# piezo-driver_v0_95-R002.net
KiCad netlist of a schematic drawn in EAGLE
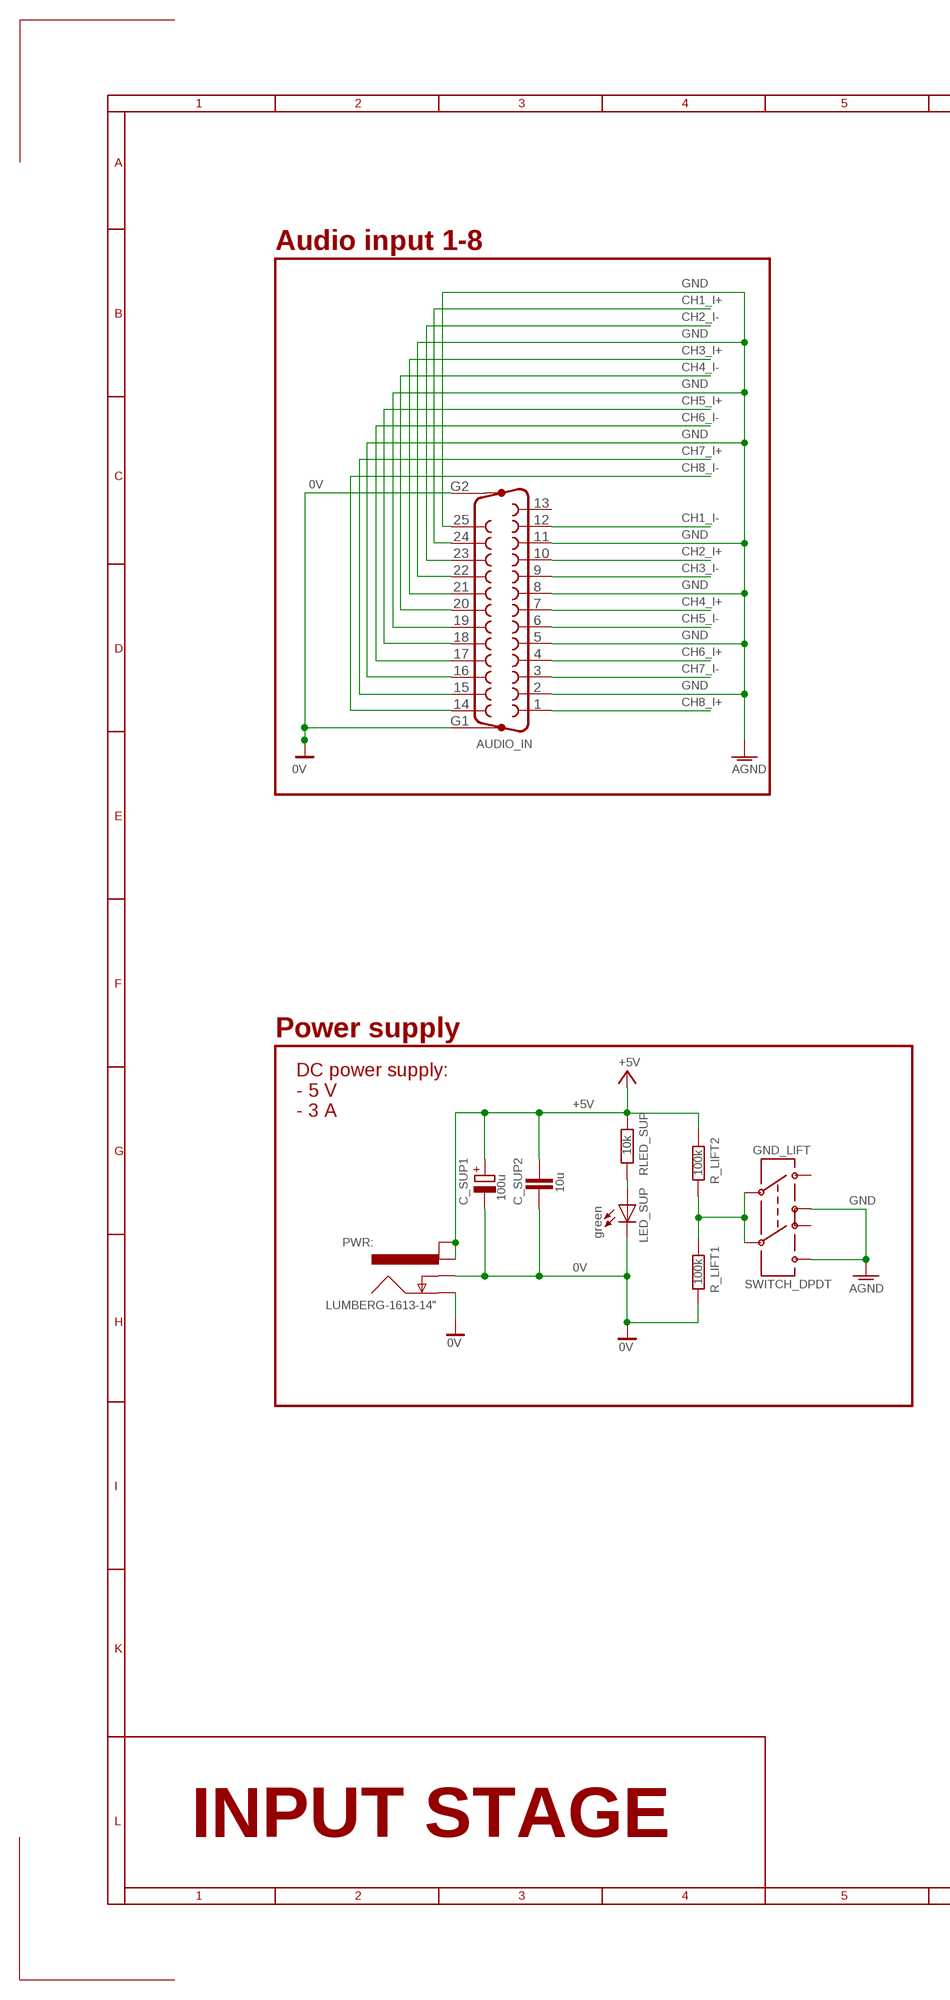
[diagram p0: schematic, sheet 1, part 1 of 2]
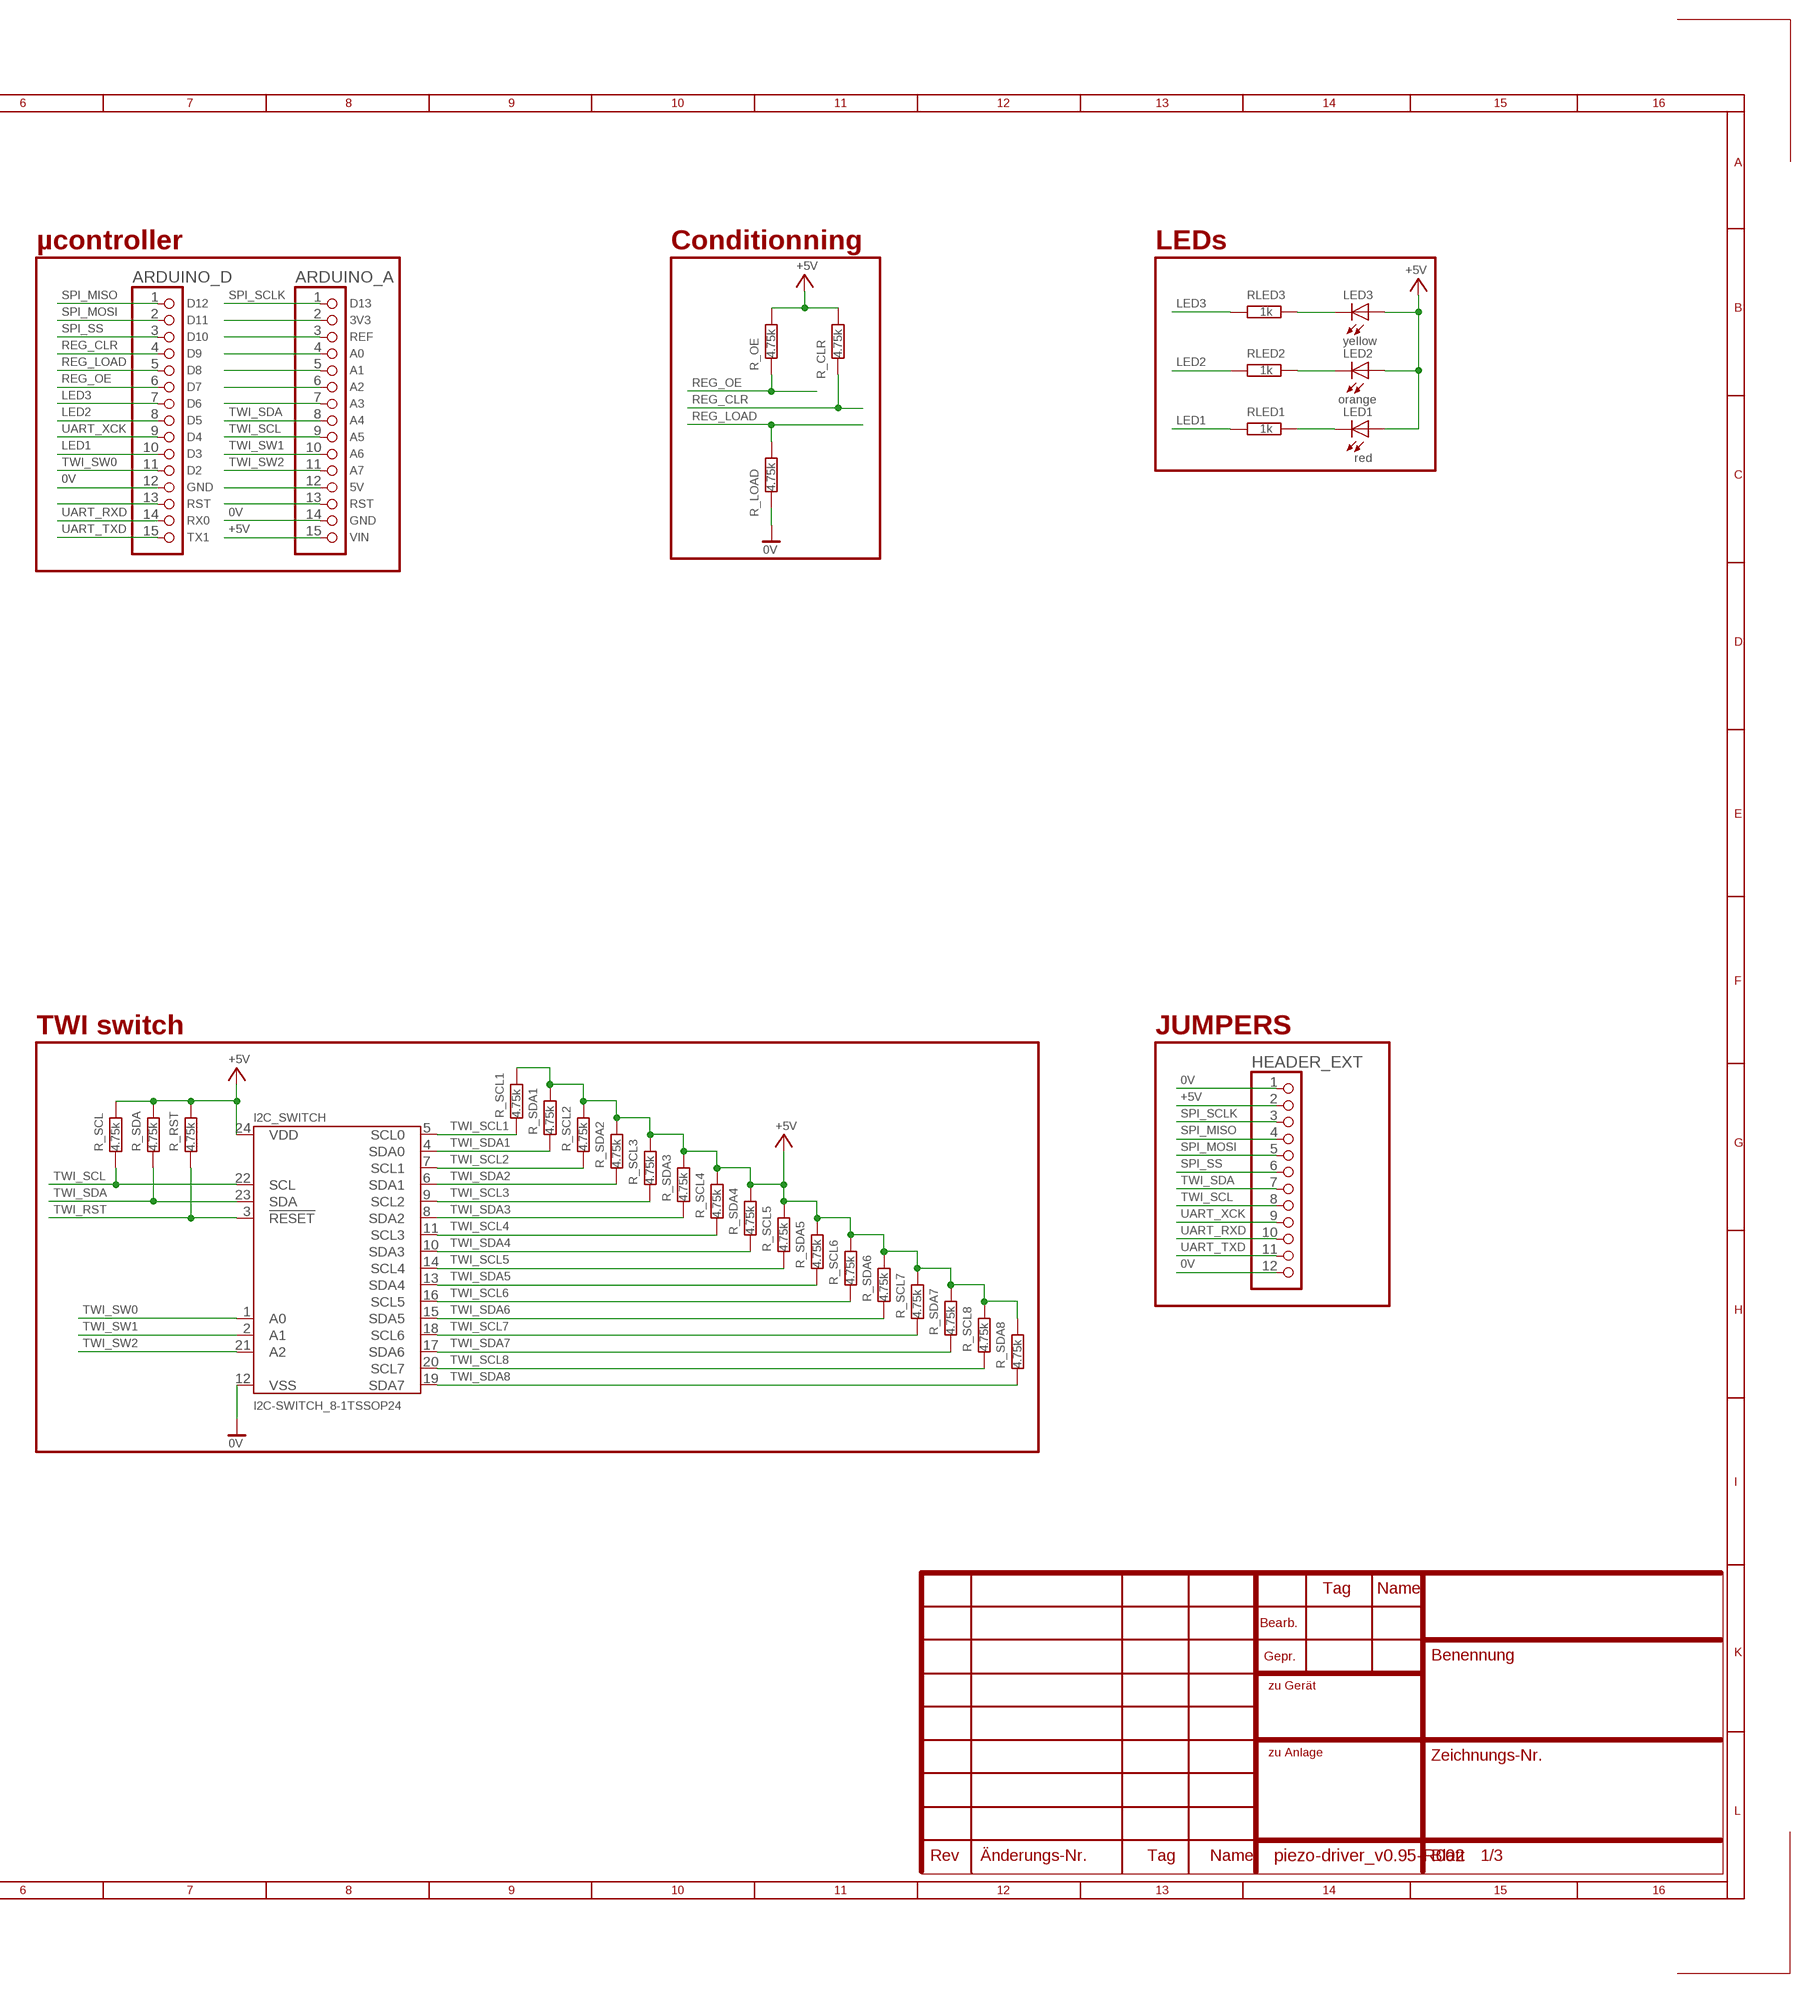
[diagram p1: schematic, sheet 1, part 2 of 2]
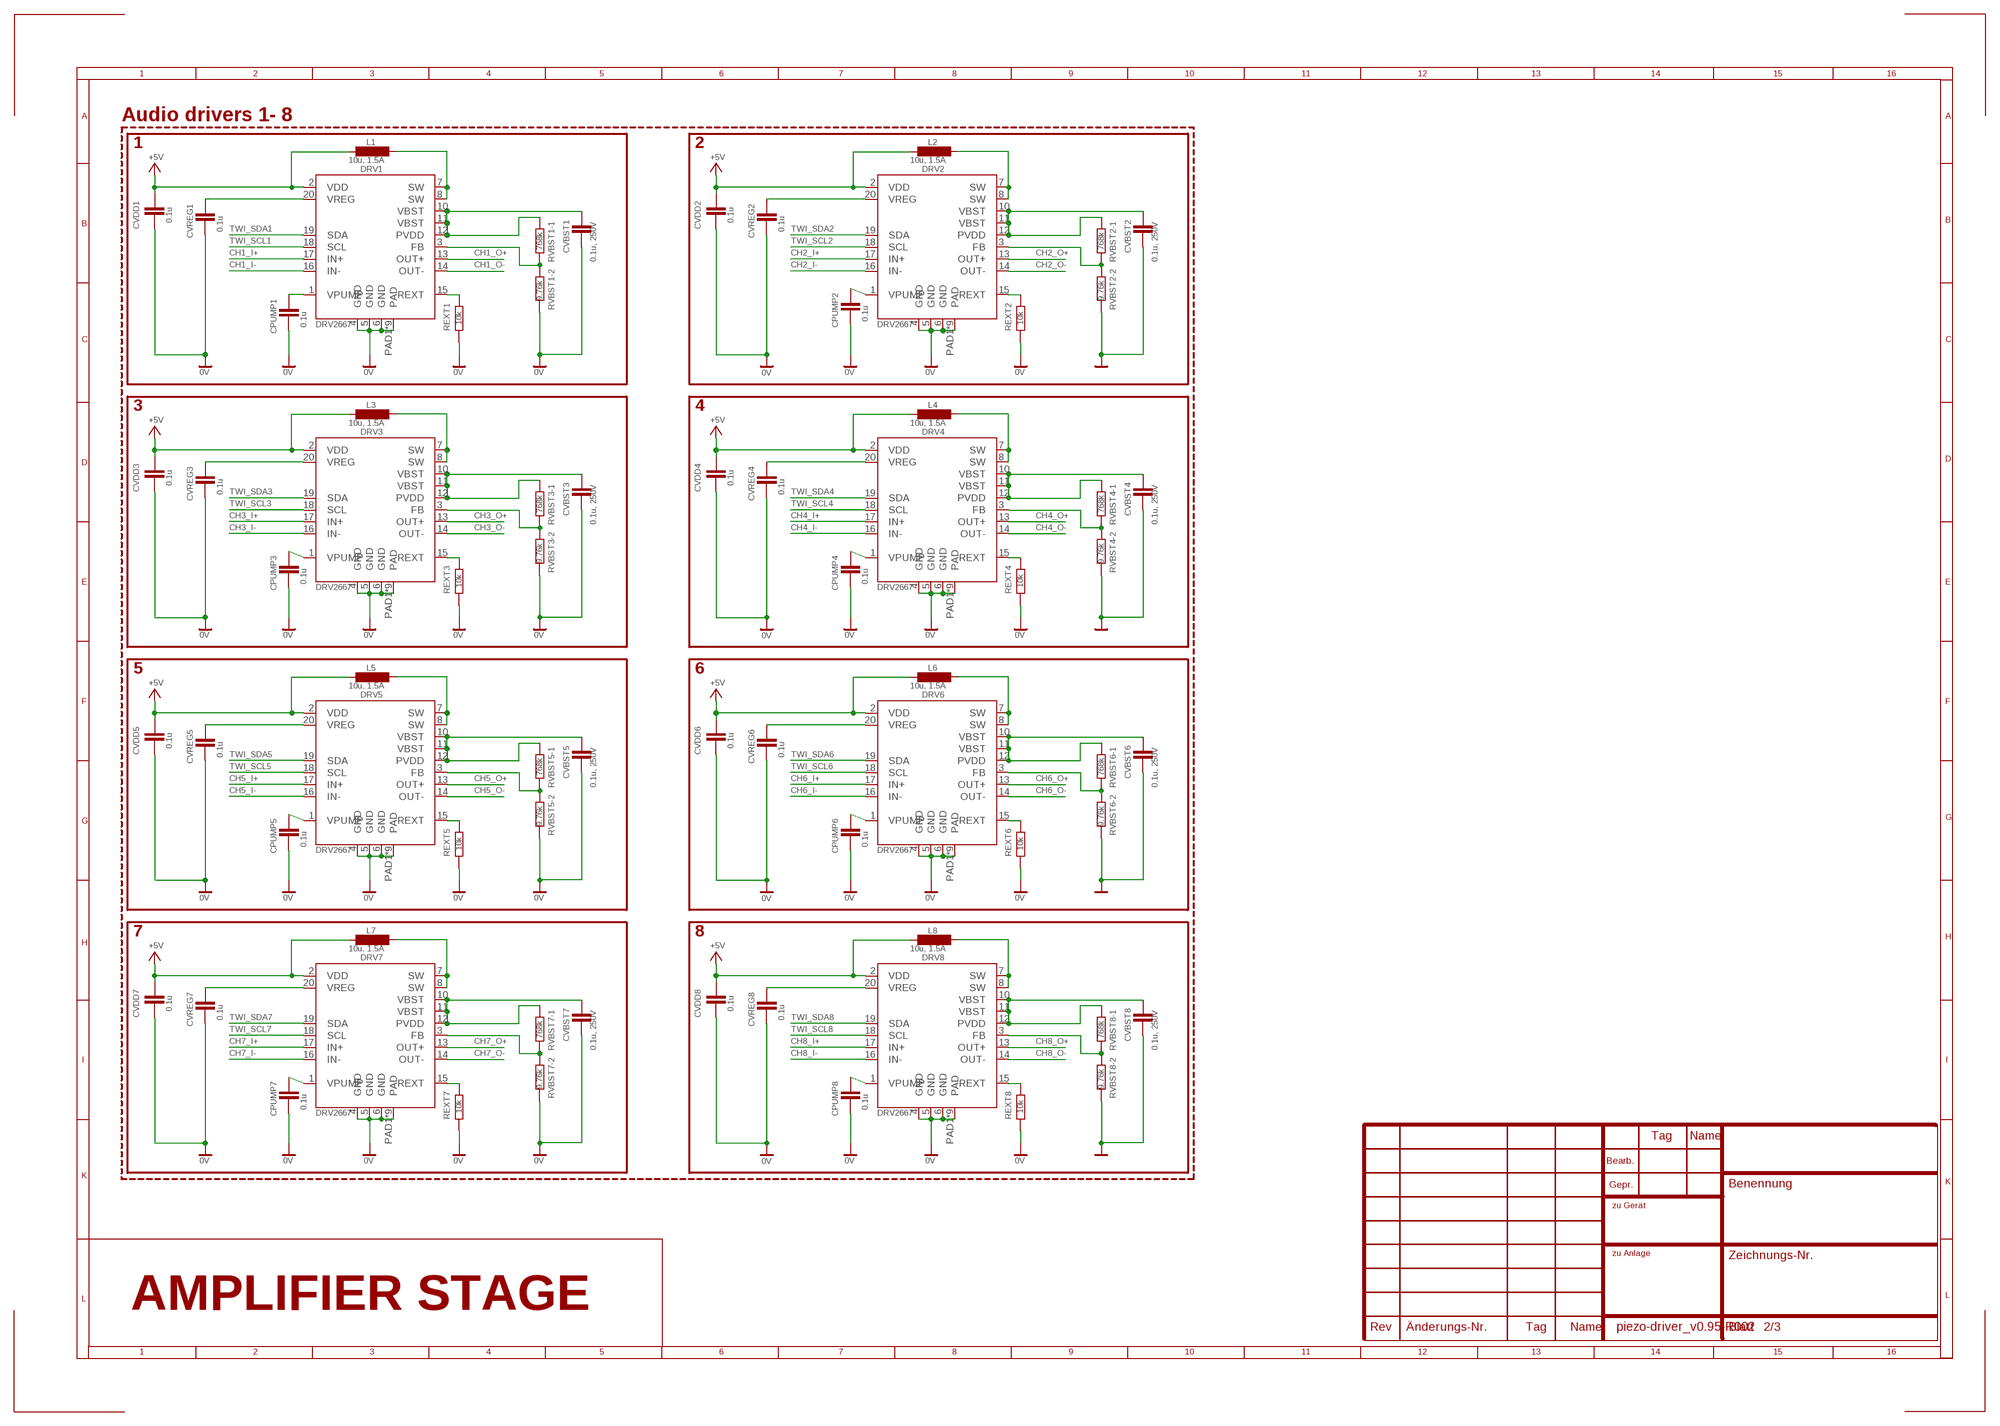
[diagram p2: schematic, sheet 2]
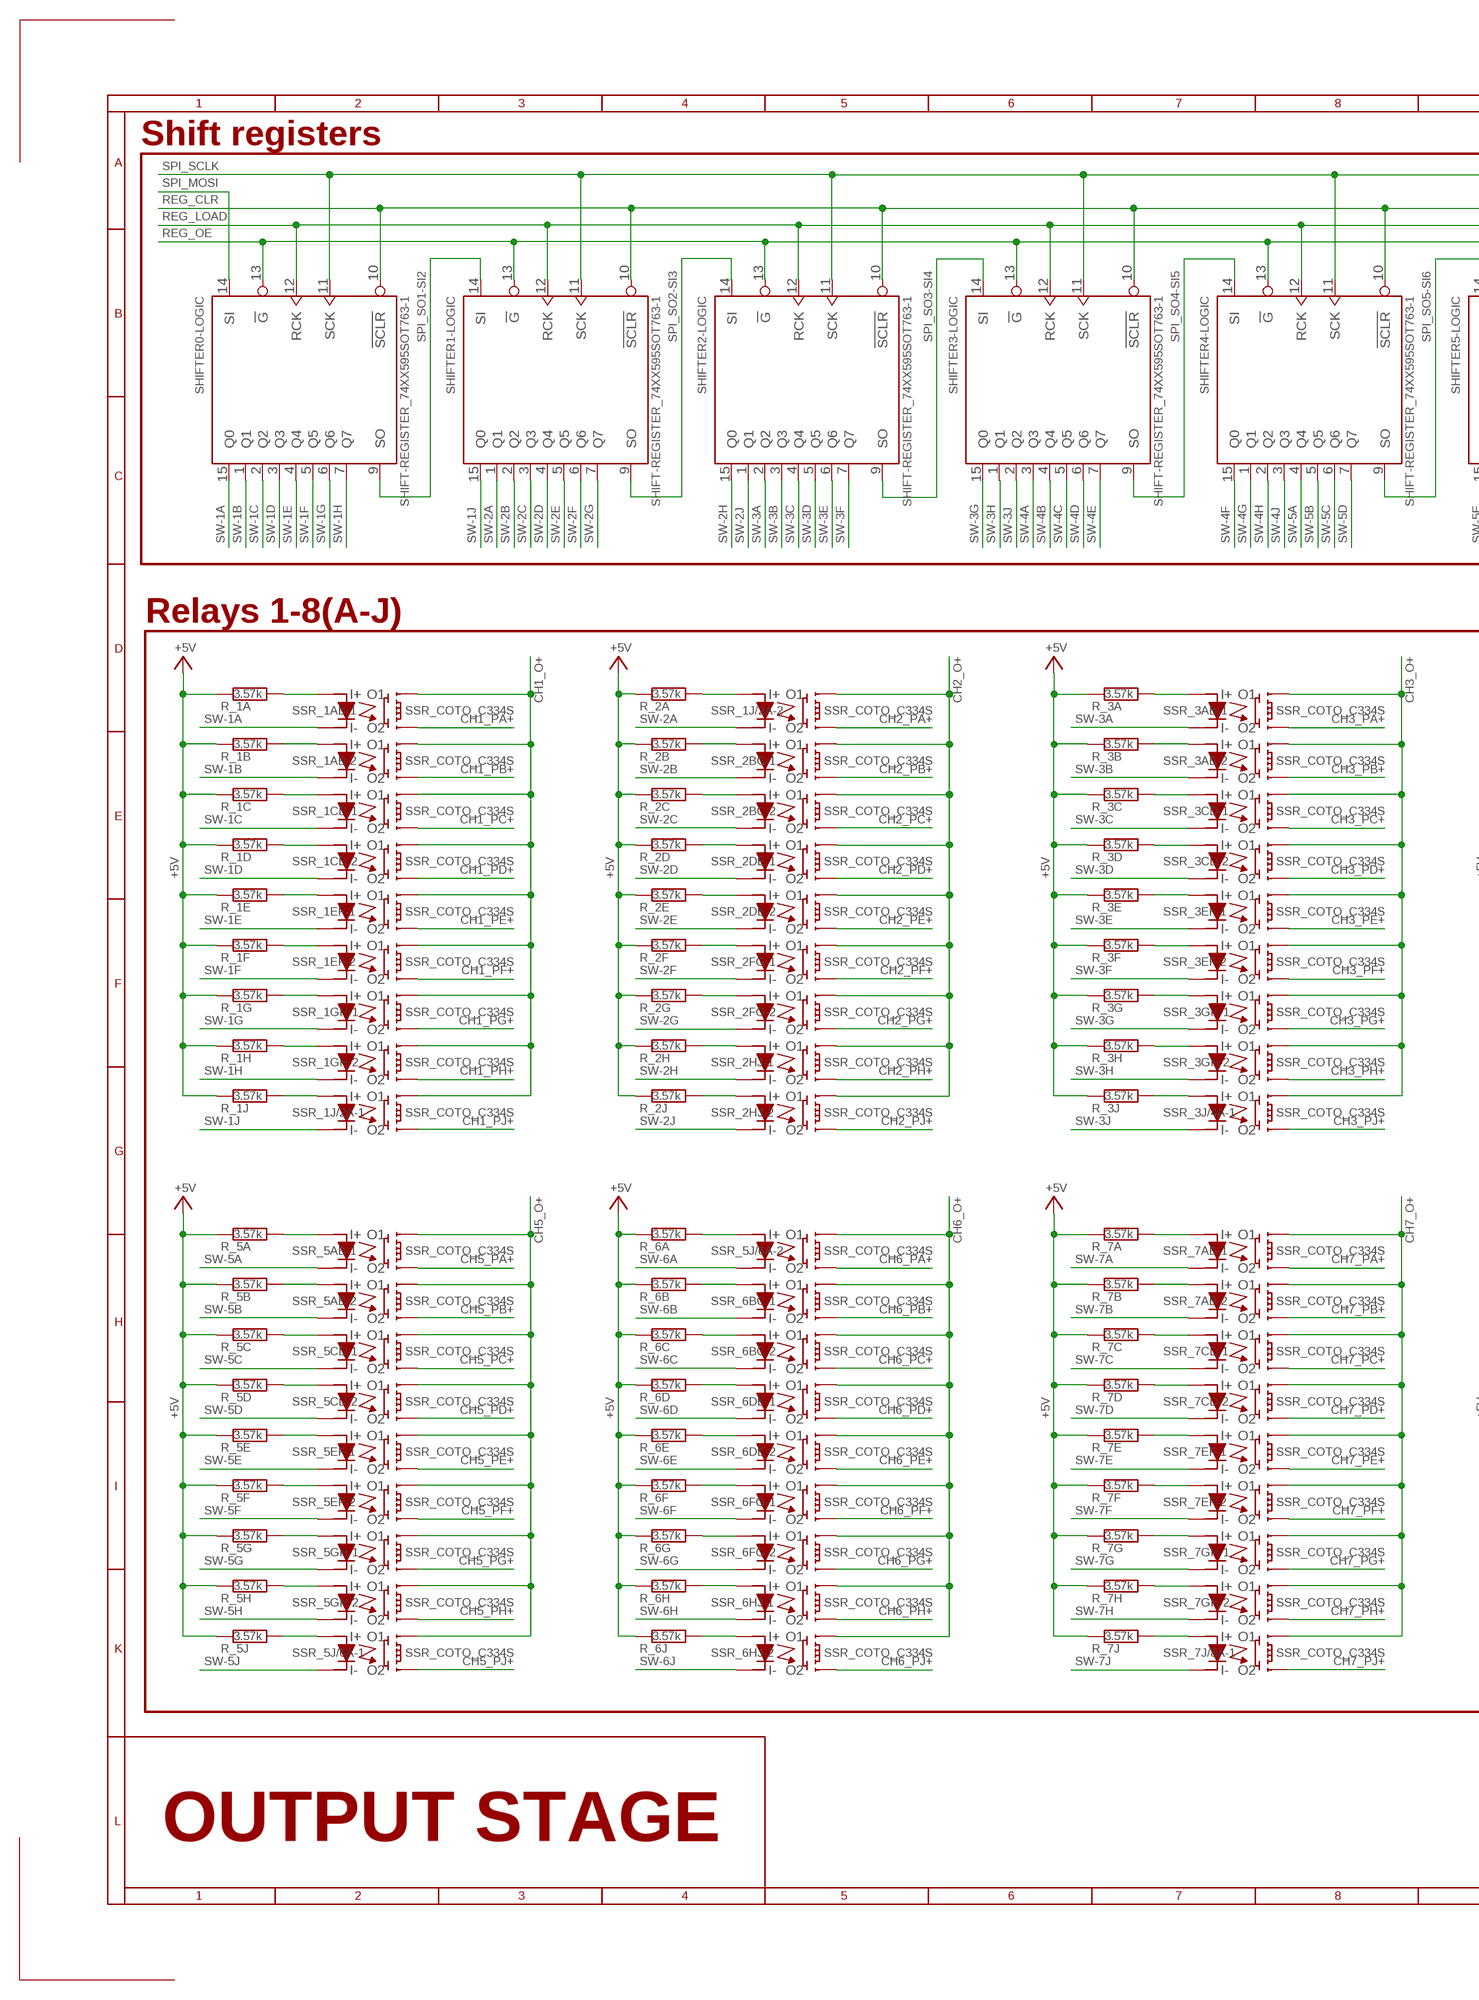
[diagram p3: schematic, sheet 3, part 1 of 2]
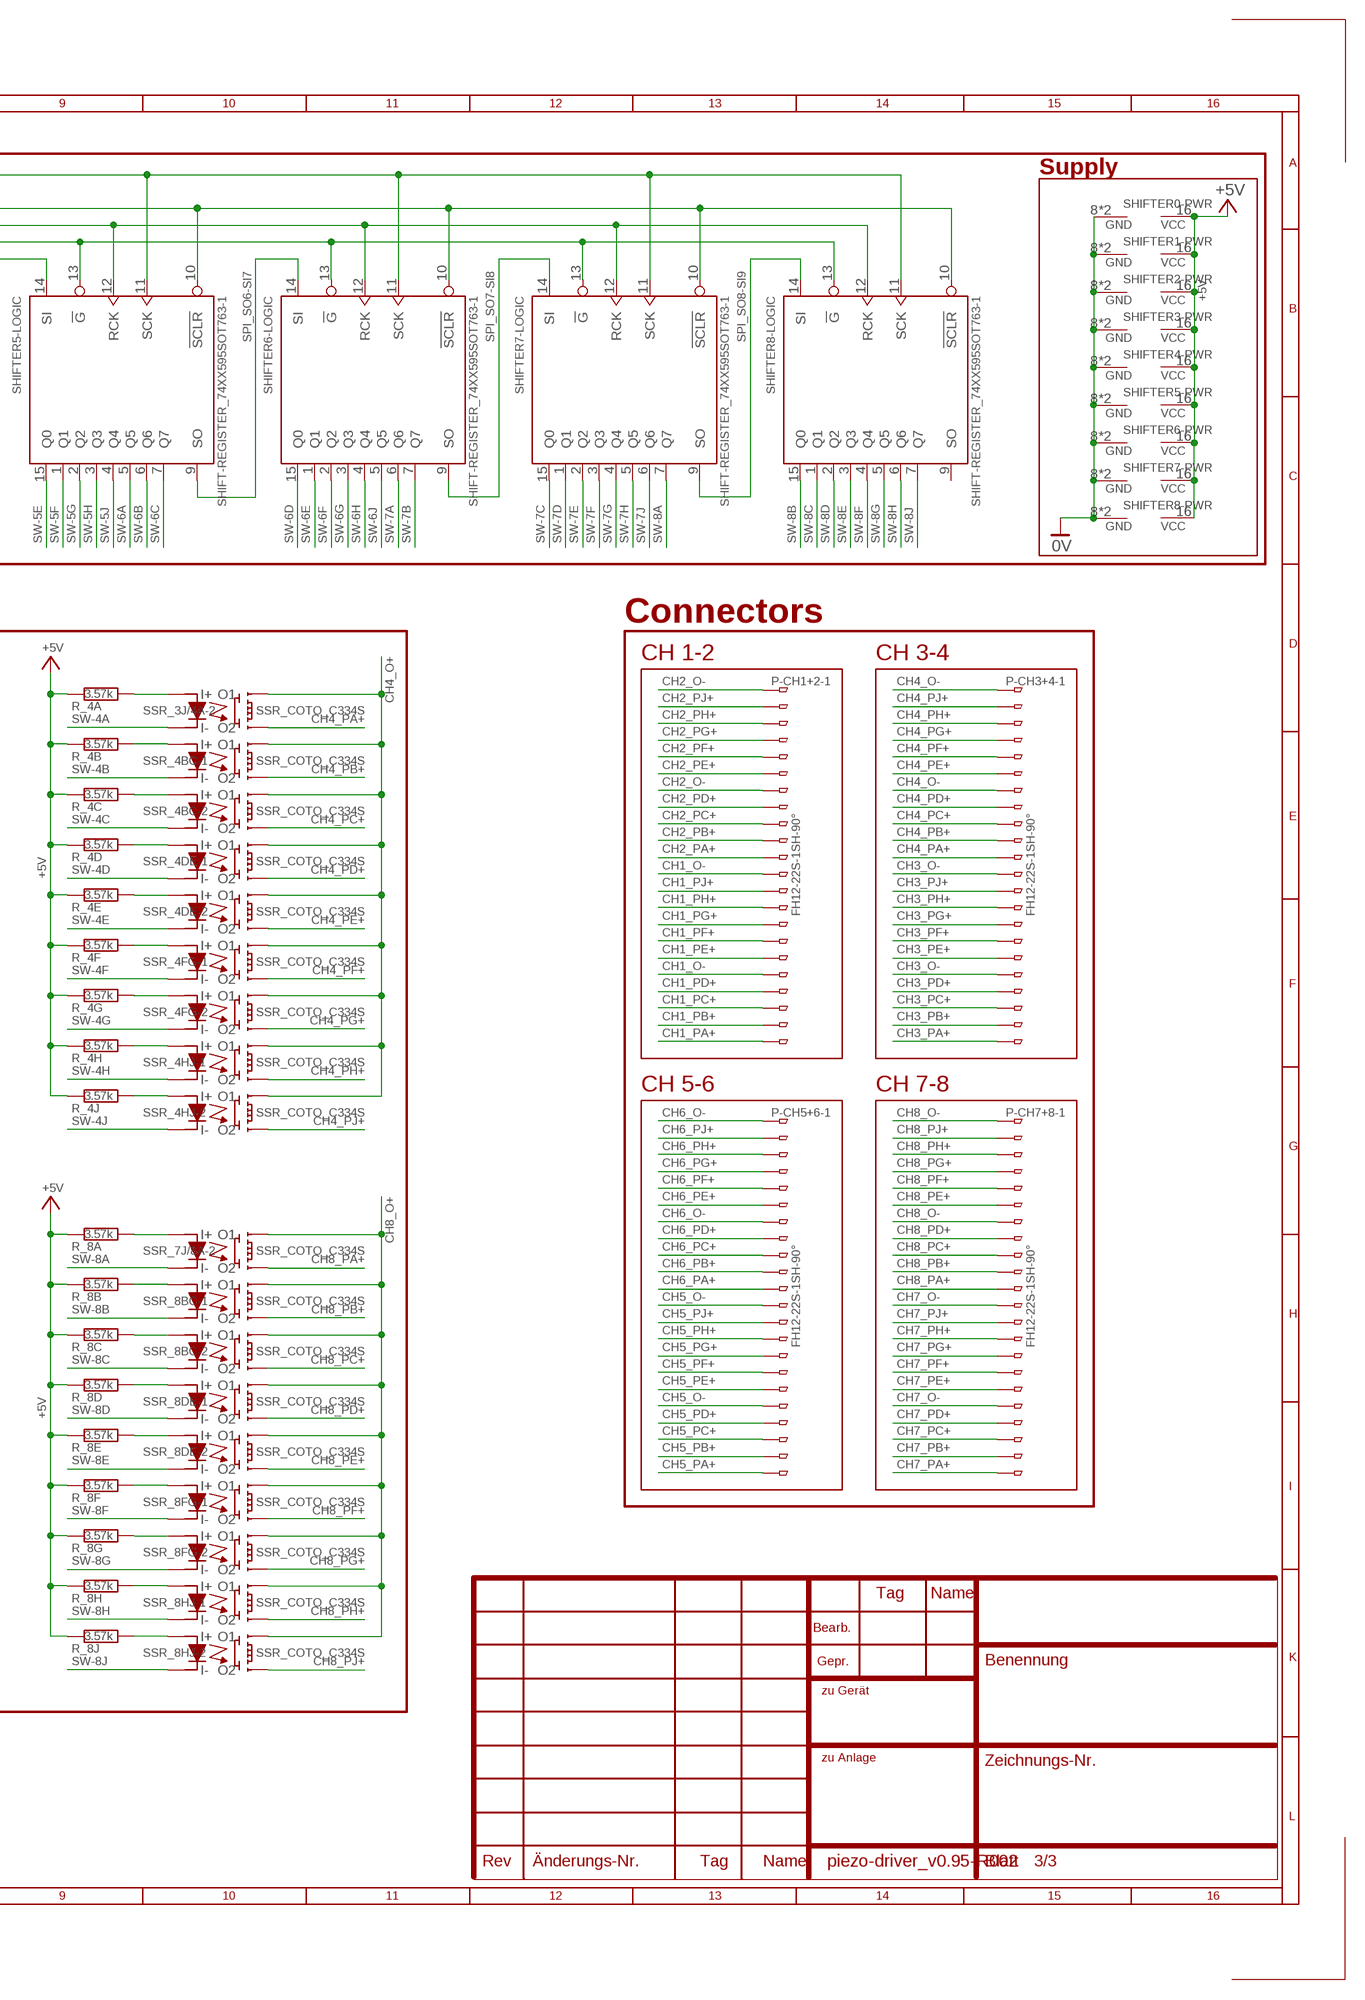
[diagram p4: schematic, sheet 3, part 2 of 2]

(export (version "E")
  (design (tool "Eeschema 10.0.6"))
  (components
    (comp (ref "P-CH1+2")
      (value "FH12-22S-1SH-90°")
      (footprint "eagle-import:FH12-22S-1SH")
      (libsource (lib "eagle-import") (part "FH12-22S-1SH-90°"))
    )
    (comp (ref "P-CH3+4")
      (value "FH12-22S-1SH-90°")
      (footprint "eagle-import:FH12-22S-1SH")
      (libsource (lib "eagle-import") (part "FH12-22S-1SH-90°"))
    )
    (comp (ref "P-CH5+6")
      (value "FH12-22S-1SH-90°")
      (footprint "eagle-import:FH12-22S-1SH")
      (libsource (lib "eagle-import") (part "FH12-22S-1SH-90°"))
    )
    (comp (ref "P-CH7+8")
      (value "FH12-22S-1SH-90°")
      (footprint "eagle-import:FH12-22S-1SH")
      (libsource (lib "eagle-import") (part "FH12-22S-1SH-90°"))
    )
    (comp (ref "R_1A")
      (value "3.57k")
      (footprint "eagle-import:R0402")
      (libsource (lib "eagle-import") (part "R-EU_R0402"))
    )
    (comp (ref "R_1B")
      (value "3.57k")
      (footprint "eagle-import:R0402")
      (libsource (lib "eagle-import") (part "R-EU_R0402"))
    )
    (comp (ref "R_1C")
      (value "3.57k")
      (footprint "eagle-import:R0402")
      (libsource (lib "eagle-import") (part "R-EU_R0402"))
    )
    (comp (ref "R_1D")
      (value "3.57k")
      (footprint "eagle-import:R0402")
      (libsource (lib "eagle-import") (part "R-EU_R0402"))
    )
    (comp (ref "R_1E")
      (value "3.57k")
      (footprint "eagle-import:R0402")
      (libsource (lib "eagle-import") (part "R-EU_R0402"))
    )
    (comp (ref "R_1F")
      (value "3.57k")
      (footprint "eagle-import:R0402")
      (libsource (lib "eagle-import") (part "R-EU_R0402"))
    )
    (comp (ref "R_1G")
      (value "3.57k")
      (footprint "eagle-import:R0402")
      (libsource (lib "eagle-import") (part "R-EU_R0402"))
    )
    (comp (ref "R_1H")
      (value "3.57k")
      (footprint "eagle-import:R0402")
      (libsource (lib "eagle-import") (part "R-EU_R0402"))
    )
    (comp (ref "R_1J")
      (value "3.57k")
      (footprint "eagle-import:R0402")
      (libsource (lib "eagle-import") (part "R-EU_R0402"))
    )
    (comp (ref "R_2A")
      (value "3.57k")
      (footprint "eagle-import:R0402")
      (libsource (lib "eagle-import") (part "R-EU_R0402"))
    )
    (comp (ref "R_2B")
      (value "3.57k")
      (footprint "eagle-import:R0402")
      (libsource (lib "eagle-import") (part "R-EU_R0402"))
    )
    (comp (ref "R_2C")
      (value "3.57k")
      (footprint "eagle-import:R0402")
      (libsource (lib "eagle-import") (part "R-EU_R0402"))
    )
    (comp (ref "R_2D")
      (value "3.57k")
      (footprint "eagle-import:R0402")
      (libsource (lib "eagle-import") (part "R-EU_R0402"))
    )
    (comp (ref "R_2E")
      (value "3.57k")
      (footprint "eagle-import:R0402")
      (libsource (lib "eagle-import") (part "R-EU_R0402"))
    )
    (comp (ref "R_2F")
      (value "3.57k")
      (footprint "eagle-import:R0402")
      (libsource (lib "eagle-import") (part "R-EU_R0402"))
    )
    (comp (ref "R_2G")
      (value "3.57k")
      (footprint "eagle-import:R0402")
      (libsource (lib "eagle-import") (part "R-EU_R0402"))
    )
    (comp (ref "R_2H")
      (value "3.57k")
      (footprint "eagle-import:R0402")
      (libsource (lib "eagle-import") (part "R-EU_R0402"))
    )
    (comp (ref "R_2J")
      (value "3.57k")
      (footprint "eagle-import:R0402")
      (libsource (lib "eagle-import") (part "R-EU_R0402"))
    )
    (comp (ref "R_3A")
      (value "3.57k")
      (footprint "eagle-import:R0402")
      (libsource (lib "eagle-import") (part "R-EU_R0402"))
    )
    (comp (ref "R_3B")
      (value "3.57k")
      (footprint "eagle-import:R0402")
      (libsource (lib "eagle-import") (part "R-EU_R0402"))
    )
    (comp (ref "R_3C")
      (value "3.57k")
      (footprint "eagle-import:R0402")
      (libsource (lib "eagle-import") (part "R-EU_R0402"))
    )
    (comp (ref "R_3D")
      (value "3.57k")
      (footprint "eagle-import:R0402")
      (libsource (lib "eagle-import") (part "R-EU_R0402"))
    )
    (comp (ref "R_3E")
      (value "3.57k")
      (footprint "eagle-import:R0402")
      (libsource (lib "eagle-import") (part "R-EU_R0402"))
    )
    (comp (ref "R_3F")
      (value "3.57k")
      (footprint "eagle-import:R0402")
      (libsource (lib "eagle-import") (part "R-EU_R0402"))
    )
    (comp (ref "R_3G")
      (value "3.57k")
      (footprint "eagle-import:R0402")
      (libsource (lib "eagle-import") (part "R-EU_R0402"))
    )
    (comp (ref "R_3H")
      (value "3.57k")
      (footprint "eagle-import:R0402")
      (libsource (lib "eagle-import") (part "R-EU_R0402"))
    )
    (comp (ref "R_3J")
      (value "3.57k")
      (footprint "eagle-import:R0402")
      (libsource (lib "eagle-import") (part "R-EU_R0402"))
    )
    (comp (ref "R_4A")
      (value "3.57k")
      (footprint "eagle-import:R0402")
      (libsource (lib "eagle-import") (part "R-EU_R0402"))
    )
    (comp (ref "R_4B")
      (value "3.57k")
      (footprint "eagle-import:R0402")
      (libsource (lib "eagle-import") (part "R-EU_R0402"))
    )
    (comp (ref "R_4C")
      (value "3.57k")
      (footprint "eagle-import:R0402")
      (libsource (lib "eagle-import") (part "R-EU_R0402"))
    )
    (comp (ref "R_4D")
      (value "3.57k")
      (footprint "eagle-import:R0402")
      (libsource (lib "eagle-import") (part "R-EU_R0402"))
    )
    (comp (ref "R_4E")
      (value "3.57k")
      (footprint "eagle-import:R0402")
      (libsource (lib "eagle-import") (part "R-EU_R0402"))
    )
    (comp (ref "R_4F")
      (value "3.57k")
      (footprint "eagle-import:R0402")
      (libsource (lib "eagle-import") (part "R-EU_R0402"))
    )
    (comp (ref "R_4G")
      (value "3.57k")
      (footprint "eagle-import:R0402")
      (libsource (lib "eagle-import") (part "R-EU_R0402"))
    )
    (comp (ref "R_4H")
      (value "3.57k")
      (footprint "eagle-import:R0402")
      (libsource (lib "eagle-import") (part "R-EU_R0402"))
    )
    (comp (ref "R_4J")
      (value "3.57k")
      (footprint "eagle-import:R0402")
      (libsource (lib "eagle-import") (part "R-EU_R0402"))
    )
    (comp (ref "R_5A")
      (value "3.57k")
      (footprint "eagle-import:R0402")
      (libsource (lib "eagle-import") (part "R-EU_R0402"))
    )
    (comp (ref "R_5B")
      (value "3.57k")
      (footprint "eagle-import:R0402")
      (libsource (lib "eagle-import") (part "R-EU_R0402"))
    )
    (comp (ref "R_5C")
      (value "3.57k")
      (footprint "eagle-import:R0402")
      (libsource (lib "eagle-import") (part "R-EU_R0402"))
    )
    (comp (ref "R_5D")
      (value "3.57k")
      (footprint "eagle-import:R0402")
      (libsource (lib "eagle-import") (part "R-EU_R0402"))
    )
    (comp (ref "R_5E")
      (value "3.57k")
      (footprint "eagle-import:R0402")
      (libsource (lib "eagle-import") (part "R-EU_R0402"))
    )
    (comp (ref "R_5F")
      (value "3.57k")
      (footprint "eagle-import:R0402")
      (libsource (lib "eagle-import") (part "R-EU_R0402"))
    )
    (comp (ref "R_5G")
      (value "3.57k")
      (footprint "eagle-import:R0402")
      (libsource (lib "eagle-import") (part "R-EU_R0402"))
    )
    (comp (ref "R_5H")
      (value "3.57k")
      (footprint "eagle-import:R0402")
      (libsource (lib "eagle-import") (part "R-EU_R0402"))
    )
    (comp (ref "R_5J")
      (value "3.57k")
      (footprint "eagle-import:R0402")
      (libsource (lib "eagle-import") (part "R-EU_R0402"))
    )
    (comp (ref "R_6A")
      (value "3.57k")
      (footprint "eagle-import:R0402")
      (libsource (lib "eagle-import") (part "R-EU_R0402"))
    )
    (comp (ref "R_6B")
      (value "3.57k")
      (footprint "eagle-import:R0402")
      (libsource (lib "eagle-import") (part "R-EU_R0402"))
    )
    (comp (ref "R_6C")
      (value "3.57k")
      (footprint "eagle-import:R0402")
      (libsource (lib "eagle-import") (part "R-EU_R0402"))
    )
    (comp (ref "R_6D")
      (value "3.57k")
      (footprint "eagle-import:R0402")
      (libsource (lib "eagle-import") (part "R-EU_R0402"))
    )
    (comp (ref "R_6E")
      (value "3.57k")
      (footprint "eagle-import:R0402")
      (libsource (lib "eagle-import") (part "R-EU_R0402"))
    )
    (comp (ref "R_6F")
      (value "3.57k")
      (footprint "eagle-import:R0402")
      (libsource (lib "eagle-import") (part "R-EU_R0402"))
    )
    (comp (ref "R_6G")
      (value "3.57k")
      (footprint "eagle-import:R0402")
      (libsource (lib "eagle-import") (part "R-EU_R0402"))
    )
    (comp (ref "R_6H")
      (value "3.57k")
      (footprint "eagle-import:R0402")
      (libsource (lib "eagle-import") (part "R-EU_R0402"))
    )
    (comp (ref "R_6J")
      (value "3.57k")
      (footprint "eagle-import:R0402")
      (libsource (lib "eagle-import") (part "R-EU_R0402"))
    )
    (comp (ref "R_7A")
      (value "3.57k")
      (footprint "eagle-import:R0402")
      (libsource (lib "eagle-import") (part "R-EU_R0402"))
    )
    (comp (ref "R_7B")
      (value "3.57k")
      (footprint "eagle-import:R0402")
      (libsource (lib "eagle-import") (part "R-EU_R0402"))
    )
    (comp (ref "R_7C")
      (value "3.57k")
      (footprint "eagle-import:R0402")
      (libsource (lib "eagle-import") (part "R-EU_R0402"))
    )
    (comp (ref "R_7D")
      (value "3.57k")
      (footprint "eagle-import:R0402")
      (libsource (lib "eagle-import") (part "R-EU_R0402"))
    )
    (comp (ref "R_7E")
      (value "3.57k")
      (footprint "eagle-import:R0402")
      (libsource (lib "eagle-import") (part "R-EU_R0402"))
    )
    (comp (ref "R_7F")
      (value "3.57k")
      (footprint "eagle-import:R0402")
      (libsource (lib "eagle-import") (part "R-EU_R0402"))
    )
    (comp (ref "R_7G")
      (value "3.57k")
      (footprint "eagle-import:R0402")
      (libsource (lib "eagle-import") (part "R-EU_R0402"))
    )
    (comp (ref "R_7H")
      (value "3.57k")
      (footprint "eagle-import:R0402")
      (libsource (lib "eagle-import") (part "R-EU_R0402"))
    )
    (comp (ref "R_7J")
      (value "3.57k")
      (footprint "eagle-import:R0402")
      (libsource (lib "eagle-import") (part "R-EU_R0402"))
    )
    (comp (ref "R_8A")
      (value "3.57k")
      (footprint "eagle-import:R0402")
      (libsource (lib "eagle-import") (part "R-EU_R0402"))
    )
    (comp (ref "R_8B")
      (value "3.57k")
      (footprint "eagle-import:R0402")
      (libsource (lib "eagle-import") (part "R-EU_R0402"))
    )
    (comp (ref "R_8C")
      (value "3.57k")
      (footprint "eagle-import:R0402")
      (libsource (lib "eagle-import") (part "R-EU_R0402"))
    )
    (comp (ref "R_8D")
      (value "3.57k")
      (footprint "eagle-import:R0402")
      (libsource (lib "eagle-import") (part "R-EU_R0402"))
    )
    (comp (ref "R_8E")
      (value "3.57k")
      (footprint "eagle-import:R0402")
      (libsource (lib "eagle-import") (part "R-EU_R0402"))
    )
    (comp (ref "R_8F")
      (value "3.57k")
      (footprint "eagle-import:R0402")
      (libsource (lib "eagle-import") (part "R-EU_R0402"))
    )
    (comp (ref "R_8G")
      (value "3.57k")
      (footprint "eagle-import:R0402")
      (libsource (lib "eagle-import") (part "R-EU_R0402"))
    )
    (comp (ref "R_8H")
      (value "3.57k")
      (footprint "eagle-import:R0402")
      (libsource (lib "eagle-import") (part "R-EU_R0402"))
    )
    (comp (ref "R_8J")
      (value "3.57k")
      (footprint "eagle-import:R0402")
      (libsource (lib "eagle-import") (part "R-EU_R0402"))
    )
    (comp (ref "SHIFTER0")
      (value "SHIFT-REGISTER_74XX595SOT763-1")
      (footprint "eagle-import:SOT763-1")
      (libsource (lib "eagle-import") (part "SHIFT-REGISTER_74XX595SOT763-1"))
    )
    (comp (ref "SHIFTER1")
      (value "SHIFT-REGISTER_74XX595SOT763-1")
      (footprint "eagle-import:SOT763-1")
      (libsource (lib "eagle-import") (part "SHIFT-REGISTER_74XX595SOT763-1"))
    )
    (comp (ref "SHIFTER2")
      (value "SHIFT-REGISTER_74XX595SOT763-1")
      (footprint "eagle-import:SOT763-1")
      (libsource (lib "eagle-import") (part "SHIFT-REGISTER_74XX595SOT763-1"))
    )
    (comp (ref "SHIFTER3")
      (value "SHIFT-REGISTER_74XX595SOT763-1")
      (footprint "eagle-import:SOT763-1")
      (libsource (lib "eagle-import") (part "SHIFT-REGISTER_74XX595SOT763-1"))
    )
    (comp (ref "SHIFTER4")
      (value "SHIFT-REGISTER_74XX595SOT763-1")
      (footprint "eagle-import:SOT763-1")
      (libsource (lib "eagle-import") (part "SHIFT-REGISTER_74XX595SOT763-1"))
    )
    (comp (ref "SHIFTER5")
      (value "SHIFT-REGISTER_74XX595SOT763-1")
      (footprint "eagle-import:SOT763-1")
      (libsource (lib "eagle-import") (part "SHIFT-REGISTER_74XX595SOT763-1"))
    )
    (comp (ref "SHIFTER6")
      (value "SHIFT-REGISTER_74XX595SOT763-1")
      (footprint "eagle-import:SOT763-1")
      (libsource (lib "eagle-import") (part "SHIFT-REGISTER_74XX595SOT763-1"))
    )
    (comp (ref "SHIFTER7")
      (value "SHIFT-REGISTER_74XX595SOT763-1")
      (footprint "eagle-import:SOT763-1")
      (libsource (lib "eagle-import") (part "SHIFT-REGISTER_74XX595SOT763-1"))
    )
    (comp (ref "SHIFTER8")
      (value "SHIFT-REGISTER_74XX595SOT763-1")
      (footprint "eagle-import:SOT763-1")
      (libsource (lib "eagle-import") (part "SHIFT-REGISTER_74XX595SOT763-1"))
    )
    (comp (ref "SSR_1AB")
      (value "SSR_COTO_C334S")
      (footprint "eagle-import:SOP8")
      (libsource (lib "eagle-import") (part "SSR_COTO_C334S"))
    )
    (comp (ref "SSR_1CD")
      (value "SSR_COTO_C334S")
      (footprint "eagle-import:SOP8")
      (libsource (lib "eagle-import") (part "SSR_COTO_C334S"))
    )
    (comp (ref "SSR_1EF")
      (value "SSR_COTO_C334S")
      (footprint "eagle-import:SOP8")
      (libsource (lib "eagle-import") (part "SSR_COTO_C334S"))
    )
    (comp (ref "SSR_1GH")
      (value "SSR_COTO_C334S")
      (footprint "eagle-import:SOP8")
      (libsource (lib "eagle-import") (part "SSR_COTO_C334S"))
    )
    (comp (ref "SSR_1J/2A")
      (value "SSR_COTO_C334S")
      (footprint "eagle-import:SOP8")
      (libsource (lib "eagle-import") (part "SSR_COTO_C334S"))
    )
    (comp (ref "SSR_2BC")
      (value "SSR_COTO_C334S")
      (footprint "eagle-import:SOP8")
      (libsource (lib "eagle-import") (part "SSR_COTO_C334S"))
    )
    (comp (ref "SSR_2DE")
      (value "SSR_COTO_C334S")
      (footprint "eagle-import:SOP8")
      (libsource (lib "eagle-import") (part "SSR_COTO_C334S"))
    )
    (comp (ref "SSR_2FG")
      (value "SSR_COTO_C334S")
      (footprint "eagle-import:SOP8")
      (libsource (lib "eagle-import") (part "SSR_COTO_C334S"))
    )
    (comp (ref "SSR_2HJ")
      (value "SSR_COTO_C334S")
      (footprint "eagle-import:SOP8")
      (libsource (lib "eagle-import") (part "SSR_COTO_C334S"))
    )
    (comp (ref "SSR_3AB")
      (value "SSR_COTO_C334S")
      (footprint "eagle-import:SOP8")
      (libsource (lib "eagle-import") (part "SSR_COTO_C334S"))
    )
    (comp (ref "SSR_3CD")
      (value "SSR_COTO_C334S")
      (footprint "eagle-import:SOP8")
      (libsource (lib "eagle-import") (part "SSR_COTO_C334S"))
    )
    (comp (ref "SSR_3EF")
      (value "SSR_COTO_C334S")
      (footprint "eagle-import:SOP8")
      (libsource (lib "eagle-import") (part "SSR_COTO_C334S"))
    )
    (comp (ref "SSR_3GH")
      (value "SSR_COTO_C334S")
      (footprint "eagle-import:SOP8")
      (libsource (lib "eagle-import") (part "SSR_COTO_C334S"))
    )
    (comp (ref "SSR_3J/4A")
      (value "SSR_COTO_C334S")
      (footprint "eagle-import:SOP8")
      (libsource (lib "eagle-import") (part "SSR_COTO_C334S"))
    )
    (comp (ref "SSR_4BC")
      (value "SSR_COTO_C334S")
      (footprint "eagle-import:SOP8")
      (libsource (lib "eagle-import") (part "SSR_COTO_C334S"))
    )
    (comp (ref "SSR_4DE")
      (value "SSR_COTO_C334S")
      (footprint "eagle-import:SOP8")
      (libsource (lib "eagle-import") (part "SSR_COTO_C334S"))
    )
    (comp (ref "SSR_4FG")
      (value "SSR_COTO_C334S")
      (footprint "eagle-import:SOP8")
      (libsource (lib "eagle-import") (part "SSR_COTO_C334S"))
    )
    (comp (ref "SSR_4HJ")
      (value "SSR_COTO_C334S")
      (footprint "eagle-import:SOP8")
      (libsource (lib "eagle-import") (part "SSR_COTO_C334S"))
    )
    (comp (ref "SSR_5AB")
      (value "SSR_COTO_C334S")
      (footprint "eagle-import:SOP8")
      (libsource (lib "eagle-import") (part "SSR_COTO_C334S"))
    )
    (comp (ref "SSR_5CD")
      (value "SSR_COTO_C334S")
      (footprint "eagle-import:SOP8")
      (libsource (lib "eagle-import") (part "SSR_COTO_C334S"))
    )
    (comp (ref "SSR_5EF")
      (value "SSR_COTO_C334S")
      (footprint "eagle-import:SOP8")
      (libsource (lib "eagle-import") (part "SSR_COTO_C334S"))
    )
    (comp (ref "SSR_5GH")
      (value "SSR_COTO_C334S")
      (footprint "eagle-import:SOP8")
      (libsource (lib "eagle-import") (part "SSR_COTO_C334S"))
    )
    (comp (ref "SSR_5J/6A")
      (value "SSR_COTO_C334S")
      (footprint "eagle-import:SOP8")
      (libsource (lib "eagle-import") (part "SSR_COTO_C334S"))
    )
    (comp (ref "SSR_6BC")
      (value "SSR_COTO_C334S")
      (footprint "eagle-import:SOP8")
      (libsource (lib "eagle-import") (part "SSR_COTO_C334S"))
    )
    (comp (ref "SSR_6DE")
      (value "SSR_COTO_C334S")
      (footprint "eagle-import:SOP8")
      (libsource (lib "eagle-import") (part "SSR_COTO_C334S"))
    )
    (comp (ref "SSR_6FG")
      (value "SSR_COTO_C334S")
      (footprint "eagle-import:SOP8")
      (libsource (lib "eagle-import") (part "SSR_COTO_C334S"))
    )
    (comp (ref "SSR_6HJ")
      (value "SSR_COTO_C334S")
      (footprint "eagle-import:SOP8")
      (libsource (lib "eagle-import") (part "SSR_COTO_C334S"))
    )
    (comp (ref "SSR_7AB")
      (value "SSR_COTO_C334S")
      (footprint "eagle-import:SOP8")
      (libsource (lib "eagle-import") (part "SSR_COTO_C334S"))
    )
    (comp (ref "SSR_7CD")
      (value "SSR_COTO_C334S")
      (footprint "eagle-import:SOP8")
      (libsource (lib "eagle-import") (part "SSR_COTO_C334S"))
    )
    (comp (ref "SSR_7EF")
      (value "SSR_COTO_C334S")
      (footprint "eagle-import:SOP8")
      (libsource (lib "eagle-import") (part "SSR_COTO_C334S"))
    )
    (comp (ref "SSR_7GH")
      (value "SSR_COTO_C334S")
      (footprint "eagle-import:SOP8")
      (libsource (lib "eagle-import") (part "SSR_COTO_C334S"))
    )
    (comp (ref "SSR_7J/8A")
      (value "SSR_COTO_C334S")
      (footprint "eagle-import:SOP8")
      (libsource (lib "eagle-import") (part "SSR_COTO_C334S"))
    )
    (comp (ref "SSR_8BC")
      (value "SSR_COTO_C334S")
      (footprint "eagle-import:SOP8")
      (libsource (lib "eagle-import") (part "SSR_COTO_C334S"))
    )
    (comp (ref "SSR_8DE")
      (value "SSR_COTO_C334S")
      (footprint "eagle-import:SOP8")
      (libsource (lib "eagle-import") (part "SSR_COTO_C334S"))
    )
    (comp (ref "SSR_8FG")
      (value "SSR_COTO_C334S")
      (footprint "eagle-import:SOP8")
      (libsource (lib "eagle-import") (part "SSR_COTO_C334S"))
    )
    (comp (ref "SSR_8HJ")
      (value "SSR_COTO_C334S")
      (footprint "eagle-import:SOP8")
      (libsource (lib "eagle-import") (part "SSR_COTO_C334S"))
    )
    (comp (ref "CPUMP1")
      (value "0.1u")
      (footprint "eagle-import:C0402")
      (libsource (lib "eagle-import") (part "C-EUC0402"))
    )
    (comp (ref "CPUMP2")
      (value "0.1u")
      (footprint "eagle-import:C0402")
      (libsource (lib "eagle-import") (part "C-EUC0402"))
    )
    (comp (ref "CPUMP3")
      (value "0.1u")
      (footprint "eagle-import:C0402")
      (libsource (lib "eagle-import") (part "C-EUC0402"))
    )
    (comp (ref "CPUMP4")
      (value "0.1u")
      (footprint "eagle-import:C0402")
      (libsource (lib "eagle-import") (part "C-EUC0402"))
    )
    (comp (ref "CPUMP5")
      (value "0.1u")
      (footprint "eagle-import:C0402")
      (libsource (lib "eagle-import") (part "C-EUC0402"))
    )
    (comp (ref "CPUMP6")
      (value "0.1u")
      (footprint "eagle-import:C0402")
      (libsource (lib "eagle-import") (part "C-EUC0402"))
    )
    (comp (ref "CPUMP7")
      (value "0.1u")
      (footprint "eagle-import:C0402")
      (libsource (lib "eagle-import") (part "C-EUC0402"))
    )
    (comp (ref "CPUMP8")
      (value "0.1u")
      (footprint "eagle-import:C0402")
      (libsource (lib "eagle-import") (part "C-EUC0402"))
    )
    (comp (ref "CVBST1")
      (value "0.1u, 250V")
      (footprint "eagle-import:C0805")
      (libsource (lib "eagle-import") (part "C-EUC0805"))
    )
    (comp (ref "CVBST2")
      (value "0.1u, 250V")
      (footprint "eagle-import:C0805")
      (libsource (lib "eagle-import") (part "C-EUC0805"))
    )
    (comp (ref "CVBST3")
      (value "0.1u, 250V")
      (footprint "eagle-import:C0805")
      (libsource (lib "eagle-import") (part "C-EUC0805"))
    )
    (comp (ref "CVBST4")
      (value "0.1u, 250V")
      (footprint "eagle-import:C0805")
      (libsource (lib "eagle-import") (part "C-EUC0805"))
    )
    (comp (ref "CVBST5")
      (value "0.1u, 250V")
      (footprint "eagle-import:C0805")
      (libsource (lib "eagle-import") (part "C-EUC0805"))
    )
    (comp (ref "CVBST6")
      (value "0.1u, 250V")
      (footprint "eagle-import:C0805")
      (libsource (lib "eagle-import") (part "C-EUC0805"))
    )
    (comp (ref "CVBST7")
      (value "0.1u, 250V")
      (footprint "eagle-import:C0805")
      (libsource (lib "eagle-import") (part "C-EUC0805"))
    )
    (comp (ref "CVBST8")
      (value "0.1u, 250V")
      (footprint "eagle-import:C0805")
      (libsource (lib "eagle-import") (part "C-EUC0805"))
    )
    (comp (ref "CVDD1")
      (value "0.1u")
      (footprint "eagle-import:C0402")
      (libsource (lib "eagle-import") (part "C-EUC0402"))
    )
    (comp (ref "CVDD2")
      (value "0.1u")
      (footprint "eagle-import:C0402")
      (libsource (lib "eagle-import") (part "C-EUC0402"))
    )
    (comp (ref "CVDD3")
      (value "0.1u")
      (footprint "eagle-import:C0402")
      (libsource (lib "eagle-import") (part "C-EUC0402"))
    )
    (comp (ref "CVDD4")
      (value "0.1u")
      (footprint "eagle-import:C0402")
      (libsource (lib "eagle-import") (part "C-EUC0402"))
    )
    (comp (ref "CVDD5")
      (value "0.1u")
      (footprint "eagle-import:C0402")
      (libsource (lib "eagle-import") (part "C-EUC0402"))
    )
    (comp (ref "CVDD6")
      (value "0.1u")
      (footprint "eagle-import:C0402")
      (libsource (lib "eagle-import") (part "C-EUC0402"))
    )
    (comp (ref "CVDD7")
      (value "0.1u")
      (footprint "eagle-import:C0402")
      (libsource (lib "eagle-import") (part "C-EUC0402"))
    )
    (comp (ref "CVDD8")
      (value "0.1u")
      (footprint "eagle-import:C0402")
      (libsource (lib "eagle-import") (part "C-EUC0402"))
    )
    (comp (ref "CVREG1")
      (value "0.1u")
      (footprint "eagle-import:C0402")
      (libsource (lib "eagle-import") (part "C-EUC0402"))
    )
    (comp (ref "CVREG2")
      (value "0.1u")
      (footprint "eagle-import:C0402")
      (libsource (lib "eagle-import") (part "C-EUC0402"))
    )
    (comp (ref "CVREG3")
      (value "0.1u")
      (footprint "eagle-import:C0402")
      (libsource (lib "eagle-import") (part "C-EUC0402"))
    )
    (comp (ref "CVREG4")
      (value "0.1u")
      (footprint "eagle-import:C0402")
      (libsource (lib "eagle-import") (part "C-EUC0402"))
    )
    (comp (ref "CVREG5")
      (value "0.1u")
      (footprint "eagle-import:C0402")
      (libsource (lib "eagle-import") (part "C-EUC0402"))
    )
    (comp (ref "CVREG6")
      (value "0.1u")
      (footprint "eagle-import:C0402")
      (libsource (lib "eagle-import") (part "C-EUC0402"))
    )
    (comp (ref "CVREG7")
      (value "0.1u")
      (footprint "eagle-import:C0402")
      (libsource (lib "eagle-import") (part "C-EUC0402"))
    )
    (comp (ref "CVREG8")
      (value "0.1u")
      (footprint "eagle-import:C0402")
      (libsource (lib "eagle-import") (part "C-EUC0402"))
    )
    (comp (ref "DRV1")
      (value "DRV2667")
      (footprint "eagle-import:QFN-20_9TH")
      (libsource (lib "eagle-import") (part "DRV2667"))
    )
    (comp (ref "DRV2")
      (value "DRV2667")
      (footprint "eagle-import:QFN-20_9TH")
      (libsource (lib "eagle-import") (part "DRV2667"))
    )
    (comp (ref "DRV3")
      (value "DRV2667")
      (footprint "eagle-import:QFN-20_9TH")
      (libsource (lib "eagle-import") (part "DRV2667"))
    )
    (comp (ref "DRV4")
      (value "DRV2667")
      (footprint "eagle-import:QFN-20_9TH")
      (libsource (lib "eagle-import") (part "DRV2667"))
    )
    (comp (ref "DRV5")
      (value "DRV2667")
      (footprint "eagle-import:QFN-20_9TH")
      (libsource (lib "eagle-import") (part "DRV2667"))
    )
    (comp (ref "DRV6")
      (value "DRV2667")
      (footprint "eagle-import:QFN-20_9TH")
      (libsource (lib "eagle-import") (part "DRV2667"))
    )
    (comp (ref "DRV7")
      (value "DRV2667")
      (footprint "eagle-import:QFN-20_9TH")
      (libsource (lib "eagle-import") (part "DRV2667"))
    )
    (comp (ref "DRV8")
      (value "DRV2667")
      (footprint "eagle-import:QFN-20_9TH")
      (libsource (lib "eagle-import") (part "DRV2667"))
    )
    (comp (ref "L1")
      (value "10u, 1.5A")
      (footprint "eagle-import:L4.0X4.0")
      (libsource (lib "eagle-import") (part "L-EU4.0X4.0"))
    )
    (comp (ref "L2")
      (value "10u, 1.5A")
      (footprint "eagle-import:L4.0X4.0")
      (libsource (lib "eagle-import") (part "L-EU4.0X4.0"))
    )
    (comp (ref "L3")
      (value "10u, 1.5A")
      (footprint "eagle-import:L4.0X4.0")
      (libsource (lib "eagle-import") (part "L-EU4.0X4.0"))
    )
    (comp (ref "L4")
      (value "10u, 1.5A")
      (footprint "eagle-import:L4.0X4.0")
      (libsource (lib "eagle-import") (part "L-EU4.0X4.0"))
    )
    (comp (ref "L5")
      (value "10u, 1.5A")
      (footprint "eagle-import:L4.0X4.0")
      (libsource (lib "eagle-import") (part "L-EU4.0X4.0"))
    )
    (comp (ref "L6")
      (value "10u, 1.5A")
      (footprint "eagle-import:L4.0X4.0")
      (libsource (lib "eagle-import") (part "L-EU4.0X4.0"))
    )
    (comp (ref "L7")
      (value "10u, 1.5A")
      (footprint "eagle-import:L4.0X4.0")
      (libsource (lib "eagle-import") (part "L-EU4.0X4.0"))
    )
    (comp (ref "L8")
      (value "10u, 1.5A")
      (footprint "eagle-import:L4.0X4.0")
      (libsource (lib "eagle-import") (part "L-EU4.0X4.0"))
    )
    (comp (ref "REXT1")
      (value "10k")
      (footprint "eagle-import:R0402")
      (libsource (lib "eagle-import") (part "R-EU_R0402"))
    )
    (comp (ref "REXT2")
      (value "10k")
      (footprint "eagle-import:R0402")
      (libsource (lib "eagle-import") (part "R-EU_R0402"))
    )
    (comp (ref "REXT3")
      (value "10k")
      (footprint "eagle-import:R0402")
      (libsource (lib "eagle-import") (part "R-EU_R0402"))
    )
    (comp (ref "REXT4")
      (value "10k")
      (footprint "eagle-import:R0402")
      (libsource (lib "eagle-import") (part "R-EU_R0402"))
    )
    (comp (ref "REXT5")
      (value "10k")
      (footprint "eagle-import:R0402")
      (libsource (lib "eagle-import") (part "R-EU_R0402"))
    )
    (comp (ref "REXT6")
      (value "10k")
      (footprint "eagle-import:R0402")
      (libsource (lib "eagle-import") (part "R-EU_R0402"))
    )
    (comp (ref "REXT7")
      (value "10k")
      (footprint "eagle-import:R0402")
      (libsource (lib "eagle-import") (part "R-EU_R0402"))
    )
    (comp (ref "REXT8")
      (value "10k")
      (footprint "eagle-import:R0402")
      (libsource (lib "eagle-import") (part "R-EU_R0402"))
    )
    (comp (ref "RVBST1-1")
      (value "768k")
      (footprint "eagle-import:R0402")
      (libsource (lib "eagle-import") (part "R-EU_R0402"))
    )
    (comp (ref "RVBST1-2")
      (value "9.76k")
      (footprint "eagle-import:R0402")
      (libsource (lib "eagle-import") (part "R-EU_R0402"))
    )
    (comp (ref "RVBST2-1")
      (value "768k")
      (footprint "eagle-import:R0402")
      (libsource (lib "eagle-import") (part "R-EU_R0402"))
    )
    (comp (ref "RVBST2-2")
      (value "9.76k")
      (footprint "eagle-import:R0402")
      (libsource (lib "eagle-import") (part "R-EU_R0402"))
    )
    (comp (ref "RVBST3-1")
      (value "768k")
      (footprint "eagle-import:R0402")
      (libsource (lib "eagle-import") (part "R-EU_R0402"))
    )
    (comp (ref "RVBST3-2")
      (value "9.76k")
      (footprint "eagle-import:R0402")
      (libsource (lib "eagle-import") (part "R-EU_R0402"))
    )
    (comp (ref "RVBST4-1")
      (value "768k")
      (footprint "eagle-import:R0402")
      (libsource (lib "eagle-import") (part "R-EU_R0402"))
    )
    (comp (ref "RVBST4-2")
      (value "9.76k")
      (footprint "eagle-import:R0402")
      (libsource (lib "eagle-import") (part "R-EU_R0402"))
    )
    (comp (ref "RVBST5-1")
      (value "768k")
      (footprint "eagle-import:R0402")
      (libsource (lib "eagle-import") (part "R-EU_R0402"))
    )
    (comp (ref "RVBST5-2")
      (value "9.76k")
      (footprint "eagle-import:R0402")
      (libsource (lib "eagle-import") (part "R-EU_R0402"))
    )
    (comp (ref "RVBST6-1")
      (value "768k")
      (footprint "eagle-import:R0402")
      (libsource (lib "eagle-import") (part "R-EU_R0402"))
    )
    (comp (ref "RVBST6-2")
      (value "9.76k")
      (footprint "eagle-import:R0402")
      (libsource (lib "eagle-import") (part "R-EU_R0402"))
    )
    (comp (ref "RVBST7-1")
      (value "768k")
      (footprint "eagle-import:R0402")
      (libsource (lib "eagle-import") (part "R-EU_R0402"))
    )
    (comp (ref "RVBST7-2")
      (value "9.76k")
      (footprint "eagle-import:R0402")
      (libsource (lib "eagle-import") (part "R-EU_R0402"))
    )
    (comp (ref "RVBST8-1")
      (value "768k")
      (footprint "eagle-import:R0402")
      (libsource (lib "eagle-import") (part "R-EU_R0402"))
    )
    (comp (ref "RVBST8-2")
      (value "9.76k")
      (footprint "eagle-import:R0402")
      (libsource (lib "eagle-import") (part "R-EU_R0402"))
    )
    (comp (ref "ARDUINO_A")
      (value "PINHD-1X15")
      (footprint "eagle-import:1X15")
      (libsource (lib "eagle-import") (part "PINHD-1X15"))
    )
    (comp (ref "ARDUINO_D")
      (value "PINHD-1X15")
      (footprint "eagle-import:1X15")
      (libsource (lib "eagle-import") (part "PINHD-1X15"))
    )
    (comp (ref "AUDIO_IN")
      (value "F25HP")
      (footprint "eagle-import:F25HP")
      (libsource (lib "eagle-import") (part "F25HP"))
    )
    (comp (ref "C_SUP1")
      (value "100u")
      (footprint "eagle-import:EIA3216")
      (libsource (lib "eagle-import") (part "CAP_POL12061"))
    )
    (comp (ref "C_SUP2")
      (value "10u")
      (footprint "eagle-import:C0805K")
      (libsource (lib "eagle-import") (part "C-EUC0805K"))
    )
    (comp (ref "GND_LIFT")
      (value "SWITCH_DPDT")
      (footprint "eagle-import:SWITCH_JS202011")
      (libsource (lib "eagle-import") (part "SWITCH_DPDT"))
    )
    (comp (ref "HEADER_EXT")
      (value "PINHD-1X12")
      (footprint "eagle-import:1X12")
      (libsource (lib "eagle-import") (part "PINHD-1X12"))
    )
    (comp (ref "I2C_SWITCH")
      (value "I2C-SWITCH_8-1TSSOP24")
      (footprint "eagle-import:TSSOP24")
      (libsource (lib "eagle-import") (part "I2C-SWITCH_8-1TSSOP24"))
    )
    (comp (ref "LED1")
      (value "red")
      (footprint "eagle-import:LED-1206")
      (libsource (lib "eagle-import") (part "LED1206"))
    )
    (comp (ref "LED2")
      (value "orange")
      (footprint "eagle-import:LED-1206")
      (libsource (lib "eagle-import") (part "LED1206"))
    )
    (comp (ref "LED3")
      (value "yellow")
      (footprint "eagle-import:LED-1206")
      (libsource (lib "eagle-import") (part "LED1206"))
    )
    (comp (ref "LED_SUP")
      (value "green")
      (footprint "eagle-import:LED-1206")
      (libsource (lib "eagle-import") (part "LED1206"))
    )
    (comp (ref "PWR:")
      (value "LUMBERG-1613-14\"")
      (footprint "eagle-import:LUMBERG-1613_14")
      (libsource (lib "eagle-import") (part "LUMBERG-1613-14{dblquote}"))
    )
    (comp (ref "RLED1")
      (value "1k")
      (footprint "eagle-import:R0402")
      (libsource (lib "eagle-import") (part "R-EU_R0402"))
    )
    (comp (ref "RLED2")
      (value "1k")
      (footprint "eagle-import:R0402")
      (libsource (lib "eagle-import") (part "R-EU_R0402"))
    )
    (comp (ref "RLED3")
      (value "1k")
      (footprint "eagle-import:R0402")
      (libsource (lib "eagle-import") (part "R-EU_R0402"))
    )
    (comp (ref "RLED_SUP")
      (value "10k")
      (footprint "eagle-import:R0402")
      (libsource (lib "eagle-import") (part "R-EU_R0402"))
    )
    (comp (ref "R_CLR")
      (value "4.75k")
      (footprint "eagle-import:R0402")
      (libsource (lib "eagle-import") (part "R-EU_R0402"))
    )
    (comp (ref "R_LIFT1")
      (value "100k")
      (footprint "eagle-import:R0402")
      (libsource (lib "eagle-import") (part "R-EU_R0402"))
    )
    (comp (ref "R_LIFT2")
      (value "100k")
      (footprint "eagle-import:R0402")
      (libsource (lib "eagle-import") (part "R-EU_R0402"))
    )
    (comp (ref "R_LOAD")
      (value "4.75k")
      (footprint "eagle-import:R0402")
      (libsource (lib "eagle-import") (part "R-EU_R0402"))
    )
    (comp (ref "R_OE")
      (value "4.75k")
      (footprint "eagle-import:R0402")
      (libsource (lib "eagle-import") (part "R-EU_R0402"))
    )
    (comp (ref "R_RST")
      (value "4.75k")
      (footprint "eagle-import:R0402")
      (libsource (lib "eagle-import") (part "R-EU_R0402"))
    )
    (comp (ref "R_SCL")
      (value "4.75k")
      (footprint "eagle-import:R0402")
      (libsource (lib "eagle-import") (part "R-EU_R0402"))
    )
    (comp (ref "R_SCL1")
      (value "4.75k")
      (footprint "eagle-import:R0402")
      (libsource (lib "eagle-import") (part "R-EU_R0402"))
    )
    (comp (ref "R_SCL2")
      (value "4.75k")
      (footprint "eagle-import:R0402")
      (libsource (lib "eagle-import") (part "R-EU_R0402"))
    )
    (comp (ref "R_SCL3")
      (value "4.75k")
      (footprint "eagle-import:R0402")
      (libsource (lib "eagle-import") (part "R-EU_R0402"))
    )
    (comp (ref "R_SCL4")
      (value "4.75k")
      (footprint "eagle-import:R0402")
      (libsource (lib "eagle-import") (part "R-EU_R0402"))
    )
    (comp (ref "R_SCL5")
      (value "4.75k")
      (footprint "eagle-import:R0402")
      (libsource (lib "eagle-import") (part "R-EU_R0402"))
    )
    (comp (ref "R_SCL6")
      (value "4.75k")
      (footprint "eagle-import:R0402")
      (libsource (lib "eagle-import") (part "R-EU_R0402"))
    )
    (comp (ref "R_SCL7")
      (value "4.75k")
      (footprint "eagle-import:R0402")
      (libsource (lib "eagle-import") (part "R-EU_R0402"))
    )
    (comp (ref "R_SCL8")
      (value "4.75k")
      (footprint "eagle-import:R0402")
      (libsource (lib "eagle-import") (part "R-EU_R0402"))
    )
    (comp (ref "R_SDA")
      (value "4.75k")
      (footprint "eagle-import:R0402")
      (libsource (lib "eagle-import") (part "R-EU_R0402"))
    )
    (comp (ref "R_SDA1")
      (value "4.75k")
      (footprint "eagle-import:R0402")
      (libsource (lib "eagle-import") (part "R-EU_R0402"))
    )
    (comp (ref "R_SDA2")
      (value "4.75k")
      (footprint "eagle-import:R0402")
      (libsource (lib "eagle-import") (part "R-EU_R0402"))
    )
    (comp (ref "R_SDA3")
      (value "4.75k")
      (footprint "eagle-import:R0402")
      (libsource (lib "eagle-import") (part "R-EU_R0402"))
    )
    (comp (ref "R_SDA4")
      (value "4.75k")
      (footprint "eagle-import:R0402")
      (libsource (lib "eagle-import") (part "R-EU_R0402"))
    )
    (comp (ref "R_SDA5")
      (value "4.75k")
      (footprint "eagle-import:R0402")
      (libsource (lib "eagle-import") (part "R-EU_R0402"))
    )
    (comp (ref "R_SDA6")
      (value "4.75k")
      (footprint "eagle-import:R0402")
      (libsource (lib "eagle-import") (part "R-EU_R0402"))
    )
    (comp (ref "R_SDA7")
      (value "4.75k")
      (footprint "eagle-import:R0402")
      (libsource (lib "eagle-import") (part "R-EU_R0402"))
    )
    (comp (ref "R_SDA8")
      (value "4.75k")
      (footprint "eagle-import:R0402")
      (libsource (lib "eagle-import") (part "R-EU_R0402"))
    )
  )
  (nets
    (net (code "1") (name "+5V") (class "Default")
      (node (ref "ARDUINO_A") (pin "15") (pinfunction "15_15") (pintype "passive"))
      (node (ref "CVDD1") (pin "1") (pinfunction "1_1") (pintype "passive"))
      (node (ref "CVDD2") (pin "1") (pinfunction "1_1") (pintype "passive"))
      (node (ref "CVDD3") (pin "1") (pinfunction "1_1") (pintype "passive"))
      (node (ref "CVDD4") (pin "1") (pinfunction "1_1") (pintype "passive"))
      (node (ref "CVDD5") (pin "1") (pinfunction "1_1") (pintype "passive"))
      (node (ref "CVDD6") (pin "1") (pinfunction "1_1") (pintype "passive"))
      (node (ref "CVDD7") (pin "1") (pinfunction "1_1") (pintype "passive"))
      (node (ref "CVDD8") (pin "1") (pinfunction "1_1") (pintype "passive"))
      (node (ref "C_SUP1") (pin "A") (pinfunction "+_A") (pintype "passive"))
      (node (ref "C_SUP2") (pin "1") (pinfunction "1_1") (pintype "passive"))
      (node (ref "DRV1") (pin "2") (pinfunction "VDD_2") (pintype "bidirectional"))
      (node (ref "DRV2") (pin "2") (pinfunction "VDD_2") (pintype "bidirectional"))
      (node (ref "DRV3") (pin "2") (pinfunction "VDD_2") (pintype "bidirectional"))
      (node (ref "DRV4") (pin "2") (pinfunction "VDD_2") (pintype "bidirectional"))
      (node (ref "DRV5") (pin "2") (pinfunction "VDD_2") (pintype "bidirectional"))
      (node (ref "DRV6") (pin "2") (pinfunction "VDD_2") (pintype "bidirectional"))
      (node (ref "DRV7") (pin "2") (pinfunction "VDD_2") (pintype "bidirectional"))
      (node (ref "DRV8") (pin "2") (pinfunction "VDD_2") (pintype "bidirectional"))
      (node (ref "HEADER_EXT") (pin "2") (pinfunction "2_2") (pintype "passive"))
      (node (ref "I2C_SWITCH") (pin "24") (pinfunction "VDD_24") (pintype "bidirectional"))
      (node (ref "L1") (pin "2") (pinfunction "2_2") (pintype "passive"))
      (node (ref "L2") (pin "2") (pinfunction "2_2") (pintype "passive"))
      (node (ref "L3") (pin "2") (pinfunction "2_2") (pintype "passive"))
      (node (ref "L4") (pin "2") (pinfunction "2_2") (pintype "passive"))
      (node (ref "L5") (pin "2") (pinfunction "2_2") (pintype "passive"))
      (node (ref "L6") (pin "2") (pinfunction "2_2") (pintype "passive"))
      (node (ref "L7") (pin "2") (pinfunction "2_2") (pintype "passive"))
      (node (ref "L8") (pin "2") (pinfunction "2_2") (pintype "passive"))
      (node (ref "LED1") (pin "A") (pinfunction "A_A") (pintype "passive"))
      (node (ref "LED2") (pin "A") (pinfunction "A_A") (pintype "passive"))
      (node (ref "LED3") (pin "A") (pinfunction "A_A") (pintype "passive"))
      (node (ref "PWR:") (pin "3") (pinfunction "PWR_1_3") (pintype "power_in"))
      (node (ref "PWR:") (pin "4") (pinfunction "PWR_2_4") (pintype "power_in"))
      (node (ref "RLED_SUP") (pin "2") (pinfunction "2_2") (pintype "passive"))
      (node (ref "R_1A") (pin "2") (pinfunction "2_2") (pintype "passive"))
      (node (ref "R_1B") (pin "2") (pinfunction "2_2") (pintype "passive"))
      (node (ref "R_1C") (pin "2") (pinfunction "2_2") (pintype "passive"))
      (node (ref "R_1D") (pin "2") (pinfunction "2_2") (pintype "passive"))
      (node (ref "R_1E") (pin "2") (pinfunction "2_2") (pintype "passive"))
      (node (ref "R_1F") (pin "2") (pinfunction "2_2") (pintype "passive"))
      (node (ref "R_1G") (pin "2") (pinfunction "2_2") (pintype "passive"))
      (node (ref "R_1H") (pin "2") (pinfunction "2_2") (pintype "passive"))
      (node (ref "R_1J") (pin "2") (pinfunction "2_2") (pintype "passive"))
      (node (ref "R_2A") (pin "2") (pinfunction "2_2") (pintype "passive"))
      (node (ref "R_2B") (pin "2") (pinfunction "2_2") (pintype "passive"))
      (node (ref "R_2C") (pin "2") (pinfunction "2_2") (pintype "passive"))
      (node (ref "R_2D") (pin "2") (pinfunction "2_2") (pintype "passive"))
      (node (ref "R_2E") (pin "2") (pinfunction "2_2") (pintype "passive"))
      (node (ref "R_2F") (pin "2") (pinfunction "2_2") (pintype "passive"))
      (node (ref "R_2G") (pin "2") (pinfunction "2_2") (pintype "passive"))
      (node (ref "R_2H") (pin "2") (pinfunction "2_2") (pintype "passive"))
      (node (ref "R_2J") (pin "2") (pinfunction "2_2") (pintype "passive"))
      (node (ref "R_3A") (pin "2") (pinfunction "2_2") (pintype "passive"))
      (node (ref "R_3B") (pin "2") (pinfunction "2_2") (pintype "passive"))
      (node (ref "R_3C") (pin "2") (pinfunction "2_2") (pintype "passive"))
      (node (ref "R_3D") (pin "2") (pinfunction "2_2") (pintype "passive"))
      (node (ref "R_3E") (pin "2") (pinfunction "2_2") (pintype "passive"))
      (node (ref "R_3F") (pin "2") (pinfunction "2_2") (pintype "passive"))
      (node (ref "R_3G") (pin "2") (pinfunction "2_2") (pintype "passive"))
      (node (ref "R_3H") (pin "2") (pinfunction "2_2") (pintype "passive"))
      (node (ref "R_3J") (pin "2") (pinfunction "2_2") (pintype "passive"))
      (node (ref "R_4A") (pin "2") (pinfunction "2_2") (pintype "passive"))
      (node (ref "R_4B") (pin "2") (pinfunction "2_2") (pintype "passive"))
      (node (ref "R_4C") (pin "2") (pinfunction "2_2") (pintype "passive"))
      (node (ref "R_4D") (pin "2") (pinfunction "2_2") (pintype "passive"))
      (node (ref "R_4E") (pin "2") (pinfunction "2_2") (pintype "passive"))
      (node (ref "R_4F") (pin "2") (pinfunction "2_2") (pintype "passive"))
      (node (ref "R_4G") (pin "2") (pinfunction "2_2") (pintype "passive"))
      (node (ref "R_4H") (pin "2") (pinfunction "2_2") (pintype "passive"))
      (node (ref "R_4J") (pin "2") (pinfunction "2_2") (pintype "passive"))
      (node (ref "R_5A") (pin "2") (pinfunction "2_2") (pintype "passive"))
      (node (ref "R_5B") (pin "2") (pinfunction "2_2") (pintype "passive"))
      (node (ref "R_5C") (pin "2") (pinfunction "2_2") (pintype "passive"))
      (node (ref "R_5D") (pin "2") (pinfunction "2_2") (pintype "passive"))
      (node (ref "R_5E") (pin "2") (pinfunction "2_2") (pintype "passive"))
      (node (ref "R_5F") (pin "2") (pinfunction "2_2") (pintype "passive"))
      (node (ref "R_5G") (pin "2") (pinfunction "2_2") (pintype "passive"))
      (node (ref "R_5H") (pin "2") (pinfunction "2_2") (pintype "passive"))
      (node (ref "R_5J") (pin "2") (pinfunction "2_2") (pintype "passive"))
      (node (ref "R_6A") (pin "2") (pinfunction "2_2") (pintype "passive"))
      (node (ref "R_6B") (pin "2") (pinfunction "2_2") (pintype "passive"))
      (node (ref "R_6C") (pin "2") (pinfunction "2_2") (pintype "passive"))
      (node (ref "R_6D") (pin "2") (pinfunction "2_2") (pintype "passive"))
      (node (ref "R_6E") (pin "2") (pinfunction "2_2") (pintype "passive"))
      (node (ref "R_6F") (pin "2") (pinfunction "2_2") (pintype "passive"))
      (node (ref "R_6G") (pin "2") (pinfunction "2_2") (pintype "passive"))
      (node (ref "R_6H") (pin "2") (pinfunction "2_2") (pintype "passive"))
      (node (ref "R_6J") (pin "2") (pinfunction "2_2") (pintype "passive"))
      (node (ref "R_7A") (pin "2") (pinfunction "2_2") (pintype "passive"))
      (node (ref "R_7B") (pin "2") (pinfunction "2_2") (pintype "passive"))
      (node (ref "R_7C") (pin "2") (pinfunction "2_2") (pintype "passive"))
      (node (ref "R_7D") (pin "2") (pinfunction "2_2") (pintype "passive"))
      (node (ref "R_7E") (pin "2") (pinfunction "2_2") (pintype "passive"))
      (node (ref "R_7F") (pin "2") (pinfunction "2_2") (pintype "passive"))
      (node (ref "R_7G") (pin "2") (pinfunction "2_2") (pintype "passive"))
      (node (ref "R_7H") (pin "2") (pinfunction "2_2") (pintype "passive"))
      (node (ref "R_7J") (pin "2") (pinfunction "2_2") (pintype "passive"))
      (node (ref "R_8A") (pin "2") (pinfunction "2_2") (pintype "passive"))
      (node (ref "R_8B") (pin "2") (pinfunction "2_2") (pintype "passive"))
      (node (ref "R_8C") (pin "2") (pinfunction "2_2") (pintype "passive"))
      (node (ref "R_8D") (pin "2") (pinfunction "2_2") (pintype "passive"))
      (node (ref "R_8E") (pin "2") (pinfunction "2_2") (pintype "passive"))
      (node (ref "R_8F") (pin "2") (pinfunction "2_2") (pintype "passive"))
      (node (ref "R_8G") (pin "2") (pinfunction "2_2") (pintype "passive"))
      (node (ref "R_8H") (pin "2") (pinfunction "2_2") (pintype "passive"))
      (node (ref "R_8J") (pin "2") (pinfunction "2_2") (pintype "passive"))
      (node (ref "R_CLR") (pin "2") (pinfunction "2_2") (pintype "passive"))
      (node (ref "R_LIFT2") (pin "2") (pinfunction "2_2") (pintype "passive"))
      (node (ref "R_OE") (pin "2") (pinfunction "2_2") (pintype "passive"))
      (node (ref "R_RST") (pin "2") (pinfunction "2_2") (pintype "passive"))
      (node (ref "R_SCL") (pin "2") (pinfunction "2_2") (pintype "passive"))
      (node (ref "R_SCL1") (pin "2") (pinfunction "2_2") (pintype "passive"))
      (node (ref "R_SCL2") (pin "2") (pinfunction "2_2") (pintype "passive"))
      (node (ref "R_SCL3") (pin "2") (pinfunction "2_2") (pintype "passive"))
      (node (ref "R_SCL4") (pin "2") (pinfunction "2_2") (pintype "passive"))
      (node (ref "R_SCL5") (pin "2") (pinfunction "2_2") (pintype "passive"))
      (node (ref "R_SCL6") (pin "2") (pinfunction "2_2") (pintype "passive"))
      (node (ref "R_SCL7") (pin "2") (pinfunction "2_2") (pintype "passive"))
      (node (ref "R_SCL8") (pin "2") (pinfunction "2_2") (pintype "passive"))
      (node (ref "R_SDA") (pin "2") (pinfunction "2_2") (pintype "passive"))
      (node (ref "R_SDA1") (pin "2") (pinfunction "2_2") (pintype "passive"))
      (node (ref "R_SDA2") (pin "2") (pinfunction "2_2") (pintype "passive"))
      (node (ref "R_SDA3") (pin "2") (pinfunction "2_2") (pintype "passive"))
      (node (ref "R_SDA4") (pin "2") (pinfunction "2_2") (pintype "passive"))
      (node (ref "R_SDA5") (pin "2") (pinfunction "2_2") (pintype "passive"))
      (node (ref "R_SDA6") (pin "2") (pinfunction "2_2") (pintype "passive"))
      (node (ref "R_SDA7") (pin "2") (pinfunction "2_2") (pintype "passive"))
      (node (ref "R_SDA8") (pin "2") (pinfunction "2_2") (pintype "passive"))
      (node (ref "SHIFTER0") (pin "16") (pinfunction "VCC_16") (pintype "power_in"))
      (node (ref "SHIFTER1") (pin "16") (pinfunction "VCC_16") (pintype "power_in"))
      (node (ref "SHIFTER2") (pin "16") (pinfunction "VCC_16") (pintype "power_in"))
      (node (ref "SHIFTER3") (pin "16") (pinfunction "VCC_16") (pintype "power_in"))
      (node (ref "SHIFTER4") (pin "16") (pinfunction "VCC_16") (pintype "power_in"))
      (node (ref "SHIFTER5") (pin "16") (pinfunction "VCC_16") (pintype "power_in"))
      (node (ref "SHIFTER6") (pin "16") (pinfunction "VCC_16") (pintype "power_in"))
      (node (ref "SHIFTER7") (pin "16") (pinfunction "VCC_16") (pintype "power_in"))
      (node (ref "SHIFTER8") (pin "16") (pinfunction "VCC_16") (pintype "power_in"))
    )
    (net (code "2") (name "0V") (class "Default")
      (node (ref "ARDUINO_A") (pin "14") (pinfunction "14_14") (pintype "passive"))
      (node (ref "ARDUINO_D") (pin "12") (pinfunction "12_12") (pintype "passive"))
      (node (ref "AUDIO_IN") (pin "G1") (pinfunction "G1_G1") (pintype "passive"))
      (node (ref "AUDIO_IN") (pin "G2") (pinfunction "G2_G2") (pintype "passive"))
      (node (ref "CPUMP1") (pin "2") (pinfunction "2_2") (pintype "passive"))
      (node (ref "CPUMP2") (pin "2") (pinfunction "2_2") (pintype "passive"))
      (node (ref "CPUMP3") (pin "2") (pinfunction "2_2") (pintype "passive"))
      (node (ref "CPUMP4") (pin "2") (pinfunction "2_2") (pintype "passive"))
      (node (ref "CPUMP5") (pin "2") (pinfunction "2_2") (pintype "passive"))
      (node (ref "CPUMP6") (pin "2") (pinfunction "2_2") (pintype "passive"))
      (node (ref "CPUMP7") (pin "2") (pinfunction "2_2") (pintype "passive"))
      (node (ref "CPUMP8") (pin "2") (pinfunction "2_2") (pintype "passive"))
      (node (ref "CVBST1") (pin "2") (pinfunction "2_2") (pintype "passive"))
      (node (ref "CVBST2") (pin "2") (pinfunction "2_2") (pintype "passive"))
      (node (ref "CVBST3") (pin "2") (pinfunction "2_2") (pintype "passive"))
      (node (ref "CVBST4") (pin "2") (pinfunction "2_2") (pintype "passive"))
      (node (ref "CVBST5") (pin "2") (pinfunction "2_2") (pintype "passive"))
      (node (ref "CVBST6") (pin "2") (pinfunction "2_2") (pintype "passive"))
      (node (ref "CVBST7") (pin "2") (pinfunction "2_2") (pintype "passive"))
      (node (ref "CVBST8") (pin "2") (pinfunction "2_2") (pintype "passive"))
      (node (ref "CVDD1") (pin "2") (pinfunction "2_2") (pintype "passive"))
      (node (ref "CVDD2") (pin "2") (pinfunction "2_2") (pintype "passive"))
      (node (ref "CVDD3") (pin "2") (pinfunction "2_2") (pintype "passive"))
      (node (ref "CVDD4") (pin "2") (pinfunction "2_2") (pintype "passive"))
      (node (ref "CVDD5") (pin "2") (pinfunction "2_2") (pintype "passive"))
      (node (ref "CVDD6") (pin "2") (pinfunction "2_2") (pintype "passive"))
      (node (ref "CVDD7") (pin "2") (pinfunction "2_2") (pintype "passive"))
      (node (ref "CVDD8") (pin "2") (pinfunction "2_2") (pintype "passive"))
      (node (ref "CVREG1") (pin "2") (pinfunction "2_2") (pintype "passive"))
      (node (ref "CVREG2") (pin "2") (pinfunction "2_2") (pintype "passive"))
      (node (ref "CVREG3") (pin "2") (pinfunction "2_2") (pintype "passive"))
      (node (ref "CVREG4") (pin "2") (pinfunction "2_2") (pintype "passive"))
      (node (ref "CVREG5") (pin "2") (pinfunction "2_2") (pintype "passive"))
      (node (ref "CVREG6") (pin "2") (pinfunction "2_2") (pintype "passive"))
      (node (ref "CVREG7") (pin "2") (pinfunction "2_2") (pintype "passive"))
      (node (ref "CVREG8") (pin "2") (pinfunction "2_2") (pintype "passive"))
      (node (ref "C_SUP1") (pin "C") (pinfunction "-_C") (pintype "passive"))
      (node (ref "C_SUP2") (pin "2") (pinfunction "2_2") (pintype "passive"))
      (node (ref "DRV1") (pin "4") (pinfunction "GND_4") (pintype "bidirectional"))
      (node (ref "DRV1") (pin "5") (pinfunction "GND_5") (pintype "bidirectional"))
      (node (ref "DRV1") (pin "6") (pinfunction "GND_6") (pintype "bidirectional"))
      (node (ref "DRV1") (pin "PAD1") (pinfunction "PAD_PAD1") (pintype "bidirectional"))
      (node (ref "DRV1") (pin "PAD2") (pinfunction "PAD_PAD2") (pintype "bidirectional"))
      (node (ref "DRV1") (pin "PAD3") (pinfunction "PAD_PAD3") (pintype "bidirectional"))
      (node (ref "DRV1") (pin "PAD4") (pinfunction "PAD_PAD4") (pintype "bidirectional"))
      (node (ref "DRV1") (pin "PAD5") (pinfunction "PAD_PAD5") (pintype "bidirectional"))
      (node (ref "DRV1") (pin "PAD6") (pinfunction "PAD_PAD6") (pintype "bidirectional"))
      (node (ref "DRV1") (pin "PAD7") (pinfunction "PAD_PAD7") (pintype "bidirectional"))
      (node (ref "DRV1") (pin "PAD8") (pinfunction "PAD_PAD8") (pintype "bidirectional"))
      (node (ref "DRV1") (pin "PAD9") (pinfunction "PAD_PAD9") (pintype "bidirectional"))
      (node (ref "DRV2") (pin "4") (pinfunction "GND_4") (pintype "bidirectional"))
      (node (ref "DRV2") (pin "5") (pinfunction "GND_5") (pintype "bidirectional"))
      (node (ref "DRV2") (pin "6") (pinfunction "GND_6") (pintype "bidirectional"))
      (node (ref "DRV2") (pin "PAD1") (pinfunction "PAD_PAD1") (pintype "bidirectional"))
      (node (ref "DRV2") (pin "PAD2") (pinfunction "PAD_PAD2") (pintype "bidirectional"))
      (node (ref "DRV2") (pin "PAD3") (pinfunction "PAD_PAD3") (pintype "bidirectional"))
      (node (ref "DRV2") (pin "PAD4") (pinfunction "PAD_PAD4") (pintype "bidirectional"))
      (node (ref "DRV2") (pin "PAD5") (pinfunction "PAD_PAD5") (pintype "bidirectional"))
      (node (ref "DRV2") (pin "PAD6") (pinfunction "PAD_PAD6") (pintype "bidirectional"))
      (node (ref "DRV2") (pin "PAD7") (pinfunction "PAD_PAD7") (pintype "bidirectional"))
      (node (ref "DRV2") (pin "PAD8") (pinfunction "PAD_PAD8") (pintype "bidirectional"))
      (node (ref "DRV2") (pin "PAD9") (pinfunction "PAD_PAD9") (pintype "bidirectional"))
      (node (ref "DRV3") (pin "4") (pinfunction "GND_4") (pintype "bidirectional"))
      (node (ref "DRV3") (pin "5") (pinfunction "GND_5") (pintype "bidirectional"))
      (node (ref "DRV3") (pin "6") (pinfunction "GND_6") (pintype "bidirectional"))
      (node (ref "DRV3") (pin "PAD1") (pinfunction "PAD_PAD1") (pintype "bidirectional"))
      (node (ref "DRV3") (pin "PAD2") (pinfunction "PAD_PAD2") (pintype "bidirectional"))
      (node (ref "DRV3") (pin "PAD3") (pinfunction "PAD_PAD3") (pintype "bidirectional"))
      (node (ref "DRV3") (pin "PAD4") (pinfunction "PAD_PAD4") (pintype "bidirectional"))
      (node (ref "DRV3") (pin "PAD5") (pinfunction "PAD_PAD5") (pintype "bidirectional"))
      (node (ref "DRV3") (pin "PAD6") (pinfunction "PAD_PAD6") (pintype "bidirectional"))
      (node (ref "DRV3") (pin "PAD7") (pinfunction "PAD_PAD7") (pintype "bidirectional"))
      (node (ref "DRV3") (pin "PAD8") (pinfunction "PAD_PAD8") (pintype "bidirectional"))
      (node (ref "DRV3") (pin "PAD9") (pinfunction "PAD_PAD9") (pintype "bidirectional"))
      (node (ref "DRV4") (pin "4") (pinfunction "GND_4") (pintype "bidirectional"))
      (node (ref "DRV4") (pin "5") (pinfunction "GND_5") (pintype "bidirectional"))
      (node (ref "DRV4") (pin "6") (pinfunction "GND_6") (pintype "bidirectional"))
      (node (ref "DRV4") (pin "PAD1") (pinfunction "PAD_PAD1") (pintype "bidirectional"))
      (node (ref "DRV4") (pin "PAD2") (pinfunction "PAD_PAD2") (pintype "bidirectional"))
      (node (ref "DRV4") (pin "PAD3") (pinfunction "PAD_PAD3") (pintype "bidirectional"))
      (node (ref "DRV4") (pin "PAD4") (pinfunction "PAD_PAD4") (pintype "bidirectional"))
      (node (ref "DRV4") (pin "PAD5") (pinfunction "PAD_PAD5") (pintype "bidirectional"))
      (node (ref "DRV4") (pin "PAD6") (pinfunction "PAD_PAD6") (pintype "bidirectional"))
      (node (ref "DRV4") (pin "PAD7") (pinfunction "PAD_PAD7") (pintype "bidirectional"))
      (node (ref "DRV4") (pin "PAD8") (pinfunction "PAD_PAD8") (pintype "bidirectional"))
      (node (ref "DRV4") (pin "PAD9") (pinfunction "PAD_PAD9") (pintype "bidirectional"))
      (node (ref "DRV5") (pin "4") (pinfunction "GND_4") (pintype "bidirectional"))
      (node (ref "DRV5") (pin "5") (pinfunction "GND_5") (pintype "bidirectional"))
      (node (ref "DRV5") (pin "6") (pinfunction "GND_6") (pintype "bidirectional"))
      (node (ref "DRV5") (pin "PAD1") (pinfunction "PAD_PAD1") (pintype "bidirectional"))
      (node (ref "DRV5") (pin "PAD2") (pinfunction "PAD_PAD2") (pintype "bidirectional"))
      (node (ref "DRV5") (pin "PAD3") (pinfunction "PAD_PAD3") (pintype "bidirectional"))
      (node (ref "DRV5") (pin "PAD4") (pinfunction "PAD_PAD4") (pintype "bidirectional"))
      (node (ref "DRV5") (pin "PAD5") (pinfunction "PAD_PAD5") (pintype "bidirectional"))
      (node (ref "DRV5") (pin "PAD6") (pinfunction "PAD_PAD6") (pintype "bidirectional"))
      (node (ref "DRV5") (pin "PAD7") (pinfunction "PAD_PAD7") (pintype "bidirectional"))
      (node (ref "DRV5") (pin "PAD8") (pinfunction "PAD_PAD8") (pintype "bidirectional"))
      (node (ref "DRV5") (pin "PAD9") (pinfunction "PAD_PAD9") (pintype "bidirectional"))
      (node (ref "DRV6") (pin "4") (pinfunction "GND_4") (pintype "bidirectional"))
      (node (ref "DRV6") (pin "5") (pinfunction "GND_5") (pintype "bidirectional"))
      (node (ref "DRV6") (pin "6") (pinfunction "GND_6") (pintype "bidirectional"))
      (node (ref "DRV6") (pin "PAD1") (pinfunction "PAD_PAD1") (pintype "bidirectional"))
      (node (ref "DRV6") (pin "PAD2") (pinfunction "PAD_PAD2") (pintype "bidirectional"))
      (node (ref "DRV6") (pin "PAD3") (pinfunction "PAD_PAD3") (pintype "bidirectional"))
      (node (ref "DRV6") (pin "PAD4") (pinfunction "PAD_PAD4") (pintype "bidirectional"))
      (node (ref "DRV6") (pin "PAD5") (pinfunction "PAD_PAD5") (pintype "bidirectional"))
      (node (ref "DRV6") (pin "PAD6") (pinfunction "PAD_PAD6") (pintype "bidirectional"))
      (node (ref "DRV6") (pin "PAD7") (pinfunction "PAD_PAD7") (pintype "bidirectional"))
      (node (ref "DRV6") (pin "PAD8") (pinfunction "PAD_PAD8") (pintype "bidirectional"))
      (node (ref "DRV6") (pin "PAD9") (pinfunction "PAD_PAD9") (pintype "bidirectional"))
      (node (ref "DRV7") (pin "4") (pinfunction "GND_4") (pintype "bidirectional"))
      (node (ref "DRV7") (pin "5") (pinfunction "GND_5") (pintype "bidirectional"))
      (node (ref "DRV7") (pin "6") (pinfunction "GND_6") (pintype "bidirectional"))
      (node (ref "DRV7") (pin "PAD1") (pinfunction "PAD_PAD1") (pintype "bidirectional"))
      (node (ref "DRV7") (pin "PAD2") (pinfunction "PAD_PAD2") (pintype "bidirectional"))
      (node (ref "DRV7") (pin "PAD3") (pinfunction "PAD_PAD3") (pintype "bidirectional"))
      (node (ref "DRV7") (pin "PAD4") (pinfunction "PAD_PAD4") (pintype "bidirectional"))
      (node (ref "DRV7") (pin "PAD5") (pinfunction "PAD_PAD5") (pintype "bidirectional"))
      (node (ref "DRV7") (pin "PAD6") (pinfunction "PAD_PAD6") (pintype "bidirectional"))
      (node (ref "DRV7") (pin "PAD7") (pinfunction "PAD_PAD7") (pintype "bidirectional"))
      (node (ref "DRV7") (pin "PAD8") (pinfunction "PAD_PAD8") (pintype "bidirectional"))
      (node (ref "DRV7") (pin "PAD9") (pinfunction "PAD_PAD9") (pintype "bidirectional"))
      (node (ref "DRV8") (pin "4") (pinfunction "GND_4") (pintype "bidirectional"))
      (node (ref "DRV8") (pin "5") (pinfunction "GND_5") (pintype "bidirectional"))
      (node (ref "DRV8") (pin "6") (pinfunction "GND_6") (pintype "bidirectional"))
      (node (ref "DRV8") (pin "PAD1") (pinfunction "PAD_PAD1") (pintype "bidirectional"))
      (node (ref "DRV8") (pin "PAD2") (pinfunction "PAD_PAD2") (pintype "bidirectional"))
      (node (ref "DRV8") (pin "PAD3") (pinfunction "PAD_PAD3") (pintype "bidirectional"))
      (node (ref "DRV8") (pin "PAD4") (pinfunction "PAD_PAD4") (pintype "bidirectional"))
      (node (ref "DRV8") (pin "PAD5") (pinfunction "PAD_PAD5") (pintype "bidirectional"))
      (node (ref "DRV8") (pin "PAD6") (pinfunction "PAD_PAD6") (pintype "bidirectional"))
      (node (ref "DRV8") (pin "PAD7") (pinfunction "PAD_PAD7") (pintype "bidirectional"))
      (node (ref "DRV8") (pin "PAD8") (pinfunction "PAD_PAD8") (pintype "bidirectional"))
      (node (ref "DRV8") (pin "PAD9") (pinfunction "PAD_PAD9") (pintype "bidirectional"))
      (node (ref "HEADER_EXT") (pin "1") (pinfunction "1_1") (pintype "passive"))
      (node (ref "HEADER_EXT") (pin "12") (pinfunction "12_12") (pintype "passive"))
      (node (ref "I2C_SWITCH") (pin "12") (pinfunction "VSS_12") (pintype "bidirectional"))
      (node (ref "LED_SUP") (pin "C") (pinfunction "C_C") (pintype "passive"))
      (node (ref "PWR:") (pin "1") (pinfunction "GND_1") (pintype "power_in"))
      (node (ref "PWR:") (pin "2") (pinfunction "GND_INS_2") (pintype "power_in"))
      (node (ref "REXT1") (pin "1") (pinfunction "1_1") (pintype "passive"))
      (node (ref "REXT2") (pin "1") (pinfunction "1_1") (pintype "passive"))
      (node (ref "REXT3") (pin "1") (pinfunction "1_1") (pintype "passive"))
      (node (ref "REXT4") (pin "1") (pinfunction "1_1") (pintype "passive"))
      (node (ref "REXT5") (pin "1") (pinfunction "1_1") (pintype "passive"))
      (node (ref "REXT6") (pin "1") (pinfunction "1_1") (pintype "passive"))
      (node (ref "REXT7") (pin "1") (pinfunction "1_1") (pintype "passive"))
      (node (ref "REXT8") (pin "1") (pinfunction "1_1") (pintype "passive"))
      (node (ref "RVBST1-2") (pin "1") (pinfunction "1_1") (pintype "passive"))
      (node (ref "RVBST2-2") (pin "1") (pinfunction "1_1") (pintype "passive"))
      (node (ref "RVBST3-2") (pin "1") (pinfunction "1_1") (pintype "passive"))
      (node (ref "RVBST4-2") (pin "1") (pinfunction "1_1") (pintype "passive"))
      (node (ref "RVBST5-2") (pin "1") (pinfunction "1_1") (pintype "passive"))
      (node (ref "RVBST6-2") (pin "1") (pinfunction "1_1") (pintype "passive"))
      (node (ref "RVBST7-2") (pin "1") (pinfunction "1_1") (pintype "passive"))
      (node (ref "RVBST8-2") (pin "1") (pinfunction "1_1") (pintype "passive"))
      (node (ref "R_LIFT1") (pin "1") (pinfunction "1_1") (pintype "passive"))
      (node (ref "R_LOAD") (pin "1") (pinfunction "1_1") (pintype "passive"))
      (node (ref "SHIFTER0") (pin "8") (pinfunction "GND_8") (pintype "power_in"))
      (node (ref "SHIFTER0") (pin "PAD") (pinfunction "GND_PAD") (pintype "power_in"))
      (node (ref "SHIFTER1") (pin "8") (pinfunction "GND_8") (pintype "power_in"))
      (node (ref "SHIFTER1") (pin "PAD") (pinfunction "GND_PAD") (pintype "power_in"))
      (node (ref "SHIFTER2") (pin "8") (pinfunction "GND_8") (pintype "power_in"))
      (node (ref "SHIFTER2") (pin "PAD") (pinfunction "GND_PAD") (pintype "power_in"))
      (node (ref "SHIFTER3") (pin "8") (pinfunction "GND_8") (pintype "power_in"))
      (node (ref "SHIFTER3") (pin "PAD") (pinfunction "GND_PAD") (pintype "power_in"))
      (node (ref "SHIFTER4") (pin "8") (pinfunction "GND_8") (pintype "power_in"))
      (node (ref "SHIFTER4") (pin "PAD") (pinfunction "GND_PAD") (pintype "power_in"))
      (node (ref "SHIFTER5") (pin "8") (pinfunction "GND_8") (pintype "power_in"))
      (node (ref "SHIFTER5") (pin "PAD") (pinfunction "GND_PAD") (pintype "power_in"))
      (node (ref "SHIFTER6") (pin "8") (pinfunction "GND_8") (pintype "power_in"))
      (node (ref "SHIFTER6") (pin "PAD") (pinfunction "GND_PAD") (pintype "power_in"))
      (node (ref "SHIFTER7") (pin "8") (pinfunction "GND_8") (pintype "power_in"))
      (node (ref "SHIFTER7") (pin "PAD") (pinfunction "GND_PAD") (pintype "power_in"))
      (node (ref "SHIFTER8") (pin "8") (pinfunction "GND_8") (pintype "power_in"))
      (node (ref "SHIFTER8") (pin "PAD") (pinfunction "GND_PAD") (pintype "power_in"))
    )
    (net (code "3") (name "CH1_I+") (class "Default")
      (node (ref "AUDIO_IN") (pin "24") (pinfunction "24_24") (pintype "passive"))
      (node (ref "DRV1") (pin "17") (pinfunction "IN+_17") (pintype "bidirectional"))
    )
    (net (code "4") (name "CH1_I-") (class "Default")
      (node (ref "AUDIO_IN") (pin "12") (pinfunction "12_12") (pintype "passive"))
      (node (ref "DRV1") (pin "16") (pinfunction "IN-_16") (pintype "bidirectional"))
    )
    (net (code "5") (name "CH1_O+") (class "Default")
      (node (ref "DRV1") (pin "13") (pinfunction "OUT+_13") (pintype "bidirectional"))
      (node (ref "SSR_1AB") (pin "5") (pinfunction "O1_5") (pintype "bidirectional"))
      (node (ref "SSR_1AB") (pin "7") (pinfunction "O1_7") (pintype "bidirectional"))
      (node (ref "SSR_1CD") (pin "5") (pinfunction "O1_5") (pintype "bidirectional"))
      (node (ref "SSR_1CD") (pin "7") (pinfunction "O1_7") (pintype "bidirectional"))
      (node (ref "SSR_1EF") (pin "5") (pinfunction "O1_5") (pintype "bidirectional"))
      (node (ref "SSR_1EF") (pin "7") (pinfunction "O1_7") (pintype "bidirectional"))
      (node (ref "SSR_1GH") (pin "5") (pinfunction "O1_5") (pintype "bidirectional"))
      (node (ref "SSR_1GH") (pin "7") (pinfunction "O1_7") (pintype "bidirectional"))
      (node (ref "SSR_1J/2A") (pin "7") (pinfunction "O1_7") (pintype "bidirectional"))
    )
    (net (code "6") (name "CH1_O-") (class "Default")
      (node (ref "DRV1") (pin "14") (pinfunction "OUT-_14") (pintype "bidirectional"))
      (node (ref "P-CH1+2") (pin "12") (pinfunction "1_12") (pintype "passive"))
      (node (ref "P-CH1+2") (pin "18") (pinfunction "1_18") (pintype "passive"))
    )
    (net (code "7") (name "CH1_PA+") (class "Default")
      (node (ref "P-CH1+2") (pin "22") (pinfunction "1_22") (pintype "passive"))
      (node (ref "SSR_1AB") (pin "8") (pinfunction "O2_8") (pintype "bidirectional"))
    )
    (net (code "8") (name "CH1_PB+") (class "Default")
      (node (ref "P-CH1+2") (pin "21") (pinfunction "1_21") (pintype "passive"))
      (node (ref "SSR_1AB") (pin "6") (pinfunction "O2_6") (pintype "bidirectional"))
    )
    (net (code "9") (name "CH1_PC+") (class "Default")
      (node (ref "P-CH1+2") (pin "20") (pinfunction "1_20") (pintype "passive"))
      (node (ref "SSR_1CD") (pin "8") (pinfunction "O2_8") (pintype "bidirectional"))
    )
    (net (code "10") (name "CH1_PD+") (class "Default")
      (node (ref "P-CH1+2") (pin "19") (pinfunction "1_19") (pintype "passive"))
      (node (ref "SSR_1CD") (pin "6") (pinfunction "O2_6") (pintype "bidirectional"))
    )
    (net (code "11") (name "CH1_PE+") (class "Default")
      (node (ref "P-CH1+2") (pin "17") (pinfunction "1_17") (pintype "passive"))
      (node (ref "SSR_1EF") (pin "8") (pinfunction "O2_8") (pintype "bidirectional"))
    )
    (net (code "12") (name "CH1_PF+") (class "Default")
      (node (ref "P-CH1+2") (pin "16") (pinfunction "1_16") (pintype "passive"))
      (node (ref "SSR_1EF") (pin "6") (pinfunction "O2_6") (pintype "bidirectional"))
    )
    (net (code "13") (name "CH1_PG+") (class "Default")
      (node (ref "P-CH1+2") (pin "15") (pinfunction "1_15") (pintype "passive"))
      (node (ref "SSR_1GH") (pin "8") (pinfunction "O2_8") (pintype "bidirectional"))
    )
    (net (code "14") (name "CH1_PH+") (class "Default")
      (node (ref "P-CH1+2") (pin "14") (pinfunction "1_14") (pintype "passive"))
      (node (ref "SSR_1GH") (pin "6") (pinfunction "O2_6") (pintype "bidirectional"))
    )
    (net (code "15") (name "CH1_PJ+") (class "Default")
      (node (ref "P-CH1+2") (pin "13") (pinfunction "1_13") (pintype "passive"))
      (node (ref "SSR_1J/2A") (pin "8") (pinfunction "O2_8") (pintype "bidirectional"))
    )
    (net (code "16") (name "CH2_I+") (class "Default")
      (node (ref "AUDIO_IN") (pin "10") (pinfunction "10_10") (pintype "passive"))
      (node (ref "DRV2") (pin "17") (pinfunction "IN+_17") (pintype "bidirectional"))
    )
    (net (code "17") (name "CH2_I-") (class "Default")
      (node (ref "AUDIO_IN") (pin "23") (pinfunction "23_23") (pintype "passive"))
      (node (ref "DRV2") (pin "16") (pinfunction "IN-_16") (pintype "bidirectional"))
    )
    (net (code "18") (name "CH2_O+") (class "Default")
      (node (ref "DRV2") (pin "13") (pinfunction "OUT+_13") (pintype "bidirectional"))
      (node (ref "SSR_1J/2A") (pin "5") (pinfunction "O1_5") (pintype "bidirectional"))
      (node (ref "SSR_2BC") (pin "5") (pinfunction "O1_5") (pintype "bidirectional"))
      (node (ref "SSR_2BC") (pin "7") (pinfunction "O1_7") (pintype "bidirectional"))
      (node (ref "SSR_2DE") (pin "5") (pinfunction "O1_5") (pintype "bidirectional"))
      (node (ref "SSR_2DE") (pin "7") (pinfunction "O1_7") (pintype "bidirectional"))
      (node (ref "SSR_2FG") (pin "5") (pinfunction "O1_5") (pintype "bidirectional"))
      (node (ref "SSR_2FG") (pin "7") (pinfunction "O1_7") (pintype "bidirectional"))
      (node (ref "SSR_2HJ") (pin "5") (pinfunction "O1_5") (pintype "bidirectional"))
      (node (ref "SSR_2HJ") (pin "7") (pinfunction "O1_7") (pintype "bidirectional"))
    )
    (net (code "19") (name "CH2_O-") (class "Default")
      (node (ref "DRV2") (pin "14") (pinfunction "OUT-_14") (pintype "bidirectional"))
      (node (ref "P-CH1+2") (pin "1") (pinfunction "1_1") (pintype "passive"))
      (node (ref "P-CH1+2") (pin "7") (pinfunction "1_7") (pintype "passive"))
    )
    (net (code "20") (name "CH2_PA+") (class "Default")
      (node (ref "P-CH1+2") (pin "11") (pinfunction "1_11") (pintype "passive"))
      (node (ref "SSR_1J/2A") (pin "6") (pinfunction "O2_6") (pintype "bidirectional"))
    )
    (net (code "21") (name "CH2_PB+") (class "Default")
      (node (ref "P-CH1+2") (pin "10") (pinfunction "1_10") (pintype "passive"))
      (node (ref "SSR_2BC") (pin "8") (pinfunction "O2_8") (pintype "bidirectional"))
    )
    (net (code "22") (name "CH2_PC+") (class "Default")
      (node (ref "P-CH1+2") (pin "9") (pinfunction "1_9") (pintype "passive"))
      (node (ref "SSR_2BC") (pin "6") (pinfunction "O2_6") (pintype "bidirectional"))
    )
    (net (code "23") (name "CH2_PD+") (class "Default")
      (node (ref "P-CH1+2") (pin "8") (pinfunction "1_8") (pintype "passive"))
      (node (ref "SSR_2DE") (pin "8") (pinfunction "O2_8") (pintype "bidirectional"))
    )
    (net (code "24") (name "CH2_PE+") (class "Default")
      (node (ref "P-CH1+2") (pin "6") (pinfunction "1_6") (pintype "passive"))
      (node (ref "SSR_2DE") (pin "6") (pinfunction "O2_6") (pintype "bidirectional"))
    )
    (net (code "25") (name "CH2_PF+") (class "Default")
      (node (ref "P-CH1+2") (pin "5") (pinfunction "1_5") (pintype "passive"))
      (node (ref "SSR_2FG") (pin "8") (pinfunction "O2_8") (pintype "bidirectional"))
    )
    (net (code "26") (name "CH2_PG+") (class "Default")
      (node (ref "P-CH1+2") (pin "4") (pinfunction "1_4") (pintype "passive"))
      (node (ref "SSR_2FG") (pin "6") (pinfunction "O2_6") (pintype "bidirectional"))
    )
    (net (code "27") (name "CH2_PH+") (class "Default")
      (node (ref "P-CH1+2") (pin "3") (pinfunction "1_3") (pintype "passive"))
      (node (ref "SSR_2HJ") (pin "8") (pinfunction "O2_8") (pintype "bidirectional"))
    )
    (net (code "28") (name "CH2_PJ+") (class "Default")
      (node (ref "P-CH1+2") (pin "2") (pinfunction "1_2") (pintype "passive"))
      (node (ref "SSR_2HJ") (pin "6") (pinfunction "O2_6") (pintype "bidirectional"))
    )
    (net (code "29") (name "CH3_I+") (class "Default")
      (node (ref "AUDIO_IN") (pin "21") (pinfunction "21_21") (pintype "passive"))
      (node (ref "DRV3") (pin "17") (pinfunction "IN+_17") (pintype "bidirectional"))
    )
    (net (code "30") (name "CH3_I-") (class "Default")
      (node (ref "AUDIO_IN") (pin "9") (pinfunction "9_9") (pintype "passive"))
      (node (ref "DRV3") (pin "16") (pinfunction "IN-_16") (pintype "bidirectional"))
    )
    (net (code "31") (name "CH3_O+") (class "Default")
      (node (ref "DRV3") (pin "13") (pinfunction "OUT+_13") (pintype "bidirectional"))
      (node (ref "SSR_3AB") (pin "5") (pinfunction "O1_5") (pintype "bidirectional"))
      (node (ref "SSR_3AB") (pin "7") (pinfunction "O1_7") (pintype "bidirectional"))
      (node (ref "SSR_3CD") (pin "5") (pinfunction "O1_5") (pintype "bidirectional"))
      (node (ref "SSR_3CD") (pin "7") (pinfunction "O1_7") (pintype "bidirectional"))
      (node (ref "SSR_3EF") (pin "5") (pinfunction "O1_5") (pintype "bidirectional"))
      (node (ref "SSR_3EF") (pin "7") (pinfunction "O1_7") (pintype "bidirectional"))
      (node (ref "SSR_3GH") (pin "5") (pinfunction "O1_5") (pintype "bidirectional"))
      (node (ref "SSR_3GH") (pin "7") (pinfunction "O1_7") (pintype "bidirectional"))
      (node (ref "SSR_3J/4A") (pin "7") (pinfunction "O1_7") (pintype "bidirectional"))
    )
    (net (code "32") (name "CH3_O-") (class "Default")
      (node (ref "DRV3") (pin "14") (pinfunction "OUT-_14") (pintype "bidirectional"))
      (node (ref "P-CH3+4") (pin "12") (pinfunction "1_12") (pintype "passive"))
      (node (ref "P-CH3+4") (pin "18") (pinfunction "1_18") (pintype "passive"))
    )
    (net (code "33") (name "CH3_PA+") (class "Default")
      (node (ref "P-CH3+4") (pin "22") (pinfunction "1_22") (pintype "passive"))
      (node (ref "SSR_3AB") (pin "8") (pinfunction "O2_8") (pintype "bidirectional"))
    )
    (net (code "34") (name "CH3_PB+") (class "Default")
      (node (ref "P-CH3+4") (pin "21") (pinfunction "1_21") (pintype "passive"))
      (node (ref "SSR_3AB") (pin "6") (pinfunction "O2_6") (pintype "bidirectional"))
    )
    (net (code "35") (name "CH3_PC+") (class "Default")
      (node (ref "P-CH3+4") (pin "20") (pinfunction "1_20") (pintype "passive"))
      (node (ref "SSR_3CD") (pin "8") (pinfunction "O2_8") (pintype "bidirectional"))
    )
    (net (code "36") (name "CH3_PD+") (class "Default")
      (node (ref "P-CH3+4") (pin "19") (pinfunction "1_19") (pintype "passive"))
      (node (ref "SSR_3CD") (pin "6") (pinfunction "O2_6") (pintype "bidirectional"))
    )
    (net (code "37") (name "CH3_PE+") (class "Default")
      (node (ref "P-CH3+4") (pin "17") (pinfunction "1_17") (pintype "passive"))
      (node (ref "SSR_3EF") (pin "8") (pinfunction "O2_8") (pintype "bidirectional"))
    )
    (net (code "38") (name "CH3_PF+") (class "Default")
      (node (ref "P-CH3+4") (pin "16") (pinfunction "1_16") (pintype "passive"))
      (node (ref "SSR_3EF") (pin "6") (pinfunction "O2_6") (pintype "bidirectional"))
    )
    (net (code "39") (name "CH3_PG+") (class "Default")
      (node (ref "P-CH3+4") (pin "15") (pinfunction "1_15") (pintype "passive"))
      (node (ref "SSR_3GH") (pin "8") (pinfunction "O2_8") (pintype "bidirectional"))
    )
    (net (code "40") (name "CH3_PH+") (class "Default")
      (node (ref "P-CH3+4") (pin "14") (pinfunction "1_14") (pintype "passive"))
      (node (ref "SSR_3GH") (pin "6") (pinfunction "O2_6") (pintype "bidirectional"))
    )
    (net (code "41") (name "CH3_PJ+") (class "Default")
      (node (ref "P-CH3+4") (pin "13") (pinfunction "1_13") (pintype "passive"))
      (node (ref "SSR_3J/4A") (pin "8") (pinfunction "O2_8") (pintype "bidirectional"))
    )
    (net (code "42") (name "CH4_I+") (class "Default")
      (node (ref "AUDIO_IN") (pin "7") (pinfunction "7_7") (pintype "passive"))
      (node (ref "DRV4") (pin "17") (pinfunction "IN+_17") (pintype "bidirectional"))
    )
    (net (code "43") (name "CH4_I-") (class "Default")
      (node (ref "AUDIO_IN") (pin "20") (pinfunction "20_20") (pintype "passive"))
      (node (ref "DRV4") (pin "16") (pinfunction "IN-_16") (pintype "bidirectional"))
    )
    (net (code "44") (name "CH4_O+") (class "Default")
      (node (ref "DRV4") (pin "13") (pinfunction "OUT+_13") (pintype "bidirectional"))
      (node (ref "SSR_3J/4A") (pin "5") (pinfunction "O1_5") (pintype "bidirectional"))
      (node (ref "SSR_4BC") (pin "5") (pinfunction "O1_5") (pintype "bidirectional"))
      (node (ref "SSR_4BC") (pin "7") (pinfunction "O1_7") (pintype "bidirectional"))
      (node (ref "SSR_4DE") (pin "5") (pinfunction "O1_5") (pintype "bidirectional"))
      (node (ref "SSR_4DE") (pin "7") (pinfunction "O1_7") (pintype "bidirectional"))
      (node (ref "SSR_4FG") (pin "5") (pinfunction "O1_5") (pintype "bidirectional"))
      (node (ref "SSR_4FG") (pin "7") (pinfunction "O1_7") (pintype "bidirectional"))
      (node (ref "SSR_4HJ") (pin "5") (pinfunction "O1_5") (pintype "bidirectional"))
      (node (ref "SSR_4HJ") (pin "7") (pinfunction "O1_7") (pintype "bidirectional"))
    )
    (net (code "45") (name "CH4_O-") (class "Default")
      (node (ref "DRV4") (pin "14") (pinfunction "OUT-_14") (pintype "bidirectional"))
      (node (ref "P-CH3+4") (pin "1") (pinfunction "1_1") (pintype "passive"))
      (node (ref "P-CH3+4") (pin "7") (pinfunction "1_7") (pintype "passive"))
    )
    (net (code "46") (name "CH4_PA+") (class "Default")
      (node (ref "P-CH3+4") (pin "11") (pinfunction "1_11") (pintype "passive"))
      (node (ref "SSR_3J/4A") (pin "6") (pinfunction "O2_6") (pintype "bidirectional"))
    )
    (net (code "47") (name "CH4_PB+") (class "Default")
      (node (ref "P-CH3+4") (pin "10") (pinfunction "1_10") (pintype "passive"))
      (node (ref "SSR_4BC") (pin "8") (pinfunction "O2_8") (pintype "bidirectional"))
    )
    (net (code "48") (name "CH4_PC+") (class "Default")
      (node (ref "P-CH3+4") (pin "9") (pinfunction "1_9") (pintype "passive"))
      (node (ref "SSR_4BC") (pin "6") (pinfunction "O2_6") (pintype "bidirectional"))
    )
    (net (code "49") (name "CH4_PD+") (class "Default")
      (node (ref "P-CH3+4") (pin "8") (pinfunction "1_8") (pintype "passive"))
      (node (ref "SSR_4DE") (pin "8") (pinfunction "O2_8") (pintype "bidirectional"))
    )
    (net (code "50") (name "CH4_PE+") (class "Default")
      (node (ref "P-CH3+4") (pin "6") (pinfunction "1_6") (pintype "passive"))
      (node (ref "SSR_4DE") (pin "6") (pinfunction "O2_6") (pintype "bidirectional"))
    )
    (net (code "51") (name "CH4_PF+") (class "Default")
      (node (ref "P-CH3+4") (pin "5") (pinfunction "1_5") (pintype "passive"))
      (node (ref "SSR_4FG") (pin "8") (pinfunction "O2_8") (pintype "bidirectional"))
    )
    (net (code "52") (name "CH4_PG+") (class "Default")
      (node (ref "P-CH3+4") (pin "4") (pinfunction "1_4") (pintype "passive"))
      (node (ref "SSR_4FG") (pin "6") (pinfunction "O2_6") (pintype "bidirectional"))
    )
    (net (code "53") (name "CH4_PH+") (class "Default")
      (node (ref "P-CH3+4") (pin "3") (pinfunction "1_3") (pintype "passive"))
      (node (ref "SSR_4HJ") (pin "8") (pinfunction "O2_8") (pintype "bidirectional"))
    )
    (net (code "54") (name "CH4_PJ+") (class "Default")
      (node (ref "P-CH3+4") (pin "2") (pinfunction "1_2") (pintype "passive"))
      (node (ref "SSR_4HJ") (pin "6") (pinfunction "O2_6") (pintype "bidirectional"))
    )
    (net (code "55") (name "CH5_I+") (class "Default")
      (node (ref "AUDIO_IN") (pin "18") (pinfunction "18_18") (pintype "passive"))
      (node (ref "DRV5") (pin "17") (pinfunction "IN+_17") (pintype "bidirectional"))
    )
    (net (code "56") (name "CH5_I-") (class "Default")
      (node (ref "AUDIO_IN") (pin "6") (pinfunction "6_6") (pintype "passive"))
      (node (ref "DRV5") (pin "16") (pinfunction "IN-_16") (pintype "bidirectional"))
    )
    (net (code "57") (name "CH5_O+") (class "Default")
      (node (ref "DRV5") (pin "13") (pinfunction "OUT+_13") (pintype "bidirectional"))
      (node (ref "SSR_5AB") (pin "5") (pinfunction "O1_5") (pintype "bidirectional"))
      (node (ref "SSR_5AB") (pin "7") (pinfunction "O1_7") (pintype "bidirectional"))
      (node (ref "SSR_5CD") (pin "5") (pinfunction "O1_5") (pintype "bidirectional"))
      (node (ref "SSR_5CD") (pin "7") (pinfunction "O1_7") (pintype "bidirectional"))
      (node (ref "SSR_5EF") (pin "5") (pinfunction "O1_5") (pintype "bidirectional"))
      (node (ref "SSR_5EF") (pin "7") (pinfunction "O1_7") (pintype "bidirectional"))
      (node (ref "SSR_5GH") (pin "5") (pinfunction "O1_5") (pintype "bidirectional"))
      (node (ref "SSR_5GH") (pin "7") (pinfunction "O1_7") (pintype "bidirectional"))
      (node (ref "SSR_5J/6A") (pin "7") (pinfunction "O1_7") (pintype "bidirectional"))
    )
    (net (code "58") (name "CH5_O-") (class "Default")
      (node (ref "DRV5") (pin "14") (pinfunction "OUT-_14") (pintype "bidirectional"))
      (node (ref "P-CH5+6") (pin "12") (pinfunction "1_12") (pintype "passive"))
      (node (ref "P-CH5+6") (pin "18") (pinfunction "1_18") (pintype "passive"))
    )
    (net (code "59") (name "CH5_PA+") (class "Default")
      (node (ref "P-CH5+6") (pin "22") (pinfunction "1_22") (pintype "passive"))
      (node (ref "SSR_5AB") (pin "8") (pinfunction "O2_8") (pintype "bidirectional"))
    )
    (net (code "60") (name "CH5_PB+") (class "Default")
      (node (ref "P-CH5+6") (pin "21") (pinfunction "1_21") (pintype "passive"))
      (node (ref "SSR_5AB") (pin "6") (pinfunction "O2_6") (pintype "bidirectional"))
    )
    (net (code "61") (name "CH5_PC+") (class "Default")
      (node (ref "P-CH5+6") (pin "20") (pinfunction "1_20") (pintype "passive"))
      (node (ref "SSR_5CD") (pin "8") (pinfunction "O2_8") (pintype "bidirectional"))
    )
    (net (code "62") (name "CH5_PD+") (class "Default")
      (node (ref "P-CH5+6") (pin "19") (pinfunction "1_19") (pintype "passive"))
      (node (ref "SSR_5CD") (pin "6") (pinfunction "O2_6") (pintype "bidirectional"))
    )
    (net (code "63") (name "CH5_PE+") (class "Default")
      (node (ref "P-CH5+6") (pin "17") (pinfunction "1_17") (pintype "passive"))
      (node (ref "SSR_5EF") (pin "8") (pinfunction "O2_8") (pintype "bidirectional"))
    )
    (net (code "64") (name "CH5_PF+") (class "Default")
      (node (ref "P-CH5+6") (pin "16") (pinfunction "1_16") (pintype "passive"))
      (node (ref "SSR_5EF") (pin "6") (pinfunction "O2_6") (pintype "bidirectional"))
    )
    (net (code "65") (name "CH5_PG+") (class "Default")
      (node (ref "P-CH5+6") (pin "15") (pinfunction "1_15") (pintype "passive"))
      (node (ref "SSR_5GH") (pin "8") (pinfunction "O2_8") (pintype "bidirectional"))
    )
    (net (code "66") (name "CH5_PH+") (class "Default")
      (node (ref "P-CH5+6") (pin "14") (pinfunction "1_14") (pintype "passive"))
      (node (ref "SSR_5GH") (pin "6") (pinfunction "O2_6") (pintype "bidirectional"))
    )
    (net (code "67") (name "CH5_PJ+") (class "Default")
      (node (ref "P-CH5+6") (pin "13") (pinfunction "1_13") (pintype "passive"))
      (node (ref "SSR_5J/6A") (pin "8") (pinfunction "O2_8") (pintype "bidirectional"))
    )
    (net (code "68") (name "CH6_I+") (class "Default")
      (node (ref "AUDIO_IN") (pin "4") (pinfunction "4_4") (pintype "passive"))
      (node (ref "DRV6") (pin "17") (pinfunction "IN+_17") (pintype "bidirectional"))
    )
    (net (code "69") (name "CH6_I-") (class "Default")
      (node (ref "AUDIO_IN") (pin "17") (pinfunction "17_17") (pintype "passive"))
      (node (ref "DRV6") (pin "16") (pinfunction "IN-_16") (pintype "bidirectional"))
    )
    (net (code "70") (name "CH6_O+") (class "Default")
      (node (ref "DRV6") (pin "13") (pinfunction "OUT+_13") (pintype "bidirectional"))
      (node (ref "SSR_5J/6A") (pin "5") (pinfunction "O1_5") (pintype "bidirectional"))
      (node (ref "SSR_6BC") (pin "5") (pinfunction "O1_5") (pintype "bidirectional"))
      (node (ref "SSR_6BC") (pin "7") (pinfunction "O1_7") (pintype "bidirectional"))
      (node (ref "SSR_6DE") (pin "5") (pinfunction "O1_5") (pintype "bidirectional"))
      (node (ref "SSR_6DE") (pin "7") (pinfunction "O1_7") (pintype "bidirectional"))
      (node (ref "SSR_6FG") (pin "5") (pinfunction "O1_5") (pintype "bidirectional"))
      (node (ref "SSR_6FG") (pin "7") (pinfunction "O1_7") (pintype "bidirectional"))
      (node (ref "SSR_6HJ") (pin "5") (pinfunction "O1_5") (pintype "bidirectional"))
      (node (ref "SSR_6HJ") (pin "7") (pinfunction "O1_7") (pintype "bidirectional"))
    )
    (net (code "71") (name "CH6_O-") (class "Default")
      (node (ref "DRV6") (pin "14") (pinfunction "OUT-_14") (pintype "bidirectional"))
      (node (ref "P-CH5+6") (pin "1") (pinfunction "1_1") (pintype "passive"))
      (node (ref "P-CH5+6") (pin "7") (pinfunction "1_7") (pintype "passive"))
    )
    (net (code "72") (name "CH6_PA+") (class "Default")
      (node (ref "P-CH5+6") (pin "11") (pinfunction "1_11") (pintype "passive"))
      (node (ref "SSR_5J/6A") (pin "6") (pinfunction "O2_6") (pintype "bidirectional"))
    )
    (net (code "73") (name "CH6_PB+") (class "Default")
      (node (ref "P-CH5+6") (pin "10") (pinfunction "1_10") (pintype "passive"))
      (node (ref "SSR_6BC") (pin "8") (pinfunction "O2_8") (pintype "bidirectional"))
    )
    (net (code "74") (name "CH6_PC+") (class "Default")
      (node (ref "P-CH5+6") (pin "9") (pinfunction "1_9") (pintype "passive"))
      (node (ref "SSR_6BC") (pin "6") (pinfunction "O2_6") (pintype "bidirectional"))
    )
    (net (code "75") (name "CH6_PD+") (class "Default")
      (node (ref "P-CH5+6") (pin "8") (pinfunction "1_8") (pintype "passive"))
      (node (ref "SSR_6DE") (pin "8") (pinfunction "O2_8") (pintype "bidirectional"))
    )
    (net (code "76") (name "CH6_PE+") (class "Default")
      (node (ref "P-CH5+6") (pin "6") (pinfunction "1_6") (pintype "passive"))
      (node (ref "SSR_6DE") (pin "6") (pinfunction "O2_6") (pintype "bidirectional"))
    )
    (net (code "77") (name "CH6_PF+") (class "Default")
      (node (ref "P-CH5+6") (pin "5") (pinfunction "1_5") (pintype "passive"))
      (node (ref "SSR_6FG") (pin "8") (pinfunction "O2_8") (pintype "bidirectional"))
    )
    (net (code "78") (name "CH6_PG+") (class "Default")
      (node (ref "P-CH5+6") (pin "4") (pinfunction "1_4") (pintype "passive"))
      (node (ref "SSR_6FG") (pin "6") (pinfunction "O2_6") (pintype "bidirectional"))
    )
    (net (code "79") (name "CH6_PH+") (class "Default")
      (node (ref "P-CH5+6") (pin "3") (pinfunction "1_3") (pintype "passive"))
      (node (ref "SSR_6HJ") (pin "8") (pinfunction "O2_8") (pintype "bidirectional"))
    )
    (net (code "80") (name "CH6_PJ+") (class "Default")
      (node (ref "P-CH5+6") (pin "2") (pinfunction "1_2") (pintype "passive"))
      (node (ref "SSR_6HJ") (pin "6") (pinfunction "O2_6") (pintype "bidirectional"))
    )
    (net (code "81") (name "CH7_I+") (class "Default")
      (node (ref "AUDIO_IN") (pin "15") (pinfunction "15_15") (pintype "passive"))
      (node (ref "DRV7") (pin "17") (pinfunction "IN+_17") (pintype "bidirectional"))
    )
    (net (code "82") (name "CH7_I-") (class "Default")
      (node (ref "AUDIO_IN") (pin "3") (pinfunction "3_3") (pintype "passive"))
      (node (ref "DRV7") (pin "16") (pinfunction "IN-_16") (pintype "bidirectional"))
    )
    (net (code "83") (name "CH7_O+") (class "Default")
      (node (ref "DRV7") (pin "13") (pinfunction "OUT+_13") (pintype "bidirectional"))
      (node (ref "SSR_7AB") (pin "5") (pinfunction "O1_5") (pintype "bidirectional"))
      (node (ref "SSR_7AB") (pin "7") (pinfunction "O1_7") (pintype "bidirectional"))
      (node (ref "SSR_7CD") (pin "5") (pinfunction "O1_5") (pintype "bidirectional"))
      (node (ref "SSR_7CD") (pin "7") (pinfunction "O1_7") (pintype "bidirectional"))
      (node (ref "SSR_7EF") (pin "5") (pinfunction "O1_5") (pintype "bidirectional"))
      (node (ref "SSR_7EF") (pin "7") (pinfunction "O1_7") (pintype "bidirectional"))
      (node (ref "SSR_7GH") (pin "5") (pinfunction "O1_5") (pintype "bidirectional"))
      (node (ref "SSR_7GH") (pin "7") (pinfunction "O1_7") (pintype "bidirectional"))
      (node (ref "SSR_7J/8A") (pin "7") (pinfunction "O1_7") (pintype "bidirectional"))
    )
    (net (code "84") (name "CH7_O-") (class "Default")
      (node (ref "DRV7") (pin "14") (pinfunction "OUT-_14") (pintype "bidirectional"))
      (node (ref "P-CH7+8") (pin "12") (pinfunction "1_12") (pintype "passive"))
      (node (ref "P-CH7+8") (pin "18") (pinfunction "1_18") (pintype "passive"))
    )
    (net (code "85") (name "CH7_PA+") (class "Default")
      (node (ref "P-CH7+8") (pin "22") (pinfunction "1_22") (pintype "passive"))
      (node (ref "SSR_7AB") (pin "8") (pinfunction "O2_8") (pintype "bidirectional"))
    )
    (net (code "86") (name "CH7_PB+") (class "Default")
      (node (ref "P-CH7+8") (pin "21") (pinfunction "1_21") (pintype "passive"))
      (node (ref "SSR_7AB") (pin "6") (pinfunction "O2_6") (pintype "bidirectional"))
    )
    (net (code "87") (name "CH7_PC+") (class "Default")
      (node (ref "P-CH7+8") (pin "20") (pinfunction "1_20") (pintype "passive"))
      (node (ref "SSR_7CD") (pin "8") (pinfunction "O2_8") (pintype "bidirectional"))
    )
    (net (code "88") (name "CH7_PD+") (class "Default")
      (node (ref "P-CH7+8") (pin "19") (pinfunction "1_19") (pintype "passive"))
      (node (ref "SSR_7CD") (pin "6") (pinfunction "O2_6") (pintype "bidirectional"))
    )
    (net (code "89") (name "CH7_PE+") (class "Default")
      (node (ref "P-CH7+8") (pin "17") (pinfunction "1_17") (pintype "passive"))
      (node (ref "SSR_7EF") (pin "8") (pinfunction "O2_8") (pintype "bidirectional"))
    )
    (net (code "90") (name "CH7_PF+") (class "Default")
      (node (ref "P-CH7+8") (pin "16") (pinfunction "1_16") (pintype "passive"))
      (node (ref "SSR_7EF") (pin "6") (pinfunction "O2_6") (pintype "bidirectional"))
    )
    (net (code "91") (name "CH7_PG+") (class "Default")
      (node (ref "P-CH7+8") (pin "15") (pinfunction "1_15") (pintype "passive"))
      (node (ref "SSR_7GH") (pin "8") (pinfunction "O2_8") (pintype "bidirectional"))
    )
    (net (code "92") (name "CH7_PH+") (class "Default")
      (node (ref "P-CH7+8") (pin "14") (pinfunction "1_14") (pintype "passive"))
      (node (ref "SSR_7GH") (pin "6") (pinfunction "O2_6") (pintype "bidirectional"))
    )
    (net (code "93") (name "CH7_PJ+") (class "Default")
      (node (ref "P-CH7+8") (pin "13") (pinfunction "1_13") (pintype "passive"))
      (node (ref "SSR_7J/8A") (pin "8") (pinfunction "O2_8") (pintype "bidirectional"))
    )
    (net (code "94") (name "CH8_I+") (class "Default")
      (node (ref "AUDIO_IN") (pin "1") (pinfunction "1_1") (pintype "passive"))
      (node (ref "DRV8") (pin "17") (pinfunction "IN+_17") (pintype "bidirectional"))
    )
    (net (code "95") (name "CH8_I-") (class "Default")
      (node (ref "AUDIO_IN") (pin "14") (pinfunction "14_14") (pintype "passive"))
      (node (ref "DRV8") (pin "16") (pinfunction "IN-_16") (pintype "bidirectional"))
    )
    (net (code "96") (name "CH8_O+") (class "Default")
      (node (ref "DRV8") (pin "13") (pinfunction "OUT+_13") (pintype "bidirectional"))
      (node (ref "SSR_7J/8A") (pin "5") (pinfunction "O1_5") (pintype "bidirectional"))
      (node (ref "SSR_8BC") (pin "5") (pinfunction "O1_5") (pintype "bidirectional"))
      (node (ref "SSR_8BC") (pin "7") (pinfunction "O1_7") (pintype "bidirectional"))
      (node (ref "SSR_8DE") (pin "5") (pinfunction "O1_5") (pintype "bidirectional"))
      (node (ref "SSR_8DE") (pin "7") (pinfunction "O1_7") (pintype "bidirectional"))
      (node (ref "SSR_8FG") (pin "5") (pinfunction "O1_5") (pintype "bidirectional"))
      (node (ref "SSR_8FG") (pin "7") (pinfunction "O1_7") (pintype "bidirectional"))
      (node (ref "SSR_8HJ") (pin "5") (pinfunction "O1_5") (pintype "bidirectional"))
      (node (ref "SSR_8HJ") (pin "7") (pinfunction "O1_7") (pintype "bidirectional"))
    )
    (net (code "97") (name "CH8_O-") (class "Default")
      (node (ref "DRV8") (pin "14") (pinfunction "OUT-_14") (pintype "bidirectional"))
      (node (ref "P-CH7+8") (pin "1") (pinfunction "1_1") (pintype "passive"))
      (node (ref "P-CH7+8") (pin "7") (pinfunction "1_7") (pintype "passive"))
    )
    (net (code "98") (name "CH8_PA+") (class "Default")
      (node (ref "P-CH7+8") (pin "11") (pinfunction "1_11") (pintype "passive"))
      (node (ref "SSR_7J/8A") (pin "6") (pinfunction "O2_6") (pintype "bidirectional"))
    )
    (net (code "99") (name "CH8_PB+") (class "Default")
      (node (ref "P-CH7+8") (pin "10") (pinfunction "1_10") (pintype "passive"))
      (node (ref "SSR_8BC") (pin "8") (pinfunction "O2_8") (pintype "bidirectional"))
    )
    (net (code "100") (name "CH8_PC+") (class "Default")
      (node (ref "P-CH7+8") (pin "9") (pinfunction "1_9") (pintype "passive"))
      (node (ref "SSR_8BC") (pin "6") (pinfunction "O2_6") (pintype "bidirectional"))
    )
    (net (code "101") (name "CH8_PD+") (class "Default")
      (node (ref "P-CH7+8") (pin "8") (pinfunction "1_8") (pintype "passive"))
      (node (ref "SSR_8DE") (pin "8") (pinfunction "O2_8") (pintype "bidirectional"))
    )
    (net (code "102") (name "CH8_PE+") (class "Default")
      (node (ref "P-CH7+8") (pin "6") (pinfunction "1_6") (pintype "passive"))
      (node (ref "SSR_8DE") (pin "6") (pinfunction "O2_6") (pintype "bidirectional"))
    )
    (net (code "103") (name "CH8_PF+") (class "Default")
      (node (ref "P-CH7+8") (pin "5") (pinfunction "1_5") (pintype "passive"))
      (node (ref "SSR_8FG") (pin "8") (pinfunction "O2_8") (pintype "bidirectional"))
    )
    (net (code "104") (name "CH8_PG+") (class "Default")
      (node (ref "P-CH7+8") (pin "4") (pinfunction "1_4") (pintype "passive"))
      (node (ref "SSR_8FG") (pin "6") (pinfunction "O2_6") (pintype "bidirectional"))
    )
    (net (code "105") (name "CH8_PH+") (class "Default")
      (node (ref "P-CH7+8") (pin "3") (pinfunction "1_3") (pintype "passive"))
      (node (ref "SSR_8HJ") (pin "8") (pinfunction "O2_8") (pintype "bidirectional"))
    )
    (net (code "106") (name "CH8_PJ+") (class "Default")
      (node (ref "P-CH7+8") (pin "2") (pinfunction "1_2") (pintype "passive"))
      (node (ref "SSR_8HJ") (pin "6") (pinfunction "O2_6") (pintype "bidirectional"))
    )
    (net (code "107") (name "GND") (class "Default")
      (node (ref "AUDIO_IN") (pin "11") (pinfunction "11_11") (pintype "passive"))
      (node (ref "AUDIO_IN") (pin "16") (pinfunction "16_16") (pintype "passive"))
      (node (ref "AUDIO_IN") (pin "19") (pinfunction "19_19") (pintype "passive"))
      (node (ref "AUDIO_IN") (pin "2") (pinfunction "2_2") (pintype "passive"))
      (node (ref "AUDIO_IN") (pin "22") (pinfunction "22_22") (pintype "passive"))
      (node (ref "AUDIO_IN") (pin "25") (pinfunction "25_25") (pintype "passive"))
      (node (ref "AUDIO_IN") (pin "5") (pinfunction "5_5") (pintype "passive"))
      (node (ref "AUDIO_IN") (pin "8") (pinfunction "8_8") (pintype "passive"))
      (node (ref "GND_LIFT") (pin "1") (pinfunction "T1A_1") (pintype "bidirectional"))
      (node (ref "GND_LIFT") (pin "6") (pinfunction "T2A_6") (pintype "bidirectional"))
    )
    (net (code "108") (name "LED1") (class "Default")
      (node (ref "ARDUINO_D") (pin "10") (pinfunction "10_10") (pintype "passive"))
      (node (ref "RLED1") (pin "1") (pinfunction "1_1") (pintype "passive"))
    )
    (net (code "109") (name "LED2") (class "Default")
      (node (ref "ARDUINO_D") (pin "8") (pinfunction "8_8") (pintype "passive"))
      (node (ref "RLED2") (pin "1") (pinfunction "1_1") (pintype "passive"))
    )
    (net (code "110") (name "LED3") (class "Default")
      (node (ref "ARDUINO_D") (pin "7") (pinfunction "7_7") (pintype "passive"))
      (node (ref "RLED3") (pin "1") (pinfunction "1_1") (pintype "passive"))
    )
    (net (code "111") (name "Net-(DRV1-FB)") (class "Default")
      (node (ref "DRV1") (pin "3") (pinfunction "FB_3") (pintype "bidirectional"))
      (node (ref "RVBST1-1") (pin "1") (pinfunction "1_1") (pintype "passive"))
      (node (ref "RVBST1-2") (pin "2") (pinfunction "2_2") (pintype "passive"))
    )
    (net (code "112") (name "Net-(DRV1-PVDD)") (class "Default")
      (node (ref "CVBST1") (pin "1") (pinfunction "1_1") (pintype "passive"))
      (node (ref "DRV1") (pin "10") (pinfunction "VBST_10") (pintype "bidirectional"))
      (node (ref "DRV1") (pin "11") (pinfunction "VBST_11") (pintype "bidirectional"))
      (node (ref "DRV1") (pin "12") (pinfunction "PVDD_12") (pintype "bidirectional"))
      (node (ref "RVBST1-1") (pin "2") (pinfunction "2_2") (pintype "passive"))
    )
    (net (code "113") (name "Net-(DRV1-REXT)") (class "Default")
      (node (ref "DRV1") (pin "15") (pinfunction "REXT_15") (pintype "bidirectional"))
      (node (ref "REXT1") (pin "2") (pinfunction "2_2") (pintype "passive"))
    )
    (net (code "114") (name "Net-(DRV1-SW-Pad7)") (class "Default")
      (node (ref "DRV1") (pin "7") (pinfunction "SW_7") (pintype "bidirectional"))
      (node (ref "DRV1") (pin "8") (pinfunction "SW_8") (pintype "bidirectional"))
      (node (ref "L1") (pin "1") (pinfunction "1_1") (pintype "passive"))
    )
    (net (code "115") (name "Net-(DRV1-VPUMP)") (class "Default")
      (node (ref "CPUMP1") (pin "1") (pinfunction "1_1") (pintype "passive"))
      (node (ref "DRV1") (pin "1") (pinfunction "VPUMP_1") (pintype "bidirectional"))
    )
    (net (code "116") (name "Net-(DRV1-VREG)") (class "Default")
      (node (ref "CVREG1") (pin "1") (pinfunction "1_1") (pintype "passive"))
      (node (ref "DRV1") (pin "20") (pinfunction "VREG_20") (pintype "bidirectional"))
    )
    (net (code "117") (name "Net-(DRV2-FB)") (class "Default")
      (node (ref "DRV2") (pin "3") (pinfunction "FB_3") (pintype "bidirectional"))
      (node (ref "RVBST2-1") (pin "1") (pinfunction "1_1") (pintype "passive"))
      (node (ref "RVBST2-2") (pin "2") (pinfunction "2_2") (pintype "passive"))
    )
    (net (code "118") (name "Net-(DRV2-PVDD)") (class "Default")
      (node (ref "CVBST2") (pin "1") (pinfunction "1_1") (pintype "passive"))
      (node (ref "DRV2") (pin "10") (pinfunction "VBST_10") (pintype "bidirectional"))
      (node (ref "DRV2") (pin "11") (pinfunction "VBST_11") (pintype "bidirectional"))
      (node (ref "DRV2") (pin "12") (pinfunction "PVDD_12") (pintype "bidirectional"))
      (node (ref "RVBST2-1") (pin "2") (pinfunction "2_2") (pintype "passive"))
    )
    (net (code "119") (name "Net-(DRV2-REXT)") (class "Default")
      (node (ref "DRV2") (pin "15") (pinfunction "REXT_15") (pintype "bidirectional"))
      (node (ref "REXT2") (pin "2") (pinfunction "2_2") (pintype "passive"))
    )
    (net (code "120") (name "Net-(DRV2-SW-Pad7)") (class "Default")
      (node (ref "DRV2") (pin "7") (pinfunction "SW_7") (pintype "bidirectional"))
      (node (ref "DRV2") (pin "8") (pinfunction "SW_8") (pintype "bidirectional"))
      (node (ref "L2") (pin "1") (pinfunction "1_1") (pintype "passive"))
    )
    (net (code "121") (name "Net-(DRV2-VPUMP)") (class "Default")
      (node (ref "CPUMP2") (pin "1") (pinfunction "1_1") (pintype "passive"))
      (node (ref "DRV2") (pin "1") (pinfunction "VPUMP_1") (pintype "bidirectional"))
    )
    (net (code "122") (name "Net-(DRV2-VREG)") (class "Default")
      (node (ref "CVREG2") (pin "1") (pinfunction "1_1") (pintype "passive"))
      (node (ref "DRV2") (pin "20") (pinfunction "VREG_20") (pintype "bidirectional"))
    )
    (net (code "123") (name "Net-(DRV3-FB)") (class "Default")
      (node (ref "DRV3") (pin "3") (pinfunction "FB_3") (pintype "bidirectional"))
      (node (ref "RVBST3-1") (pin "1") (pinfunction "1_1") (pintype "passive"))
      (node (ref "RVBST3-2") (pin "2") (pinfunction "2_2") (pintype "passive"))
    )
    (net (code "124") (name "Net-(DRV3-PVDD)") (class "Default")
      (node (ref "CVBST3") (pin "1") (pinfunction "1_1") (pintype "passive"))
      (node (ref "DRV3") (pin "10") (pinfunction "VBST_10") (pintype "bidirectional"))
      (node (ref "DRV3") (pin "11") (pinfunction "VBST_11") (pintype "bidirectional"))
      (node (ref "DRV3") (pin "12") (pinfunction "PVDD_12") (pintype "bidirectional"))
      (node (ref "RVBST3-1") (pin "2") (pinfunction "2_2") (pintype "passive"))
    )
    (net (code "125") (name "Net-(DRV3-REXT)") (class "Default")
      (node (ref "DRV3") (pin "15") (pinfunction "REXT_15") (pintype "bidirectional"))
      (node (ref "REXT3") (pin "2") (pinfunction "2_2") (pintype "passive"))
    )
    (net (code "126") (name "Net-(DRV3-SW-Pad7)") (class "Default")
      (node (ref "DRV3") (pin "7") (pinfunction "SW_7") (pintype "bidirectional"))
      (node (ref "DRV3") (pin "8") (pinfunction "SW_8") (pintype "bidirectional"))
      (node (ref "L3") (pin "1") (pinfunction "1_1") (pintype "passive"))
    )
    (net (code "127") (name "Net-(DRV3-VPUMP)") (class "Default")
      (node (ref "CPUMP3") (pin "1") (pinfunction "1_1") (pintype "passive"))
      (node (ref "DRV3") (pin "1") (pinfunction "VPUMP_1") (pintype "bidirectional"))
    )
    (net (code "128") (name "Net-(DRV3-VREG)") (class "Default")
      (node (ref "CVREG3") (pin "1") (pinfunction "1_1") (pintype "passive"))
      (node (ref "DRV3") (pin "20") (pinfunction "VREG_20") (pintype "bidirectional"))
    )
    (net (code "129") (name "Net-(DRV4-FB)") (class "Default")
      (node (ref "DRV4") (pin "3") (pinfunction "FB_3") (pintype "bidirectional"))
      (node (ref "RVBST4-1") (pin "1") (pinfunction "1_1") (pintype "passive"))
      (node (ref "RVBST4-2") (pin "2") (pinfunction "2_2") (pintype "passive"))
    )
    (net (code "130") (name "Net-(DRV4-PVDD)") (class "Default")
      (node (ref "CVBST4") (pin "1") (pinfunction "1_1") (pintype "passive"))
      (node (ref "DRV4") (pin "10") (pinfunction "VBST_10") (pintype "bidirectional"))
      (node (ref "DRV4") (pin "11") (pinfunction "VBST_11") (pintype "bidirectional"))
      (node (ref "DRV4") (pin "12") (pinfunction "PVDD_12") (pintype "bidirectional"))
      (node (ref "RVBST4-1") (pin "2") (pinfunction "2_2") (pintype "passive"))
    )
    (net (code "131") (name "Net-(DRV4-REXT)") (class "Default")
      (node (ref "DRV4") (pin "15") (pinfunction "REXT_15") (pintype "bidirectional"))
      (node (ref "REXT4") (pin "2") (pinfunction "2_2") (pintype "passive"))
    )
    (net (code "132") (name "Net-(DRV4-SW-Pad7)") (class "Default")
      (node (ref "DRV4") (pin "7") (pinfunction "SW_7") (pintype "bidirectional"))
      (node (ref "DRV4") (pin "8") (pinfunction "SW_8") (pintype "bidirectional"))
      (node (ref "L4") (pin "1") (pinfunction "1_1") (pintype "passive"))
    )
    (net (code "133") (name "Net-(DRV4-VPUMP)") (class "Default")
      (node (ref "CPUMP4") (pin "1") (pinfunction "1_1") (pintype "passive"))
      (node (ref "DRV4") (pin "1") (pinfunction "VPUMP_1") (pintype "bidirectional"))
    )
    (net (code "134") (name "Net-(DRV4-VREG)") (class "Default")
      (node (ref "CVREG4") (pin "1") (pinfunction "1_1") (pintype "passive"))
      (node (ref "DRV4") (pin "20") (pinfunction "VREG_20") (pintype "bidirectional"))
    )
    (net (code "135") (name "Net-(DRV5-FB)") (class "Default")
      (node (ref "DRV5") (pin "3") (pinfunction "FB_3") (pintype "bidirectional"))
      (node (ref "RVBST5-1") (pin "1") (pinfunction "1_1") (pintype "passive"))
      (node (ref "RVBST5-2") (pin "2") (pinfunction "2_2") (pintype "passive"))
    )
    (net (code "136") (name "Net-(DRV5-PVDD)") (class "Default")
      (node (ref "CVBST5") (pin "1") (pinfunction "1_1") (pintype "passive"))
      (node (ref "DRV5") (pin "10") (pinfunction "VBST_10") (pintype "bidirectional"))
      (node (ref "DRV5") (pin "11") (pinfunction "VBST_11") (pintype "bidirectional"))
      (node (ref "DRV5") (pin "12") (pinfunction "PVDD_12") (pintype "bidirectional"))
      (node (ref "RVBST5-1") (pin "2") (pinfunction "2_2") (pintype "passive"))
    )
    (net (code "137") (name "Net-(DRV5-REXT)") (class "Default")
      (node (ref "DRV5") (pin "15") (pinfunction "REXT_15") (pintype "bidirectional"))
      (node (ref "REXT5") (pin "2") (pinfunction "2_2") (pintype "passive"))
    )
    (net (code "138") (name "Net-(DRV5-SW-Pad7)") (class "Default")
      (node (ref "DRV5") (pin "7") (pinfunction "SW_7") (pintype "bidirectional"))
      (node (ref "DRV5") (pin "8") (pinfunction "SW_8") (pintype "bidirectional"))
      (node (ref "L5") (pin "1") (pinfunction "1_1") (pintype "passive"))
    )
    (net (code "139") (name "Net-(DRV5-VPUMP)") (class "Default")
      (node (ref "CPUMP5") (pin "1") (pinfunction "1_1") (pintype "passive"))
      (node (ref "DRV5") (pin "1") (pinfunction "VPUMP_1") (pintype "bidirectional"))
    )
    (net (code "140") (name "Net-(DRV5-VREG)") (class "Default")
      (node (ref "CVREG5") (pin "1") (pinfunction "1_1") (pintype "passive"))
      (node (ref "DRV5") (pin "20") (pinfunction "VREG_20") (pintype "bidirectional"))
    )
    (net (code "141") (name "Net-(DRV6-FB)") (class "Default")
      (node (ref "DRV6") (pin "3") (pinfunction "FB_3") (pintype "bidirectional"))
      (node (ref "RVBST6-1") (pin "1") (pinfunction "1_1") (pintype "passive"))
      (node (ref "RVBST6-2") (pin "2") (pinfunction "2_2") (pintype "passive"))
    )
    (net (code "142") (name "Net-(DRV6-PVDD)") (class "Default")
      (node (ref "CVBST6") (pin "1") (pinfunction "1_1") (pintype "passive"))
      (node (ref "DRV6") (pin "10") (pinfunction "VBST_10") (pintype "bidirectional"))
      (node (ref "DRV6") (pin "11") (pinfunction "VBST_11") (pintype "bidirectional"))
      (node (ref "DRV6") (pin "12") (pinfunction "PVDD_12") (pintype "bidirectional"))
      (node (ref "RVBST6-1") (pin "2") (pinfunction "2_2") (pintype "passive"))
    )
    (net (code "143") (name "Net-(DRV6-REXT)") (class "Default")
      (node (ref "DRV6") (pin "15") (pinfunction "REXT_15") (pintype "bidirectional"))
      (node (ref "REXT6") (pin "2") (pinfunction "2_2") (pintype "passive"))
    )
    (net (code "144") (name "Net-(DRV6-SW-Pad7)") (class "Default")
      (node (ref "DRV6") (pin "7") (pinfunction "SW_7") (pintype "bidirectional"))
      (node (ref "DRV6") (pin "8") (pinfunction "SW_8") (pintype "bidirectional"))
      (node (ref "L6") (pin "1") (pinfunction "1_1") (pintype "passive"))
    )
    (net (code "145") (name "Net-(DRV6-VPUMP)") (class "Default")
      (node (ref "CPUMP6") (pin "1") (pinfunction "1_1") (pintype "passive"))
      (node (ref "DRV6") (pin "1") (pinfunction "VPUMP_1") (pintype "bidirectional"))
    )
    (net (code "146") (name "Net-(DRV6-VREG)") (class "Default")
      (node (ref "CVREG6") (pin "1") (pinfunction "1_1") (pintype "passive"))
      (node (ref "DRV6") (pin "20") (pinfunction "VREG_20") (pintype "bidirectional"))
    )
    (net (code "147") (name "Net-(DRV7-FB)") (class "Default")
      (node (ref "DRV7") (pin "3") (pinfunction "FB_3") (pintype "bidirectional"))
      (node (ref "RVBST7-1") (pin "1") (pinfunction "1_1") (pintype "passive"))
      (node (ref "RVBST7-2") (pin "2") (pinfunction "2_2") (pintype "passive"))
    )
    (net (code "148") (name "Net-(DRV7-PVDD)") (class "Default")
      (node (ref "CVBST7") (pin "1") (pinfunction "1_1") (pintype "passive"))
      (node (ref "DRV7") (pin "10") (pinfunction "VBST_10") (pintype "bidirectional"))
      (node (ref "DRV7") (pin "11") (pinfunction "VBST_11") (pintype "bidirectional"))
      (node (ref "DRV7") (pin "12") (pinfunction "PVDD_12") (pintype "bidirectional"))
      (node (ref "RVBST7-1") (pin "2") (pinfunction "2_2") (pintype "passive"))
    )
    (net (code "149") (name "Net-(DRV7-REXT)") (class "Default")
      (node (ref "DRV7") (pin "15") (pinfunction "REXT_15") (pintype "bidirectional"))
      (node (ref "REXT7") (pin "2") (pinfunction "2_2") (pintype "passive"))
    )
    (net (code "150") (name "Net-(DRV7-SW-Pad7)") (class "Default")
      (node (ref "DRV7") (pin "7") (pinfunction "SW_7") (pintype "bidirectional"))
      (node (ref "DRV7") (pin "8") (pinfunction "SW_8") (pintype "bidirectional"))
      (node (ref "L7") (pin "1") (pinfunction "1_1") (pintype "passive"))
    )
    (net (code "151") (name "Net-(DRV7-VPUMP)") (class "Default")
      (node (ref "CPUMP7") (pin "1") (pinfunction "1_1") (pintype "passive"))
      (node (ref "DRV7") (pin "1") (pinfunction "VPUMP_1") (pintype "bidirectional"))
    )
    (net (code "152") (name "Net-(DRV7-VREG)") (class "Default")
      (node (ref "CVREG7") (pin "1") (pinfunction "1_1") (pintype "passive"))
      (node (ref "DRV7") (pin "20") (pinfunction "VREG_20") (pintype "bidirectional"))
    )
    (net (code "153") (name "Net-(DRV8-FB)") (class "Default")
      (node (ref "DRV8") (pin "3") (pinfunction "FB_3") (pintype "bidirectional"))
      (node (ref "RVBST8-1") (pin "1") (pinfunction "1_1") (pintype "passive"))
      (node (ref "RVBST8-2") (pin "2") (pinfunction "2_2") (pintype "passive"))
    )
    (net (code "154") (name "Net-(DRV8-PVDD)") (class "Default")
      (node (ref "CVBST8") (pin "1") (pinfunction "1_1") (pintype "passive"))
      (node (ref "DRV8") (pin "10") (pinfunction "VBST_10") (pintype "bidirectional"))
      (node (ref "DRV8") (pin "11") (pinfunction "VBST_11") (pintype "bidirectional"))
      (node (ref "DRV8") (pin "12") (pinfunction "PVDD_12") (pintype "bidirectional"))
      (node (ref "RVBST8-1") (pin "2") (pinfunction "2_2") (pintype "passive"))
    )
    (net (code "155") (name "Net-(DRV8-REXT)") (class "Default")
      (node (ref "DRV8") (pin "15") (pinfunction "REXT_15") (pintype "bidirectional"))
      (node (ref "REXT8") (pin "2") (pinfunction "2_2") (pintype "passive"))
    )
    (net (code "156") (name "Net-(DRV8-SW-Pad7)") (class "Default")
      (node (ref "DRV8") (pin "7") (pinfunction "SW_7") (pintype "bidirectional"))
      (node (ref "DRV8") (pin "8") (pinfunction "SW_8") (pintype "bidirectional"))
      (node (ref "L8") (pin "1") (pinfunction "1_1") (pintype "passive"))
    )
    (net (code "157") (name "Net-(DRV8-VPUMP)") (class "Default")
      (node (ref "CPUMP8") (pin "1") (pinfunction "1_1") (pintype "passive"))
      (node (ref "DRV8") (pin "1") (pinfunction "VPUMP_1") (pintype "bidirectional"))
    )
    (net (code "158") (name "Net-(DRV8-VREG)") (class "Default")
      (node (ref "CVREG8") (pin "1") (pinfunction "1_1") (pintype "passive"))
      (node (ref "DRV8") (pin "20") (pinfunction "VREG_20") (pintype "bidirectional"))
    )
    (net (code "159") (name "Net-(GND_LIFT-P1)") (class "Default")
      (node (ref "GND_LIFT") (pin "2") (pinfunction "P1_2") (pintype "bidirectional"))
      (node (ref "GND_LIFT") (pin "5") (pinfunction "P2_5") (pintype "bidirectional"))
      (node (ref "R_LIFT1") (pin "2") (pinfunction "2_2") (pintype "passive"))
      (node (ref "R_LIFT2") (pin "1") (pinfunction "1_1") (pintype "passive"))
    )
    (net (code "160") (name "Net-(LED1-PadC)") (class "Default")
      (node (ref "LED1") (pin "C") (pinfunction "C_C") (pintype "passive"))
      (node (ref "RLED1") (pin "2") (pinfunction "2_2") (pintype "passive"))
    )
    (net (code "161") (name "Net-(LED2-PadC)") (class "Default")
      (node (ref "LED2") (pin "C") (pinfunction "C_C") (pintype "passive"))
      (node (ref "RLED2") (pin "2") (pinfunction "2_2") (pintype "passive"))
    )
    (net (code "162") (name "Net-(LED3-PadC)") (class "Default")
      (node (ref "LED3") (pin "C") (pinfunction "C_C") (pintype "passive"))
      (node (ref "RLED3") (pin "2") (pinfunction "2_2") (pintype "passive"))
    )
    (net (code "163") (name "Net-(LED_SUP-PadA)") (class "Default")
      (node (ref "LED_SUP") (pin "A") (pinfunction "A_A") (pintype "passive"))
      (node (ref "RLED_SUP") (pin "1") (pinfunction "1_1") (pintype "passive"))
    )
    (net (code "164") (name "Net-(SSR_1ABA-I+)") (class "Default")
      (node (ref "R_1A") (pin "1") (pinfunction "1_1") (pintype "passive"))
      (node (ref "SSR_1AB") (pin "1") (pinfunction "I+_1") (pintype "bidirectional"))
    )
    (net (code "165") (name "Net-(SSR_1ABB-I+)") (class "Default")
      (node (ref "R_1B") (pin "1") (pinfunction "1_1") (pintype "passive"))
      (node (ref "SSR_1AB") (pin "3") (pinfunction "I+_3") (pintype "bidirectional"))
    )
    (net (code "166") (name "Net-(SSR_1CDA-I+)") (class "Default")
      (node (ref "R_1C") (pin "1") (pinfunction "1_1") (pintype "passive"))
      (node (ref "SSR_1CD") (pin "1") (pinfunction "I+_1") (pintype "bidirectional"))
    )
    (net (code "167") (name "Net-(SSR_1CDB-I+)") (class "Default")
      (node (ref "R_1D") (pin "1") (pinfunction "1_1") (pintype "passive"))
      (node (ref "SSR_1CD") (pin "3") (pinfunction "I+_3") (pintype "bidirectional"))
    )
    (net (code "168") (name "Net-(SSR_1EFA-I+)") (class "Default")
      (node (ref "R_1E") (pin "1") (pinfunction "1_1") (pintype "passive"))
      (node (ref "SSR_1EF") (pin "1") (pinfunction "I+_1") (pintype "bidirectional"))
    )
    (net (code "169") (name "Net-(SSR_1EFB-I+)") (class "Default")
      (node (ref "R_1F") (pin "1") (pinfunction "1_1") (pintype "passive"))
      (node (ref "SSR_1EF") (pin "3") (pinfunction "I+_3") (pintype "bidirectional"))
    )
    (net (code "170") (name "Net-(SSR_1GHA-I+)") (class "Default")
      (node (ref "R_1G") (pin "1") (pinfunction "1_1") (pintype "passive"))
      (node (ref "SSR_1GH") (pin "1") (pinfunction "I+_1") (pintype "bidirectional"))
    )
    (net (code "171") (name "Net-(SSR_1GHB-I+)") (class "Default")
      (node (ref "R_1H") (pin "1") (pinfunction "1_1") (pintype "passive"))
      (node (ref "SSR_1GH") (pin "3") (pinfunction "I+_3") (pintype "bidirectional"))
    )
    (net (code "172") (name "Net-(SSR_1J/2AA-I+)") (class "Default")
      (node (ref "R_1J") (pin "1") (pinfunction "1_1") (pintype "passive"))
      (node (ref "SSR_1J/2A") (pin "1") (pinfunction "I+_1") (pintype "bidirectional"))
    )
    (net (code "173") (name "Net-(SSR_1J/2AB-I+)") (class "Default")
      (node (ref "R_2A") (pin "1") (pinfunction "1_1") (pintype "passive"))
      (node (ref "SSR_1J/2A") (pin "3") (pinfunction "I+_3") (pintype "bidirectional"))
    )
    (net (code "174") (name "Net-(SSR_2BCA-I+)") (class "Default")
      (node (ref "R_2B") (pin "1") (pinfunction "1_1") (pintype "passive"))
      (node (ref "SSR_2BC") (pin "1") (pinfunction "I+_1") (pintype "bidirectional"))
    )
    (net (code "175") (name "Net-(SSR_2BCB-I+)") (class "Default")
      (node (ref "R_2C") (pin "1") (pinfunction "1_1") (pintype "passive"))
      (node (ref "SSR_2BC") (pin "3") (pinfunction "I+_3") (pintype "bidirectional"))
    )
    (net (code "176") (name "Net-(SSR_2DEA-I+)") (class "Default")
      (node (ref "R_2D") (pin "1") (pinfunction "1_1") (pintype "passive"))
      (node (ref "SSR_2DE") (pin "1") (pinfunction "I+_1") (pintype "bidirectional"))
    )
    (net (code "177") (name "Net-(SSR_2DEB-I+)") (class "Default")
      (node (ref "R_2E") (pin "1") (pinfunction "1_1") (pintype "passive"))
      (node (ref "SSR_2DE") (pin "3") (pinfunction "I+_3") (pintype "bidirectional"))
    )
    (net (code "178") (name "Net-(SSR_2FGA-I+)") (class "Default")
      (node (ref "R_2F") (pin "1") (pinfunction "1_1") (pintype "passive"))
      (node (ref "SSR_2FG") (pin "1") (pinfunction "I+_1") (pintype "bidirectional"))
    )
    (net (code "179") (name "Net-(SSR_2FGB-I+)") (class "Default")
      (node (ref "R_2G") (pin "1") (pinfunction "1_1") (pintype "passive"))
      (node (ref "SSR_2FG") (pin "3") (pinfunction "I+_3") (pintype "bidirectional"))
    )
    (net (code "180") (name "Net-(SSR_2HJA-I+)") (class "Default")
      (node (ref "R_2H") (pin "1") (pinfunction "1_1") (pintype "passive"))
      (node (ref "SSR_2HJ") (pin "1") (pinfunction "I+_1") (pintype "bidirectional"))
    )
    (net (code "181") (name "Net-(SSR_2HJB-I+)") (class "Default")
      (node (ref "R_2J") (pin "1") (pinfunction "1_1") (pintype "passive"))
      (node (ref "SSR_2HJ") (pin "3") (pinfunction "I+_3") (pintype "bidirectional"))
    )
    (net (code "182") (name "Net-(SSR_3ABA-I+)") (class "Default")
      (node (ref "R_3A") (pin "1") (pinfunction "1_1") (pintype "passive"))
      (node (ref "SSR_3AB") (pin "1") (pinfunction "I+_1") (pintype "bidirectional"))
    )
    (net (code "183") (name "Net-(SSR_3ABB-I+)") (class "Default")
      (node (ref "R_3B") (pin "1") (pinfunction "1_1") (pintype "passive"))
      (node (ref "SSR_3AB") (pin "3") (pinfunction "I+_3") (pintype "bidirectional"))
    )
    (net (code "184") (name "Net-(SSR_3CDA-I+)") (class "Default")
      (node (ref "R_3C") (pin "1") (pinfunction "1_1") (pintype "passive"))
      (node (ref "SSR_3CD") (pin "1") (pinfunction "I+_1") (pintype "bidirectional"))
    )
    (net (code "185") (name "Net-(SSR_3CDB-I+)") (class "Default")
      (node (ref "R_3D") (pin "1") (pinfunction "1_1") (pintype "passive"))
      (node (ref "SSR_3CD") (pin "3") (pinfunction "I+_3") (pintype "bidirectional"))
    )
    (net (code "186") (name "Net-(SSR_3EFA-I+)") (class "Default")
      (node (ref "R_3E") (pin "1") (pinfunction "1_1") (pintype "passive"))
      (node (ref "SSR_3EF") (pin "1") (pinfunction "I+_1") (pintype "bidirectional"))
    )
    (net (code "187") (name "Net-(SSR_3EFB-I+)") (class "Default")
      (node (ref "R_3F") (pin "1") (pinfunction "1_1") (pintype "passive"))
      (node (ref "SSR_3EF") (pin "3") (pinfunction "I+_3") (pintype "bidirectional"))
    )
    (net (code "188") (name "Net-(SSR_3GHA-I+)") (class "Default")
      (node (ref "R_3G") (pin "1") (pinfunction "1_1") (pintype "passive"))
      (node (ref "SSR_3GH") (pin "1") (pinfunction "I+_1") (pintype "bidirectional"))
    )
    (net (code "189") (name "Net-(SSR_3GHB-I+)") (class "Default")
      (node (ref "R_3H") (pin "1") (pinfunction "1_1") (pintype "passive"))
      (node (ref "SSR_3GH") (pin "3") (pinfunction "I+_3") (pintype "bidirectional"))
    )
    (net (code "190") (name "Net-(SSR_3J/4AA-I+)") (class "Default")
      (node (ref "R_3J") (pin "1") (pinfunction "1_1") (pintype "passive"))
      (node (ref "SSR_3J/4A") (pin "1") (pinfunction "I+_1") (pintype "bidirectional"))
    )
    (net (code "191") (name "Net-(SSR_3J/4AB-I+)") (class "Default")
      (node (ref "R_4A") (pin "1") (pinfunction "1_1") (pintype "passive"))
      (node (ref "SSR_3J/4A") (pin "3") (pinfunction "I+_3") (pintype "bidirectional"))
    )
    (net (code "192") (name "Net-(SSR_4BCA-I+)") (class "Default")
      (node (ref "R_4B") (pin "1") (pinfunction "1_1") (pintype "passive"))
      (node (ref "SSR_4BC") (pin "1") (pinfunction "I+_1") (pintype "bidirectional"))
    )
    (net (code "193") (name "Net-(SSR_4BCB-I+)") (class "Default")
      (node (ref "R_4C") (pin "1") (pinfunction "1_1") (pintype "passive"))
      (node (ref "SSR_4BC") (pin "3") (pinfunction "I+_3") (pintype "bidirectional"))
    )
    (net (code "194") (name "Net-(SSR_4DEA-I+)") (class "Default")
      (node (ref "R_4D") (pin "1") (pinfunction "1_1") (pintype "passive"))
      (node (ref "SSR_4DE") (pin "1") (pinfunction "I+_1") (pintype "bidirectional"))
    )
    (net (code "195") (name "Net-(SSR_4DEB-I+)") (class "Default")
      (node (ref "R_4E") (pin "1") (pinfunction "1_1") (pintype "passive"))
      (node (ref "SSR_4DE") (pin "3") (pinfunction "I+_3") (pintype "bidirectional"))
    )
    (net (code "196") (name "Net-(SSR_4FGA-I+)") (class "Default")
      (node (ref "R_4F") (pin "1") (pinfunction "1_1") (pintype "passive"))
      (node (ref "SSR_4FG") (pin "1") (pinfunction "I+_1") (pintype "bidirectional"))
    )
    (net (code "197") (name "Net-(SSR_4FGB-I+)") (class "Default")
      (node (ref "R_4G") (pin "1") (pinfunction "1_1") (pintype "passive"))
      (node (ref "SSR_4FG") (pin "3") (pinfunction "I+_3") (pintype "bidirectional"))
    )
    (net (code "198") (name "Net-(SSR_4HJA-I+)") (class "Default")
      (node (ref "R_4H") (pin "1") (pinfunction "1_1") (pintype "passive"))
      (node (ref "SSR_4HJ") (pin "1") (pinfunction "I+_1") (pintype "bidirectional"))
    )
    (net (code "199") (name "Net-(SSR_4HJB-I+)") (class "Default")
      (node (ref "R_4J") (pin "1") (pinfunction "1_1") (pintype "passive"))
      (node (ref "SSR_4HJ") (pin "3") (pinfunction "I+_3") (pintype "bidirectional"))
    )
    (net (code "200") (name "Net-(SSR_5ABA-I+)") (class "Default")
      (node (ref "R_5A") (pin "1") (pinfunction "1_1") (pintype "passive"))
      (node (ref "SSR_5AB") (pin "1") (pinfunction "I+_1") (pintype "bidirectional"))
    )
    (net (code "201") (name "Net-(SSR_5ABB-I+)") (class "Default")
      (node (ref "R_5B") (pin "1") (pinfunction "1_1") (pintype "passive"))
      (node (ref "SSR_5AB") (pin "3") (pinfunction "I+_3") (pintype "bidirectional"))
    )
    (net (code "202") (name "Net-(SSR_5CDA-I+)") (class "Default")
      (node (ref "R_5C") (pin "1") (pinfunction "1_1") (pintype "passive"))
      (node (ref "SSR_5CD") (pin "1") (pinfunction "I+_1") (pintype "bidirectional"))
    )
    (net (code "203") (name "Net-(SSR_5CDB-I+)") (class "Default")
      (node (ref "R_5D") (pin "1") (pinfunction "1_1") (pintype "passive"))
      (node (ref "SSR_5CD") (pin "3") (pinfunction "I+_3") (pintype "bidirectional"))
    )
    (net (code "204") (name "Net-(SSR_5EFA-I+)") (class "Default")
      (node (ref "R_5E") (pin "1") (pinfunction "1_1") (pintype "passive"))
      (node (ref "SSR_5EF") (pin "1") (pinfunction "I+_1") (pintype "bidirectional"))
    )
    (net (code "205") (name "Net-(SSR_5EFB-I+)") (class "Default")
      (node (ref "R_5F") (pin "1") (pinfunction "1_1") (pintype "passive"))
      (node (ref "SSR_5EF") (pin "3") (pinfunction "I+_3") (pintype "bidirectional"))
    )
    (net (code "206") (name "Net-(SSR_5GHA-I+)") (class "Default")
      (node (ref "R_5G") (pin "1") (pinfunction "1_1") (pintype "passive"))
      (node (ref "SSR_5GH") (pin "1") (pinfunction "I+_1") (pintype "bidirectional"))
    )
    (net (code "207") (name "Net-(SSR_5GHB-I+)") (class "Default")
      (node (ref "R_5H") (pin "1") (pinfunction "1_1") (pintype "passive"))
      (node (ref "SSR_5GH") (pin "3") (pinfunction "I+_3") (pintype "bidirectional"))
    )
    (net (code "208") (name "Net-(SSR_5J/6AA-I+)") (class "Default")
      (node (ref "R_5J") (pin "1") (pinfunction "1_1") (pintype "passive"))
      (node (ref "SSR_5J/6A") (pin "1") (pinfunction "I+_1") (pintype "bidirectional"))
    )
    (net (code "209") (name "Net-(SSR_5J/6AB-I+)") (class "Default")
      (node (ref "R_6A") (pin "1") (pinfunction "1_1") (pintype "passive"))
      (node (ref "SSR_5J/6A") (pin "3") (pinfunction "I+_3") (pintype "bidirectional"))
    )
    (net (code "210") (name "Net-(SSR_6BCA-I+)") (class "Default")
      (node (ref "R_6B") (pin "1") (pinfunction "1_1") (pintype "passive"))
      (node (ref "SSR_6BC") (pin "1") (pinfunction "I+_1") (pintype "bidirectional"))
    )
    (net (code "211") (name "Net-(SSR_6BCB-I+)") (class "Default")
      (node (ref "R_6C") (pin "1") (pinfunction "1_1") (pintype "passive"))
      (node (ref "SSR_6BC") (pin "3") (pinfunction "I+_3") (pintype "bidirectional"))
    )
    (net (code "212") (name "Net-(SSR_6DEA-I+)") (class "Default")
      (node (ref "R_6D") (pin "1") (pinfunction "1_1") (pintype "passive"))
      (node (ref "SSR_6DE") (pin "1") (pinfunction "I+_1") (pintype "bidirectional"))
    )
    (net (code "213") (name "Net-(SSR_6DEB-I+)") (class "Default")
      (node (ref "R_6E") (pin "1") (pinfunction "1_1") (pintype "passive"))
      (node (ref "SSR_6DE") (pin "3") (pinfunction "I+_3") (pintype "bidirectional"))
    )
    (net (code "214") (name "Net-(SSR_6FGA-I+)") (class "Default")
      (node (ref "R_6F") (pin "1") (pinfunction "1_1") (pintype "passive"))
      (node (ref "SSR_6FG") (pin "1") (pinfunction "I+_1") (pintype "bidirectional"))
    )
    (net (code "215") (name "Net-(SSR_6FGB-I+)") (class "Default")
      (node (ref "R_6G") (pin "1") (pinfunction "1_1") (pintype "passive"))
      (node (ref "SSR_6FG") (pin "3") (pinfunction "I+_3") (pintype "bidirectional"))
    )
    (net (code "216") (name "Net-(SSR_6HJA-I+)") (class "Default")
      (node (ref "R_6H") (pin "1") (pinfunction "1_1") (pintype "passive"))
      (node (ref "SSR_6HJ") (pin "1") (pinfunction "I+_1") (pintype "bidirectional"))
    )
    (net (code "217") (name "Net-(SSR_6HJB-I+)") (class "Default")
      (node (ref "R_6J") (pin "1") (pinfunction "1_1") (pintype "passive"))
      (node (ref "SSR_6HJ") (pin "3") (pinfunction "I+_3") (pintype "bidirectional"))
    )
    (net (code "218") (name "Net-(SSR_7ABA-I+)") (class "Default")
      (node (ref "R_7A") (pin "1") (pinfunction "1_1") (pintype "passive"))
      (node (ref "SSR_7AB") (pin "1") (pinfunction "I+_1") (pintype "bidirectional"))
    )
    (net (code "219") (name "Net-(SSR_7ABB-I+)") (class "Default")
      (node (ref "R_7B") (pin "1") (pinfunction "1_1") (pintype "passive"))
      (node (ref "SSR_7AB") (pin "3") (pinfunction "I+_3") (pintype "bidirectional"))
    )
    (net (code "220") (name "Net-(SSR_7CDA-I+)") (class "Default")
      (node (ref "R_7C") (pin "1") (pinfunction "1_1") (pintype "passive"))
      (node (ref "SSR_7CD") (pin "1") (pinfunction "I+_1") (pintype "bidirectional"))
    )
    (net (code "221") (name "Net-(SSR_7CDB-I+)") (class "Default")
      (node (ref "R_7D") (pin "1") (pinfunction "1_1") (pintype "passive"))
      (node (ref "SSR_7CD") (pin "3") (pinfunction "I+_3") (pintype "bidirectional"))
    )
    (net (code "222") (name "Net-(SSR_7EFA-I+)") (class "Default")
      (node (ref "R_7E") (pin "1") (pinfunction "1_1") (pintype "passive"))
      (node (ref "SSR_7EF") (pin "1") (pinfunction "I+_1") (pintype "bidirectional"))
    )
    (net (code "223") (name "Net-(SSR_7EFB-I+)") (class "Default")
      (node (ref "R_7F") (pin "1") (pinfunction "1_1") (pintype "passive"))
      (node (ref "SSR_7EF") (pin "3") (pinfunction "I+_3") (pintype "bidirectional"))
    )
    (net (code "224") (name "Net-(SSR_7GHA-I+)") (class "Default")
      (node (ref "R_7G") (pin "1") (pinfunction "1_1") (pintype "passive"))
      (node (ref "SSR_7GH") (pin "1") (pinfunction "I+_1") (pintype "bidirectional"))
    )
    (net (code "225") (name "Net-(SSR_7GHB-I+)") (class "Default")
      (node (ref "R_7H") (pin "1") (pinfunction "1_1") (pintype "passive"))
      (node (ref "SSR_7GH") (pin "3") (pinfunction "I+_3") (pintype "bidirectional"))
    )
    (net (code "226") (name "Net-(SSR_7J/8AA-I+)") (class "Default")
      (node (ref "R_7J") (pin "1") (pinfunction "1_1") (pintype "passive"))
      (node (ref "SSR_7J/8A") (pin "1") (pinfunction "I+_1") (pintype "bidirectional"))
    )
    (net (code "227") (name "Net-(SSR_7J/8AB-I+)") (class "Default")
      (node (ref "R_8A") (pin "1") (pinfunction "1_1") (pintype "passive"))
      (node (ref "SSR_7J/8A") (pin "3") (pinfunction "I+_3") (pintype "bidirectional"))
    )
    (net (code "228") (name "Net-(SSR_8BCA-I+)") (class "Default")
      (node (ref "R_8B") (pin "1") (pinfunction "1_1") (pintype "passive"))
      (node (ref "SSR_8BC") (pin "1") (pinfunction "I+_1") (pintype "bidirectional"))
    )
    (net (code "229") (name "Net-(SSR_8BCB-I+)") (class "Default")
      (node (ref "R_8C") (pin "1") (pinfunction "1_1") (pintype "passive"))
      (node (ref "SSR_8BC") (pin "3") (pinfunction "I+_3") (pintype "bidirectional"))
    )
    (net (code "230") (name "Net-(SSR_8DEA-I+)") (class "Default")
      (node (ref "R_8D") (pin "1") (pinfunction "1_1") (pintype "passive"))
      (node (ref "SSR_8DE") (pin "1") (pinfunction "I+_1") (pintype "bidirectional"))
    )
    (net (code "231") (name "Net-(SSR_8DEB-I+)") (class "Default")
      (node (ref "R_8E") (pin "1") (pinfunction "1_1") (pintype "passive"))
      (node (ref "SSR_8DE") (pin "3") (pinfunction "I+_3") (pintype "bidirectional"))
    )
    (net (code "232") (name "Net-(SSR_8FGA-I+)") (class "Default")
      (node (ref "R_8F") (pin "1") (pinfunction "1_1") (pintype "passive"))
      (node (ref "SSR_8FG") (pin "1") (pinfunction "I+_1") (pintype "bidirectional"))
    )
    (net (code "233") (name "Net-(SSR_8FGB-I+)") (class "Default")
      (node (ref "R_8G") (pin "1") (pinfunction "1_1") (pintype "passive"))
      (node (ref "SSR_8FG") (pin "3") (pinfunction "I+_3") (pintype "bidirectional"))
    )
    (net (code "234") (name "Net-(SSR_8HJA-I+)") (class "Default")
      (node (ref "R_8H") (pin "1") (pinfunction "1_1") (pintype "passive"))
      (node (ref "SSR_8HJ") (pin "1") (pinfunction "I+_1") (pintype "bidirectional"))
    )
    (net (code "235") (name "Net-(SSR_8HJB-I+)") (class "Default")
      (node (ref "R_8J") (pin "1") (pinfunction "1_1") (pintype "passive"))
      (node (ref "SSR_8HJ") (pin "3") (pinfunction "I+_3") (pintype "bidirectional"))
    )
    (net (code "236") (name "REG_CLR") (class "Default")
      (node (ref "ARDUINO_D") (pin "4") (pinfunction "4_4") (pintype "passive"))
      (node (ref "R_CLR") (pin "1") (pinfunction "1_1") (pintype "passive"))
      (node (ref "SHIFTER0") (pin "10") (pinfunction "~{SCLR}_10") (pintype "bidirectional"))
      (node (ref "SHIFTER1") (pin "10") (pinfunction "~{SCLR}_10") (pintype "bidirectional"))
      (node (ref "SHIFTER2") (pin "10") (pinfunction "~{SCLR}_10") (pintype "bidirectional"))
      (node (ref "SHIFTER3") (pin "10") (pinfunction "~{SCLR}_10") (pintype "bidirectional"))
      (node (ref "SHIFTER4") (pin "10") (pinfunction "~{SCLR}_10") (pintype "bidirectional"))
      (node (ref "SHIFTER5") (pin "10") (pinfunction "~{SCLR}_10") (pintype "bidirectional"))
      (node (ref "SHIFTER6") (pin "10") (pinfunction "~{SCLR}_10") (pintype "bidirectional"))
      (node (ref "SHIFTER7") (pin "10") (pinfunction "~{SCLR}_10") (pintype "bidirectional"))
      (node (ref "SHIFTER8") (pin "10") (pinfunction "~{SCLR}_10") (pintype "bidirectional"))
    )
    (net (code "237") (name "REG_LOAD") (class "Default")
      (node (ref "ARDUINO_D") (pin "5") (pinfunction "5_5") (pintype "passive"))
      (node (ref "R_LOAD") (pin "2") (pinfunction "2_2") (pintype "passive"))
      (node (ref "SHIFTER0") (pin "12") (pinfunction "RCK_12") (pintype "bidirectional"))
      (node (ref "SHIFTER1") (pin "12") (pinfunction "RCK_12") (pintype "bidirectional"))
      (node (ref "SHIFTER2") (pin "12") (pinfunction "RCK_12") (pintype "bidirectional"))
      (node (ref "SHIFTER3") (pin "12") (pinfunction "RCK_12") (pintype "bidirectional"))
      (node (ref "SHIFTER4") (pin "12") (pinfunction "RCK_12") (pintype "bidirectional"))
      (node (ref "SHIFTER5") (pin "12") (pinfunction "RCK_12") (pintype "bidirectional"))
      (node (ref "SHIFTER6") (pin "12") (pinfunction "RCK_12") (pintype "bidirectional"))
      (node (ref "SHIFTER7") (pin "12") (pinfunction "RCK_12") (pintype "bidirectional"))
      (node (ref "SHIFTER8") (pin "12") (pinfunction "RCK_12") (pintype "bidirectional"))
    )
    (net (code "238") (name "REG_OE") (class "Default")
      (node (ref "ARDUINO_D") (pin "6") (pinfunction "6_6") (pintype "passive"))
      (node (ref "R_OE") (pin "1") (pinfunction "1_1") (pintype "passive"))
      (node (ref "SHIFTER0") (pin "13") (pinfunction "~{G}_13") (pintype "bidirectional"))
      (node (ref "SHIFTER1") (pin "13") (pinfunction "~{G}_13") (pintype "bidirectional"))
      (node (ref "SHIFTER2") (pin "13") (pinfunction "~{G}_13") (pintype "bidirectional"))
      (node (ref "SHIFTER3") (pin "13") (pinfunction "~{G}_13") (pintype "bidirectional"))
      (node (ref "SHIFTER4") (pin "13") (pinfunction "~{G}_13") (pintype "bidirectional"))
      (node (ref "SHIFTER5") (pin "13") (pinfunction "~{G}_13") (pintype "bidirectional"))
      (node (ref "SHIFTER6") (pin "13") (pinfunction "~{G}_13") (pintype "bidirectional"))
      (node (ref "SHIFTER7") (pin "13") (pinfunction "~{G}_13") (pintype "bidirectional"))
      (node (ref "SHIFTER8") (pin "13") (pinfunction "~{G}_13") (pintype "bidirectional"))
    )
    (net (code "239") (name "SPI_MISO") (class "Default")
      (node (ref "ARDUINO_D") (pin "1") (pinfunction "1_1") (pintype "passive"))
      (node (ref "HEADER_EXT") (pin "4") (pinfunction "4_4") (pintype "passive"))
    )
    (net (code "240") (name "SPI_MOSI") (class "Default")
      (node (ref "ARDUINO_D") (pin "2") (pinfunction "2_2") (pintype "passive"))
      (node (ref "HEADER_EXT") (pin "5") (pinfunction "5_5") (pintype "passive"))
      (node (ref "SHIFTER0") (pin "14") (pinfunction "SI_14") (pintype "bidirectional"))
    )
    (net (code "241") (name "SPI_SCLK") (class "Default")
      (node (ref "ARDUINO_A") (pin "1") (pinfunction "1_1") (pintype "passive"))
      (node (ref "HEADER_EXT") (pin "3") (pinfunction "3_3") (pintype "passive"))
      (node (ref "SHIFTER0") (pin "11") (pinfunction "SCK_11") (pintype "bidirectional"))
      (node (ref "SHIFTER1") (pin "11") (pinfunction "SCK_11") (pintype "bidirectional"))
      (node (ref "SHIFTER2") (pin "11") (pinfunction "SCK_11") (pintype "bidirectional"))
      (node (ref "SHIFTER3") (pin "11") (pinfunction "SCK_11") (pintype "bidirectional"))
      (node (ref "SHIFTER4") (pin "11") (pinfunction "SCK_11") (pintype "bidirectional"))
      (node (ref "SHIFTER5") (pin "11") (pinfunction "SCK_11") (pintype "bidirectional"))
      (node (ref "SHIFTER6") (pin "11") (pinfunction "SCK_11") (pintype "bidirectional"))
      (node (ref "SHIFTER7") (pin "11") (pinfunction "SCK_11") (pintype "bidirectional"))
      (node (ref "SHIFTER8") (pin "11") (pinfunction "SCK_11") (pintype "bidirectional"))
    )
    (net (code "242") (name "SPI_SO1-SI2") (class "Default")
      (node (ref "SHIFTER0") (pin "9") (pinfunction "SO_9") (pintype "bidirectional"))
      (node (ref "SHIFTER1") (pin "14") (pinfunction "SI_14") (pintype "bidirectional"))
    )
    (net (code "243") (name "SPI_SO2-SI3") (class "Default")
      (node (ref "SHIFTER1") (pin "9") (pinfunction "SO_9") (pintype "bidirectional"))
      (node (ref "SHIFTER2") (pin "14") (pinfunction "SI_14") (pintype "bidirectional"))
    )
    (net (code "244") (name "SPI_SO3-SI4") (class "Default")
      (node (ref "SHIFTER2") (pin "9") (pinfunction "SO_9") (pintype "bidirectional"))
      (node (ref "SHIFTER3") (pin "14") (pinfunction "SI_14") (pintype "bidirectional"))
    )
    (net (code "245") (name "SPI_SO4-SI5") (class "Default")
      (node (ref "SHIFTER3") (pin "9") (pinfunction "SO_9") (pintype "bidirectional"))
      (node (ref "SHIFTER4") (pin "14") (pinfunction "SI_14") (pintype "bidirectional"))
    )
    (net (code "246") (name "SPI_SO5-SI6") (class "Default")
      (node (ref "SHIFTER4") (pin "9") (pinfunction "SO_9") (pintype "bidirectional"))
      (node (ref "SHIFTER5") (pin "14") (pinfunction "SI_14") (pintype "bidirectional"))
    )
    (net (code "247") (name "SPI_SO6-SI7") (class "Default")
      (node (ref "SHIFTER5") (pin "9") (pinfunction "SO_9") (pintype "bidirectional"))
      (node (ref "SHIFTER6") (pin "14") (pinfunction "SI_14") (pintype "bidirectional"))
    )
    (net (code "248") (name "SPI_SO7-SI8") (class "Default")
      (node (ref "SHIFTER6") (pin "9") (pinfunction "SO_9") (pintype "bidirectional"))
      (node (ref "SHIFTER7") (pin "14") (pinfunction "SI_14") (pintype "bidirectional"))
    )
    (net (code "249") (name "SPI_SO8-SI9") (class "Default")
      (node (ref "SHIFTER7") (pin "9") (pinfunction "SO_9") (pintype "bidirectional"))
      (node (ref "SHIFTER8") (pin "14") (pinfunction "SI_14") (pintype "bidirectional"))
    )
    (net (code "250") (name "SPI_SS") (class "Default")
      (node (ref "ARDUINO_D") (pin "3") (pinfunction "3_3") (pintype "passive"))
      (node (ref "HEADER_EXT") (pin "6") (pinfunction "6_6") (pintype "passive"))
    )
    (net (code "251") (name "SW-1A") (class "Default")
      (node (ref "SHIFTER0") (pin "15") (pinfunction "Q0_15") (pintype "bidirectional"))
      (node (ref "SSR_1AB") (pin "2") (pinfunction "I-_2") (pintype "bidirectional"))
    )
    (net (code "252") (name "SW-1B") (class "Default")
      (node (ref "SHIFTER0") (pin "1") (pinfunction "Q1_1") (pintype "bidirectional"))
      (node (ref "SSR_1AB") (pin "4") (pinfunction "I-_4") (pintype "bidirectional"))
    )
    (net (code "253") (name "SW-1C") (class "Default")
      (node (ref "SHIFTER0") (pin "2") (pinfunction "Q2_2") (pintype "bidirectional"))
      (node (ref "SSR_1CD") (pin "2") (pinfunction "I-_2") (pintype "bidirectional"))
    )
    (net (code "254") (name "SW-1D") (class "Default")
      (node (ref "SHIFTER0") (pin "3") (pinfunction "Q3_3") (pintype "bidirectional"))
      (node (ref "SSR_1CD") (pin "4") (pinfunction "I-_4") (pintype "bidirectional"))
    )
    (net (code "255") (name "SW-1E") (class "Default")
      (node (ref "SHIFTER0") (pin "4") (pinfunction "Q4_4") (pintype "bidirectional"))
      (node (ref "SSR_1EF") (pin "2") (pinfunction "I-_2") (pintype "bidirectional"))
    )
    (net (code "256") (name "SW-1F") (class "Default")
      (node (ref "SHIFTER0") (pin "5") (pinfunction "Q5_5") (pintype "bidirectional"))
      (node (ref "SSR_1EF") (pin "4") (pinfunction "I-_4") (pintype "bidirectional"))
    )
    (net (code "257") (name "SW-1G") (class "Default")
      (node (ref "SHIFTER0") (pin "6") (pinfunction "Q6_6") (pintype "bidirectional"))
      (node (ref "SSR_1GH") (pin "2") (pinfunction "I-_2") (pintype "bidirectional"))
    )
    (net (code "258") (name "SW-1H") (class "Default")
      (node (ref "SHIFTER0") (pin "7") (pinfunction "Q7_7") (pintype "bidirectional"))
      (node (ref "SSR_1GH") (pin "4") (pinfunction "I-_4") (pintype "bidirectional"))
    )
    (net (code "259") (name "SW-1J") (class "Default")
      (node (ref "SHIFTER1") (pin "15") (pinfunction "Q0_15") (pintype "bidirectional"))
      (node (ref "SSR_1J/2A") (pin "2") (pinfunction "I-_2") (pintype "bidirectional"))
    )
    (net (code "260") (name "SW-2A") (class "Default")
      (node (ref "SHIFTER1") (pin "1") (pinfunction "Q1_1") (pintype "bidirectional"))
      (node (ref "SSR_1J/2A") (pin "4") (pinfunction "I-_4") (pintype "bidirectional"))
    )
    (net (code "261") (name "SW-2B") (class "Default")
      (node (ref "SHIFTER1") (pin "2") (pinfunction "Q2_2") (pintype "bidirectional"))
      (node (ref "SSR_2BC") (pin "2") (pinfunction "I-_2") (pintype "bidirectional"))
    )
    (net (code "262") (name "SW-2C") (class "Default")
      (node (ref "SHIFTER1") (pin "3") (pinfunction "Q3_3") (pintype "bidirectional"))
      (node (ref "SSR_2BC") (pin "4") (pinfunction "I-_4") (pintype "bidirectional"))
    )
    (net (code "263") (name "SW-2D") (class "Default")
      (node (ref "SHIFTER1") (pin "4") (pinfunction "Q4_4") (pintype "bidirectional"))
      (node (ref "SSR_2DE") (pin "2") (pinfunction "I-_2") (pintype "bidirectional"))
    )
    (net (code "264") (name "SW-2E") (class "Default")
      (node (ref "SHIFTER1") (pin "5") (pinfunction "Q5_5") (pintype "bidirectional"))
      (node (ref "SSR_2DE") (pin "4") (pinfunction "I-_4") (pintype "bidirectional"))
    )
    (net (code "265") (name "SW-2F") (class "Default")
      (node (ref "SHIFTER1") (pin "6") (pinfunction "Q6_6") (pintype "bidirectional"))
      (node (ref "SSR_2FG") (pin "2") (pinfunction "I-_2") (pintype "bidirectional"))
    )
    (net (code "266") (name "SW-2G") (class "Default")
      (node (ref "SHIFTER1") (pin "7") (pinfunction "Q7_7") (pintype "bidirectional"))
      (node (ref "SSR_2FG") (pin "4") (pinfunction "I-_4") (pintype "bidirectional"))
    )
    (net (code "267") (name "SW-2H") (class "Default")
      (node (ref "SHIFTER2") (pin "15") (pinfunction "Q0_15") (pintype "bidirectional"))
      (node (ref "SSR_2HJ") (pin "2") (pinfunction "I-_2") (pintype "bidirectional"))
    )
    (net (code "268") (name "SW-2J") (class "Default")
      (node (ref "SHIFTER2") (pin "1") (pinfunction "Q1_1") (pintype "bidirectional"))
      (node (ref "SSR_2HJ") (pin "4") (pinfunction "I-_4") (pintype "bidirectional"))
    )
    (net (code "269") (name "SW-3A") (class "Default")
      (node (ref "SHIFTER2") (pin "2") (pinfunction "Q2_2") (pintype "bidirectional"))
      (node (ref "SSR_3AB") (pin "2") (pinfunction "I-_2") (pintype "bidirectional"))
    )
    (net (code "270") (name "SW-3B") (class "Default")
      (node (ref "SHIFTER2") (pin "3") (pinfunction "Q3_3") (pintype "bidirectional"))
      (node (ref "SSR_3AB") (pin "4") (pinfunction "I-_4") (pintype "bidirectional"))
    )
    (net (code "271") (name "SW-3C") (class "Default")
      (node (ref "SHIFTER2") (pin "4") (pinfunction "Q4_4") (pintype "bidirectional"))
      (node (ref "SSR_3CD") (pin "2") (pinfunction "I-_2") (pintype "bidirectional"))
    )
    (net (code "272") (name "SW-3D") (class "Default")
      (node (ref "SHIFTER2") (pin "5") (pinfunction "Q5_5") (pintype "bidirectional"))
      (node (ref "SSR_3CD") (pin "4") (pinfunction "I-_4") (pintype "bidirectional"))
    )
    (net (code "273") (name "SW-3E") (class "Default")
      (node (ref "SHIFTER2") (pin "6") (pinfunction "Q6_6") (pintype "bidirectional"))
      (node (ref "SSR_3EF") (pin "2") (pinfunction "I-_2") (pintype "bidirectional"))
    )
    (net (code "274") (name "SW-3F") (class "Default")
      (node (ref "SHIFTER2") (pin "7") (pinfunction "Q7_7") (pintype "bidirectional"))
      (node (ref "SSR_3EF") (pin "4") (pinfunction "I-_4") (pintype "bidirectional"))
    )
    (net (code "275") (name "SW-3G") (class "Default")
      (node (ref "SHIFTER3") (pin "15") (pinfunction "Q0_15") (pintype "bidirectional"))
      (node (ref "SSR_3GH") (pin "2") (pinfunction "I-_2") (pintype "bidirectional"))
    )
    (net (code "276") (name "SW-3H") (class "Default")
      (node (ref "SHIFTER3") (pin "1") (pinfunction "Q1_1") (pintype "bidirectional"))
      (node (ref "SSR_3GH") (pin "4") (pinfunction "I-_4") (pintype "bidirectional"))
    )
    (net (code "277") (name "SW-3J") (class "Default")
      (node (ref "SHIFTER3") (pin "2") (pinfunction "Q2_2") (pintype "bidirectional"))
      (node (ref "SSR_3J/4A") (pin "2") (pinfunction "I-_2") (pintype "bidirectional"))
    )
    (net (code "278") (name "SW-4A") (class "Default")
      (node (ref "SHIFTER3") (pin "3") (pinfunction "Q3_3") (pintype "bidirectional"))
      (node (ref "SSR_3J/4A") (pin "4") (pinfunction "I-_4") (pintype "bidirectional"))
    )
    (net (code "279") (name "SW-4B") (class "Default")
      (node (ref "SHIFTER3") (pin "4") (pinfunction "Q4_4") (pintype "bidirectional"))
      (node (ref "SSR_4BC") (pin "2") (pinfunction "I-_2") (pintype "bidirectional"))
    )
    (net (code "280") (name "SW-4C") (class "Default")
      (node (ref "SHIFTER3") (pin "5") (pinfunction "Q5_5") (pintype "bidirectional"))
      (node (ref "SSR_4BC") (pin "4") (pinfunction "I-_4") (pintype "bidirectional"))
    )
    (net (code "281") (name "SW-4D") (class "Default")
      (node (ref "SHIFTER3") (pin "6") (pinfunction "Q6_6") (pintype "bidirectional"))
      (node (ref "SSR_4DE") (pin "2") (pinfunction "I-_2") (pintype "bidirectional"))
    )
    (net (code "282") (name "SW-4E") (class "Default")
      (node (ref "SHIFTER3") (pin "7") (pinfunction "Q7_7") (pintype "bidirectional"))
      (node (ref "SSR_4DE") (pin "4") (pinfunction "I-_4") (pintype "bidirectional"))
    )
    (net (code "283") (name "SW-4F") (class "Default")
      (node (ref "SHIFTER4") (pin "15") (pinfunction "Q0_15") (pintype "bidirectional"))
      (node (ref "SSR_4FG") (pin "2") (pinfunction "I-_2") (pintype "bidirectional"))
    )
    (net (code "284") (name "SW-4G") (class "Default")
      (node (ref "SHIFTER4") (pin "1") (pinfunction "Q1_1") (pintype "bidirectional"))
      (node (ref "SSR_4FG") (pin "4") (pinfunction "I-_4") (pintype "bidirectional"))
    )
    (net (code "285") (name "SW-4H") (class "Default")
      (node (ref "SHIFTER4") (pin "2") (pinfunction "Q2_2") (pintype "bidirectional"))
      (node (ref "SSR_4HJ") (pin "2") (pinfunction "I-_2") (pintype "bidirectional"))
    )
    (net (code "286") (name "SW-4J") (class "Default")
      (node (ref "SHIFTER4") (pin "3") (pinfunction "Q3_3") (pintype "bidirectional"))
      (node (ref "SSR_4HJ") (pin "4") (pinfunction "I-_4") (pintype "bidirectional"))
    )
    (net (code "287") (name "SW-5A") (class "Default")
      (node (ref "SHIFTER4") (pin "4") (pinfunction "Q4_4") (pintype "bidirectional"))
      (node (ref "SSR_5AB") (pin "2") (pinfunction "I-_2") (pintype "bidirectional"))
    )
    (net (code "288") (name "SW-5B") (class "Default")
      (node (ref "SHIFTER4") (pin "5") (pinfunction "Q5_5") (pintype "bidirectional"))
      (node (ref "SSR_5AB") (pin "4") (pinfunction "I-_4") (pintype "bidirectional"))
    )
    (net (code "289") (name "SW-5C") (class "Default")
      (node (ref "SHIFTER4") (pin "6") (pinfunction "Q6_6") (pintype "bidirectional"))
      (node (ref "SSR_5CD") (pin "2") (pinfunction "I-_2") (pintype "bidirectional"))
    )
    (net (code "290") (name "SW-5D") (class "Default")
      (node (ref "SHIFTER4") (pin "7") (pinfunction "Q7_7") (pintype "bidirectional"))
      (node (ref "SSR_5CD") (pin "4") (pinfunction "I-_4") (pintype "bidirectional"))
    )
    (net (code "291") (name "SW-5E") (class "Default")
      (node (ref "SHIFTER5") (pin "15") (pinfunction "Q0_15") (pintype "bidirectional"))
      (node (ref "SSR_5EF") (pin "2") (pinfunction "I-_2") (pintype "bidirectional"))
    )
    (net (code "292") (name "SW-5F") (class "Default")
      (node (ref "SHIFTER5") (pin "1") (pinfunction "Q1_1") (pintype "bidirectional"))
      (node (ref "SSR_5EF") (pin "4") (pinfunction "I-_4") (pintype "bidirectional"))
    )
    (net (code "293") (name "SW-5G") (class "Default")
      (node (ref "SHIFTER5") (pin "2") (pinfunction "Q2_2") (pintype "bidirectional"))
      (node (ref "SSR_5GH") (pin "2") (pinfunction "I-_2") (pintype "bidirectional"))
    )
    (net (code "294") (name "SW-5H") (class "Default")
      (node (ref "SHIFTER5") (pin "3") (pinfunction "Q3_3") (pintype "bidirectional"))
      (node (ref "SSR_5GH") (pin "4") (pinfunction "I-_4") (pintype "bidirectional"))
    )
    (net (code "295") (name "SW-5J") (class "Default")
      (node (ref "SHIFTER5") (pin "4") (pinfunction "Q4_4") (pintype "bidirectional"))
      (node (ref "SSR_5J/6A") (pin "2") (pinfunction "I-_2") (pintype "bidirectional"))
    )
    (net (code "296") (name "SW-6A") (class "Default")
      (node (ref "SHIFTER5") (pin "5") (pinfunction "Q5_5") (pintype "bidirectional"))
      (node (ref "SSR_5J/6A") (pin "4") (pinfunction "I-_4") (pintype "bidirectional"))
    )
    (net (code "297") (name "SW-6B") (class "Default")
      (node (ref "SHIFTER5") (pin "6") (pinfunction "Q6_6") (pintype "bidirectional"))
      (node (ref "SSR_6BC") (pin "2") (pinfunction "I-_2") (pintype "bidirectional"))
    )
    (net (code "298") (name "SW-6C") (class "Default")
      (node (ref "SHIFTER5") (pin "7") (pinfunction "Q7_7") (pintype "bidirectional"))
      (node (ref "SSR_6BC") (pin "4") (pinfunction "I-_4") (pintype "bidirectional"))
    )
    (net (code "299") (name "SW-6D") (class "Default")
      (node (ref "SHIFTER6") (pin "15") (pinfunction "Q0_15") (pintype "bidirectional"))
      (node (ref "SSR_6DE") (pin "2") (pinfunction "I-_2") (pintype "bidirectional"))
    )
    (net (code "300") (name "SW-6E") (class "Default")
      (node (ref "SHIFTER6") (pin "1") (pinfunction "Q1_1") (pintype "bidirectional"))
      (node (ref "SSR_6DE") (pin "4") (pinfunction "I-_4") (pintype "bidirectional"))
    )
    (net (code "301") (name "SW-6F") (class "Default")
      (node (ref "SHIFTER6") (pin "2") (pinfunction "Q2_2") (pintype "bidirectional"))
      (node (ref "SSR_6FG") (pin "2") (pinfunction "I-_2") (pintype "bidirectional"))
    )
    (net (code "302") (name "SW-6G") (class "Default")
      (node (ref "SHIFTER6") (pin "3") (pinfunction "Q3_3") (pintype "bidirectional"))
      (node (ref "SSR_6FG") (pin "4") (pinfunction "I-_4") (pintype "bidirectional"))
    )
    (net (code "303") (name "SW-6H") (class "Default")
      (node (ref "SHIFTER6") (pin "4") (pinfunction "Q4_4") (pintype "bidirectional"))
      (node (ref "SSR_6HJ") (pin "2") (pinfunction "I-_2") (pintype "bidirectional"))
    )
    (net (code "304") (name "SW-6J") (class "Default")
      (node (ref "SHIFTER6") (pin "5") (pinfunction "Q5_5") (pintype "bidirectional"))
      (node (ref "SSR_6HJ") (pin "4") (pinfunction "I-_4") (pintype "bidirectional"))
    )
    (net (code "305") (name "SW-7A") (class "Default")
      (node (ref "SHIFTER6") (pin "6") (pinfunction "Q6_6") (pintype "bidirectional"))
      (node (ref "SSR_7AB") (pin "2") (pinfunction "I-_2") (pintype "bidirectional"))
    )
    (net (code "306") (name "SW-7B") (class "Default")
      (node (ref "SHIFTER6") (pin "7") (pinfunction "Q7_7") (pintype "bidirectional"))
      (node (ref "SSR_7AB") (pin "4") (pinfunction "I-_4") (pintype "bidirectional"))
    )
    (net (code "307") (name "SW-7C") (class "Default")
      (node (ref "SHIFTER7") (pin "15") (pinfunction "Q0_15") (pintype "bidirectional"))
      (node (ref "SSR_7CD") (pin "2") (pinfunction "I-_2") (pintype "bidirectional"))
    )
    (net (code "308") (name "SW-7D") (class "Default")
      (node (ref "SHIFTER7") (pin "1") (pinfunction "Q1_1") (pintype "bidirectional"))
      (node (ref "SSR_7CD") (pin "4") (pinfunction "I-_4") (pintype "bidirectional"))
    )
    (net (code "309") (name "SW-7E") (class "Default")
      (node (ref "SHIFTER7") (pin "2") (pinfunction "Q2_2") (pintype "bidirectional"))
      (node (ref "SSR_7EF") (pin "2") (pinfunction "I-_2") (pintype "bidirectional"))
    )
    (net (code "310") (name "SW-7F") (class "Default")
      (node (ref "SHIFTER7") (pin "3") (pinfunction "Q3_3") (pintype "bidirectional"))
      (node (ref "SSR_7EF") (pin "4") (pinfunction "I-_4") (pintype "bidirectional"))
    )
    (net (code "311") (name "SW-7G") (class "Default")
      (node (ref "SHIFTER7") (pin "4") (pinfunction "Q4_4") (pintype "bidirectional"))
      (node (ref "SSR_7GH") (pin "2") (pinfunction "I-_2") (pintype "bidirectional"))
    )
    (net (code "312") (name "SW-7H") (class "Default")
      (node (ref "SHIFTER7") (pin "5") (pinfunction "Q5_5") (pintype "bidirectional"))
      (node (ref "SSR_7GH") (pin "4") (pinfunction "I-_4") (pintype "bidirectional"))
    )
    (net (code "313") (name "SW-7J") (class "Default")
      (node (ref "SHIFTER7") (pin "6") (pinfunction "Q6_6") (pintype "bidirectional"))
      (node (ref "SSR_7J/8A") (pin "2") (pinfunction "I-_2") (pintype "bidirectional"))
    )
    (net (code "314") (name "SW-8A") (class "Default")
      (node (ref "SHIFTER7") (pin "7") (pinfunction "Q7_7") (pintype "bidirectional"))
      (node (ref "SSR_7J/8A") (pin "4") (pinfunction "I-_4") (pintype "bidirectional"))
    )
    (net (code "315") (name "SW-8B") (class "Default")
      (node (ref "SHIFTER8") (pin "15") (pinfunction "Q0_15") (pintype "bidirectional"))
      (node (ref "SSR_8BC") (pin "2") (pinfunction "I-_2") (pintype "bidirectional"))
    )
    (net (code "316") (name "SW-8C") (class "Default")
      (node (ref "SHIFTER8") (pin "1") (pinfunction "Q1_1") (pintype "bidirectional"))
      (node (ref "SSR_8BC") (pin "4") (pinfunction "I-_4") (pintype "bidirectional"))
    )
    (net (code "317") (name "SW-8D") (class "Default")
      (node (ref "SHIFTER8") (pin "2") (pinfunction "Q2_2") (pintype "bidirectional"))
      (node (ref "SSR_8DE") (pin "2") (pinfunction "I-_2") (pintype "bidirectional"))
    )
    (net (code "318") (name "SW-8E") (class "Default")
      (node (ref "SHIFTER8") (pin "3") (pinfunction "Q3_3") (pintype "bidirectional"))
      (node (ref "SSR_8DE") (pin "4") (pinfunction "I-_4") (pintype "bidirectional"))
    )
    (net (code "319") (name "SW-8F") (class "Default")
      (node (ref "SHIFTER8") (pin "4") (pinfunction "Q4_4") (pintype "bidirectional"))
      (node (ref "SSR_8FG") (pin "2") (pinfunction "I-_2") (pintype "bidirectional"))
    )
    (net (code "320") (name "SW-8G") (class "Default")
      (node (ref "SHIFTER8") (pin "5") (pinfunction "Q5_5") (pintype "bidirectional"))
      (node (ref "SSR_8FG") (pin "4") (pinfunction "I-_4") (pintype "bidirectional"))
    )
    (net (code "321") (name "SW-8H") (class "Default")
      (node (ref "SHIFTER8") (pin "6") (pinfunction "Q6_6") (pintype "bidirectional"))
      (node (ref "SSR_8HJ") (pin "2") (pinfunction "I-_2") (pintype "bidirectional"))
    )
    (net (code "322") (name "SW-8J") (class "Default")
      (node (ref "SHIFTER8") (pin "7") (pinfunction "Q7_7") (pintype "bidirectional"))
      (node (ref "SSR_8HJ") (pin "4") (pinfunction "I-_4") (pintype "bidirectional"))
    )
    (net (code "323") (name "TWI_RST") (class "Default")
      (node (ref "I2C_SWITCH") (pin "3") (pinfunction "~{RESET}_3") (pintype "bidirectional"))
      (node (ref "R_RST") (pin "1") (pinfunction "1_1") (pintype "passive"))
    )
    (net (code "324") (name "TWI_SCL") (class "Default")
      (node (ref "ARDUINO_A") (pin "9") (pinfunction "9_9") (pintype "passive"))
      (node (ref "HEADER_EXT") (pin "8") (pinfunction "8_8") (pintype "passive"))
      (node (ref "I2C_SWITCH") (pin "22") (pinfunction "SCL_22") (pintype "bidirectional"))
      (node (ref "R_SCL") (pin "1") (pinfunction "1_1") (pintype "passive"))
    )
    (net (code "325") (name "TWI_SCL1") (class "Default")
      (node (ref "DRV1") (pin "18") (pinfunction "SCL_18") (pintype "bidirectional"))
      (node (ref "I2C_SWITCH") (pin "5") (pinfunction "SCL0_5") (pintype "bidirectional"))
      (node (ref "R_SCL1") (pin "1") (pinfunction "1_1") (pintype "passive"))
    )
    (net (code "326") (name "TWI_SCL2") (class "Default")
      (node (ref "DRV2") (pin "18") (pinfunction "SCL_18") (pintype "bidirectional"))
      (node (ref "I2C_SWITCH") (pin "7") (pinfunction "SCL1_7") (pintype "bidirectional"))
      (node (ref "R_SCL2") (pin "1") (pinfunction "1_1") (pintype "passive"))
    )
    (net (code "327") (name "TWI_SCL3") (class "Default")
      (node (ref "DRV3") (pin "18") (pinfunction "SCL_18") (pintype "bidirectional"))
      (node (ref "I2C_SWITCH") (pin "9") (pinfunction "SCL2_9") (pintype "bidirectional"))
      (node (ref "R_SCL3") (pin "1") (pinfunction "1_1") (pintype "passive"))
    )
    (net (code "328") (name "TWI_SCL4") (class "Default")
      (node (ref "DRV4") (pin "18") (pinfunction "SCL_18") (pintype "bidirectional"))
      (node (ref "I2C_SWITCH") (pin "11") (pinfunction "SCL3_11") (pintype "bidirectional"))
      (node (ref "R_SCL4") (pin "1") (pinfunction "1_1") (pintype "passive"))
    )
    (net (code "329") (name "TWI_SCL5") (class "Default")
      (node (ref "DRV5") (pin "18") (pinfunction "SCL_18") (pintype "bidirectional"))
      (node (ref "I2C_SWITCH") (pin "14") (pinfunction "SCL4_14") (pintype "bidirectional"))
      (node (ref "R_SCL5") (pin "1") (pinfunction "1_1") (pintype "passive"))
    )
    (net (code "330") (name "TWI_SCL6") (class "Default")
      (node (ref "DRV6") (pin "18") (pinfunction "SCL_18") (pintype "bidirectional"))
      (node (ref "I2C_SWITCH") (pin "16") (pinfunction "SCL5_16") (pintype "bidirectional"))
      (node (ref "R_SCL6") (pin "1") (pinfunction "1_1") (pintype "passive"))
    )
    (net (code "331") (name "TWI_SCL7") (class "Default")
      (node (ref "DRV7") (pin "18") (pinfunction "SCL_18") (pintype "bidirectional"))
      (node (ref "I2C_SWITCH") (pin "18") (pinfunction "SCL6_18") (pintype "bidirectional"))
      (node (ref "R_SCL7") (pin "1") (pinfunction "1_1") (pintype "passive"))
    )
    (net (code "332") (name "TWI_SCL8") (class "Default")
      (node (ref "DRV8") (pin "18") (pinfunction "SCL_18") (pintype "bidirectional"))
      (node (ref "I2C_SWITCH") (pin "20") (pinfunction "SCL7_20") (pintype "bidirectional"))
      (node (ref "R_SCL8") (pin "1") (pinfunction "1_1") (pintype "passive"))
    )
    (net (code "333") (name "TWI_SDA") (class "Default")
      (node (ref "ARDUINO_A") (pin "8") (pinfunction "8_8") (pintype "passive"))
      (node (ref "HEADER_EXT") (pin "7") (pinfunction "7_7") (pintype "passive"))
      (node (ref "I2C_SWITCH") (pin "23") (pinfunction "SDA_23") (pintype "bidirectional"))
      (node (ref "R_SDA") (pin "1") (pinfunction "1_1") (pintype "passive"))
    )
    (net (code "334") (name "TWI_SDA1") (class "Default")
      (node (ref "DRV1") (pin "19") (pinfunction "SDA_19") (pintype "bidirectional"))
      (node (ref "I2C_SWITCH") (pin "4") (pinfunction "SDA0_4") (pintype "bidirectional"))
      (node (ref "R_SDA1") (pin "1") (pinfunction "1_1") (pintype "passive"))
    )
    (net (code "335") (name "TWI_SDA2") (class "Default")
      (node (ref "DRV2") (pin "19") (pinfunction "SDA_19") (pintype "bidirectional"))
      (node (ref "I2C_SWITCH") (pin "6") (pinfunction "SDA1_6") (pintype "bidirectional"))
      (node (ref "R_SDA2") (pin "1") (pinfunction "1_1") (pintype "passive"))
    )
    (net (code "336") (name "TWI_SDA3") (class "Default")
      (node (ref "DRV3") (pin "19") (pinfunction "SDA_19") (pintype "bidirectional"))
      (node (ref "I2C_SWITCH") (pin "8") (pinfunction "SDA2_8") (pintype "bidirectional"))
      (node (ref "R_SDA3") (pin "1") (pinfunction "1_1") (pintype "passive"))
    )
    (net (code "337") (name "TWI_SDA4") (class "Default")
      (node (ref "DRV4") (pin "19") (pinfunction "SDA_19") (pintype "bidirectional"))
      (node (ref "I2C_SWITCH") (pin "10") (pinfunction "SDA3_10") (pintype "bidirectional"))
      (node (ref "R_SDA4") (pin "1") (pinfunction "1_1") (pintype "passive"))
    )
    (net (code "338") (name "TWI_SDA5") (class "Default")
      (node (ref "DRV5") (pin "19") (pinfunction "SDA_19") (pintype "bidirectional"))
      (node (ref "I2C_SWITCH") (pin "13") (pinfunction "SDA4_13") (pintype "bidirectional"))
      (node (ref "R_SDA5") (pin "1") (pinfunction "1_1") (pintype "passive"))
    )
    (net (code "339") (name "TWI_SDA6") (class "Default")
      (node (ref "DRV6") (pin "19") (pinfunction "SDA_19") (pintype "bidirectional"))
      (node (ref "I2C_SWITCH") (pin "15") (pinfunction "SDA5_15") (pintype "bidirectional"))
      (node (ref "R_SDA6") (pin "1") (pinfunction "1_1") (pintype "passive"))
    )
    (net (code "340") (name "TWI_SDA7") (class "Default")
      (node (ref "DRV7") (pin "19") (pinfunction "SDA_19") (pintype "bidirectional"))
      (node (ref "I2C_SWITCH") (pin "17") (pinfunction "SDA6_17") (pintype "bidirectional"))
      (node (ref "R_SDA7") (pin "1") (pinfunction "1_1") (pintype "passive"))
    )
    (net (code "341") (name "TWI_SDA8") (class "Default")
      (node (ref "DRV8") (pin "19") (pinfunction "SDA_19") (pintype "bidirectional"))
      (node (ref "I2C_SWITCH") (pin "19") (pinfunction "SDA7_19") (pintype "bidirectional"))
      (node (ref "R_SDA8") (pin "1") (pinfunction "1_1") (pintype "passive"))
    )
    (net (code "342") (name "TWI_SW0") (class "Default")
      (node (ref "ARDUINO_D") (pin "11") (pinfunction "11_11") (pintype "passive"))
      (node (ref "I2C_SWITCH") (pin "1") (pinfunction "A0_1") (pintype "bidirectional"))
    )
    (net (code "343") (name "TWI_SW1") (class "Default")
      (node (ref "ARDUINO_A") (pin "10") (pinfunction "10_10") (pintype "passive"))
      (node (ref "I2C_SWITCH") (pin "2") (pinfunction "A1_2") (pintype "bidirectional"))
    )
    (net (code "344") (name "TWI_SW2") (class "Default")
      (node (ref "ARDUINO_A") (pin "11") (pinfunction "11_11") (pintype "passive"))
      (node (ref "I2C_SWITCH") (pin "21") (pinfunction "A2_21") (pintype "bidirectional"))
    )
    (net (code "345") (name "UART_RXD") (class "Default")
      (node (ref "ARDUINO_D") (pin "14") (pinfunction "14_14") (pintype "passive"))
      (node (ref "HEADER_EXT") (pin "10") (pinfunction "10_10") (pintype "passive"))
    )
    (net (code "346") (name "UART_TXD") (class "Default")
      (node (ref "ARDUINO_D") (pin "15") (pinfunction "15_15") (pintype "passive"))
      (node (ref "HEADER_EXT") (pin "11") (pinfunction "11_11") (pintype "passive"))
    )
    (net (code "347") (name "UART_XCK") (class "Default")
      (node (ref "ARDUINO_D") (pin "9") (pinfunction "9_9") (pintype "passive"))
      (node (ref "HEADER_EXT") (pin "9") (pinfunction "9_9") (pintype "passive"))
    )
    (net (code "348") (name "unconnected-(ARDUINO_A-Pad2)") (class "Default")
      (node (ref "ARDUINO_A") (pin "2") (pinfunction "2_2") (pintype "passive"))
    )
    (net (code "349") (name "unconnected-(ARDUINO_A-Pad3)") (class "Default")
      (node (ref "ARDUINO_A") (pin "3") (pinfunction "3_3") (pintype "passive"))
    )
    (net (code "350") (name "unconnected-(ARDUINO_A-Pad4)") (class "Default")
      (node (ref "ARDUINO_A") (pin "4") (pinfunction "4_4") (pintype "passive"))
    )
    (net (code "351") (name "unconnected-(ARDUINO_A-Pad5)") (class "Default")
      (node (ref "ARDUINO_A") (pin "5") (pinfunction "5_5") (pintype "passive"))
    )
    (net (code "352") (name "unconnected-(ARDUINO_A-Pad6)") (class "Default")
      (node (ref "ARDUINO_A") (pin "6") (pinfunction "6_6") (pintype "passive"))
    )
    (net (code "353") (name "unconnected-(ARDUINO_A-Pad7)") (class "Default")
      (node (ref "ARDUINO_A") (pin "7") (pinfunction "7_7") (pintype "passive"))
    )
    (net (code "354") (name "unconnected-(ARDUINO_A-Pad12)") (class "Default")
      (node (ref "ARDUINO_A") (pin "12") (pinfunction "12_12") (pintype "passive"))
    )
    (net (code "355") (name "unconnected-(ARDUINO_A-Pad13)") (class "Default")
      (node (ref "ARDUINO_A") (pin "13") (pinfunction "13_13") (pintype "passive"))
    )
    (net (code "356") (name "unconnected-(ARDUINO_D-Pad13)") (class "Default")
      (node (ref "ARDUINO_D") (pin "13") (pinfunction "13_13") (pintype "passive"))
    )
    (net (code "357") (name "unconnected-(AUDIO_IN-Pad13)") (class "Default")
      (node (ref "AUDIO_IN") (pin "13") (pinfunction "13_13") (pintype "passive"))
    )
    (net (code "358") (name "unconnected-(GND_LIFT-T1B-Pad3)") (class "Default")
      (node (ref "GND_LIFT") (pin "3") (pinfunction "T1B_3") (pintype "bidirectional"))
    )
    (net (code "359") (name "unconnected-(GND_LIFT-T2B-Pad4)") (class "Default")
      (node (ref "GND_LIFT") (pin "4") (pinfunction "T2B_4") (pintype "bidirectional"))
    )
    (net (code "360") (name "unconnected-(SHIFTER8A-SO-Pad9)") (class "Default")
      (node (ref "SHIFTER8") (pin "9") (pinfunction "SO_9") (pintype "bidirectional"))
    )
  )
)
